# synth_revD.net
KiCad netlist of a schematic drawn in EAGLE
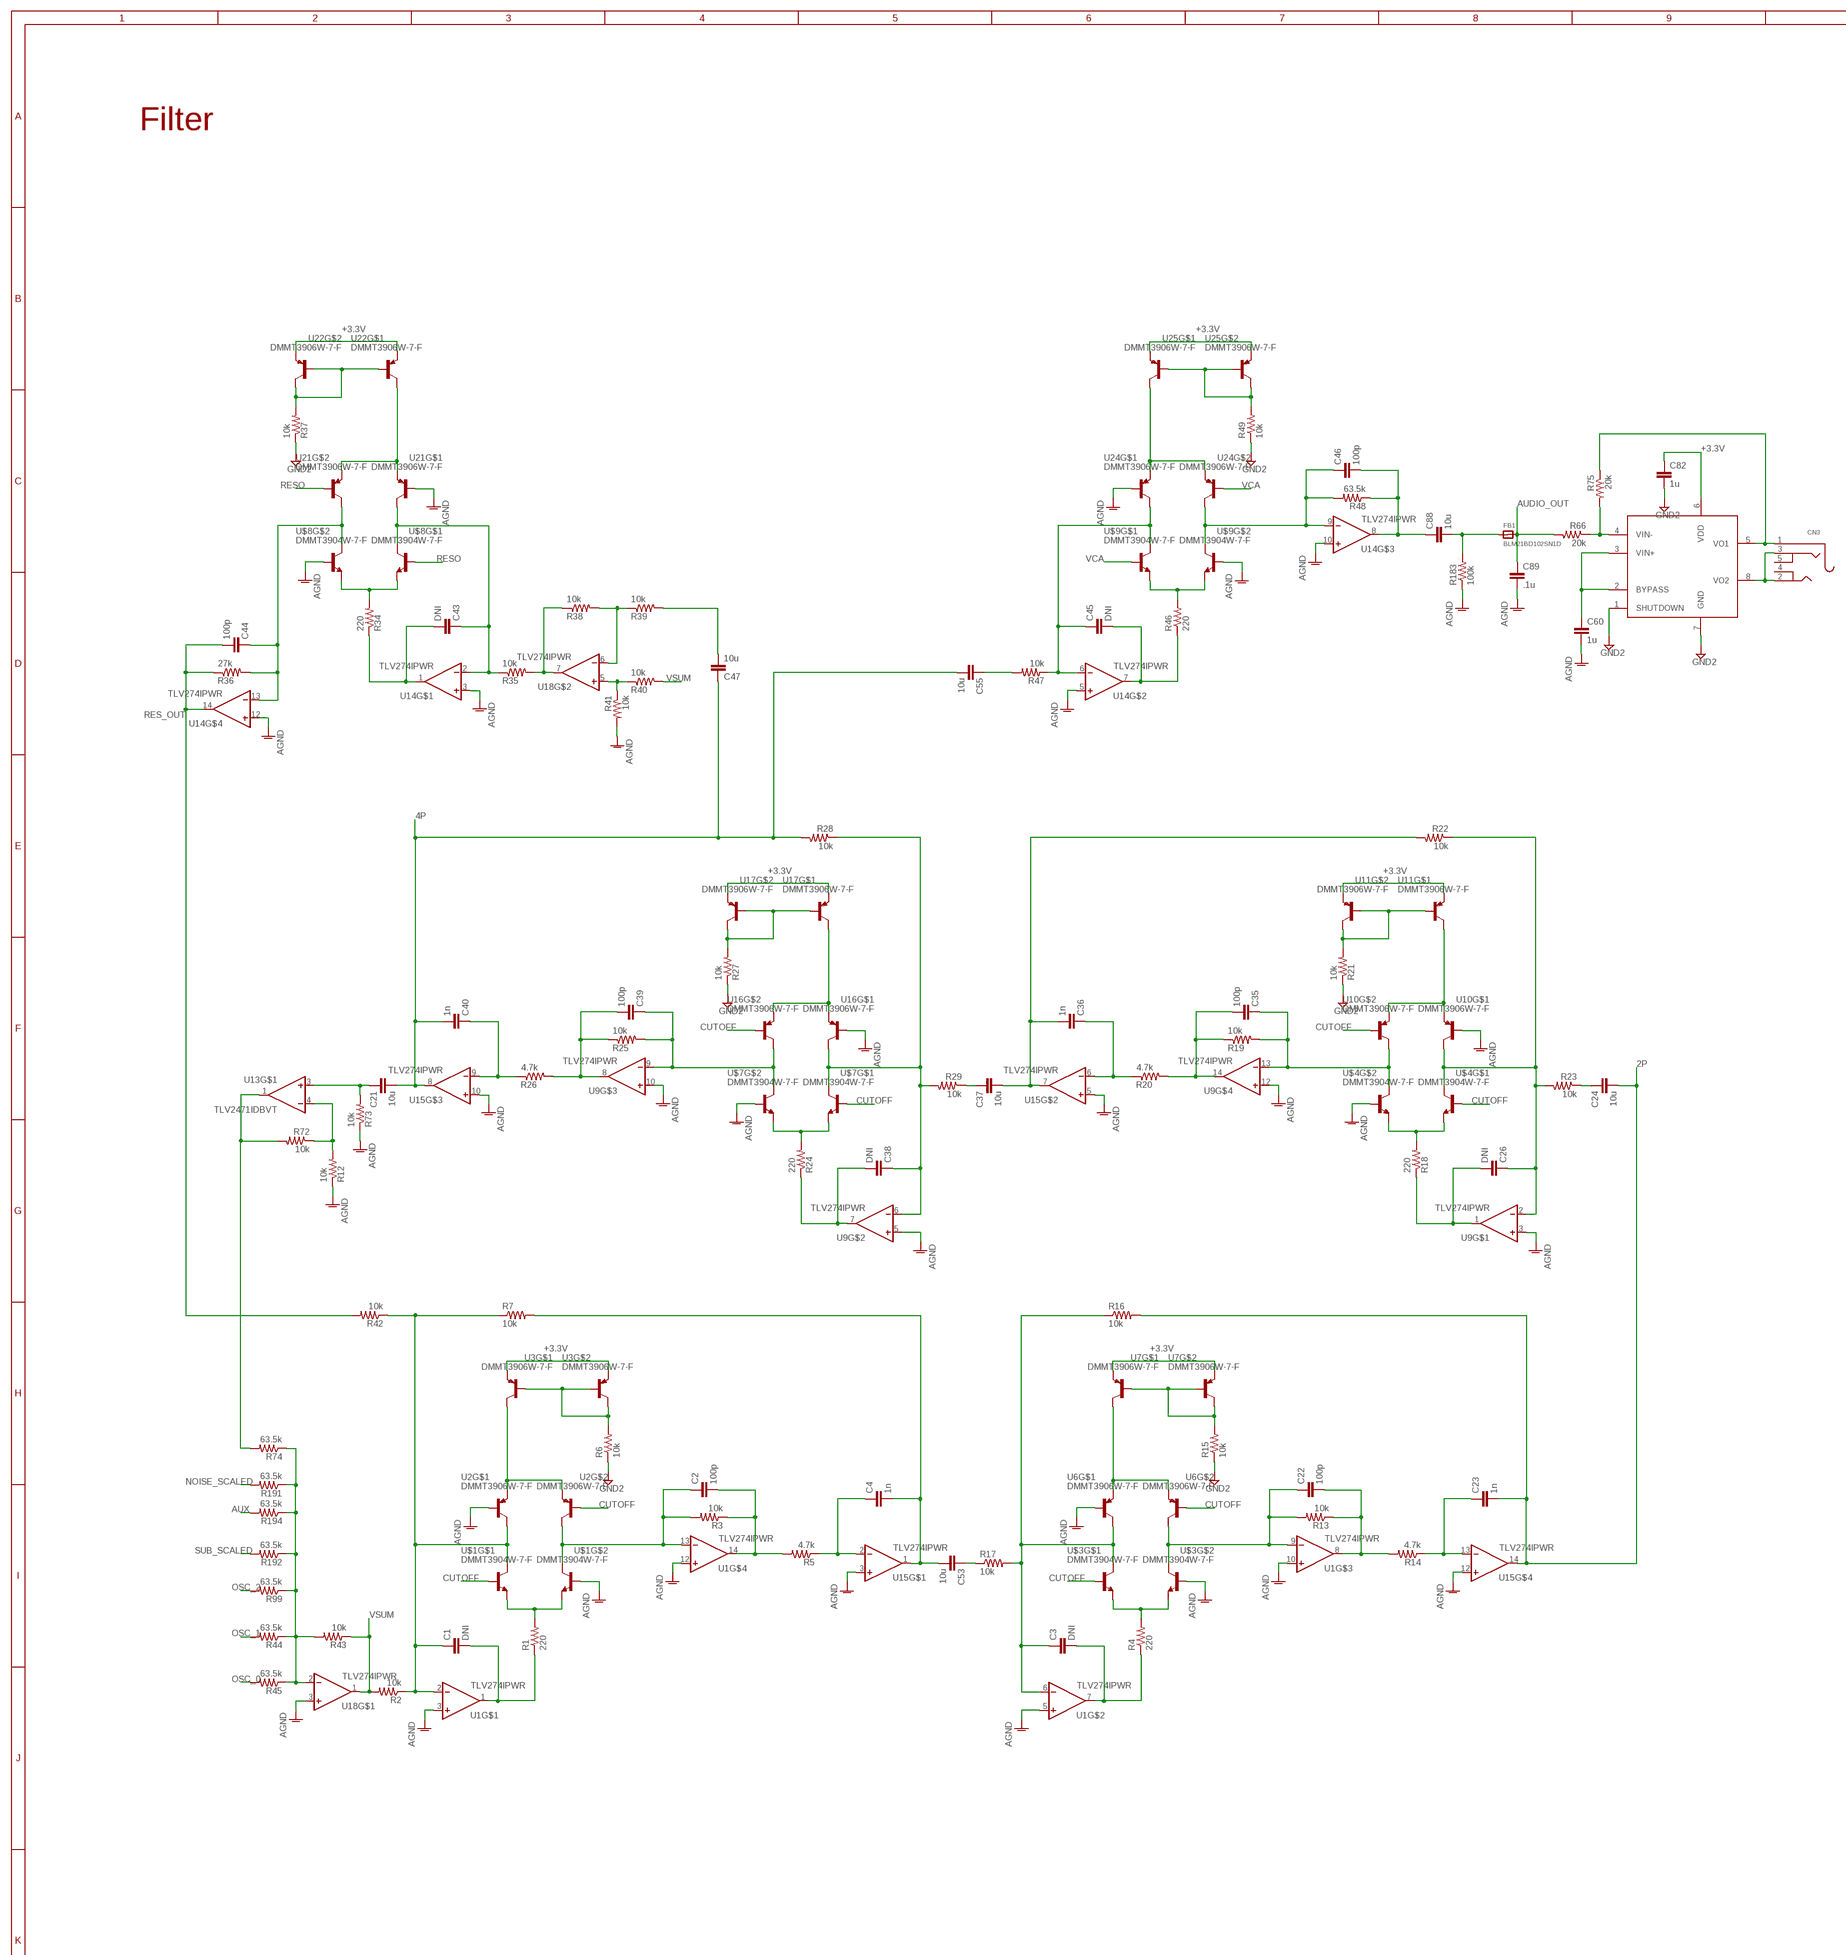
[diagram p0: schematic, sheet 1, part 1 of 3]
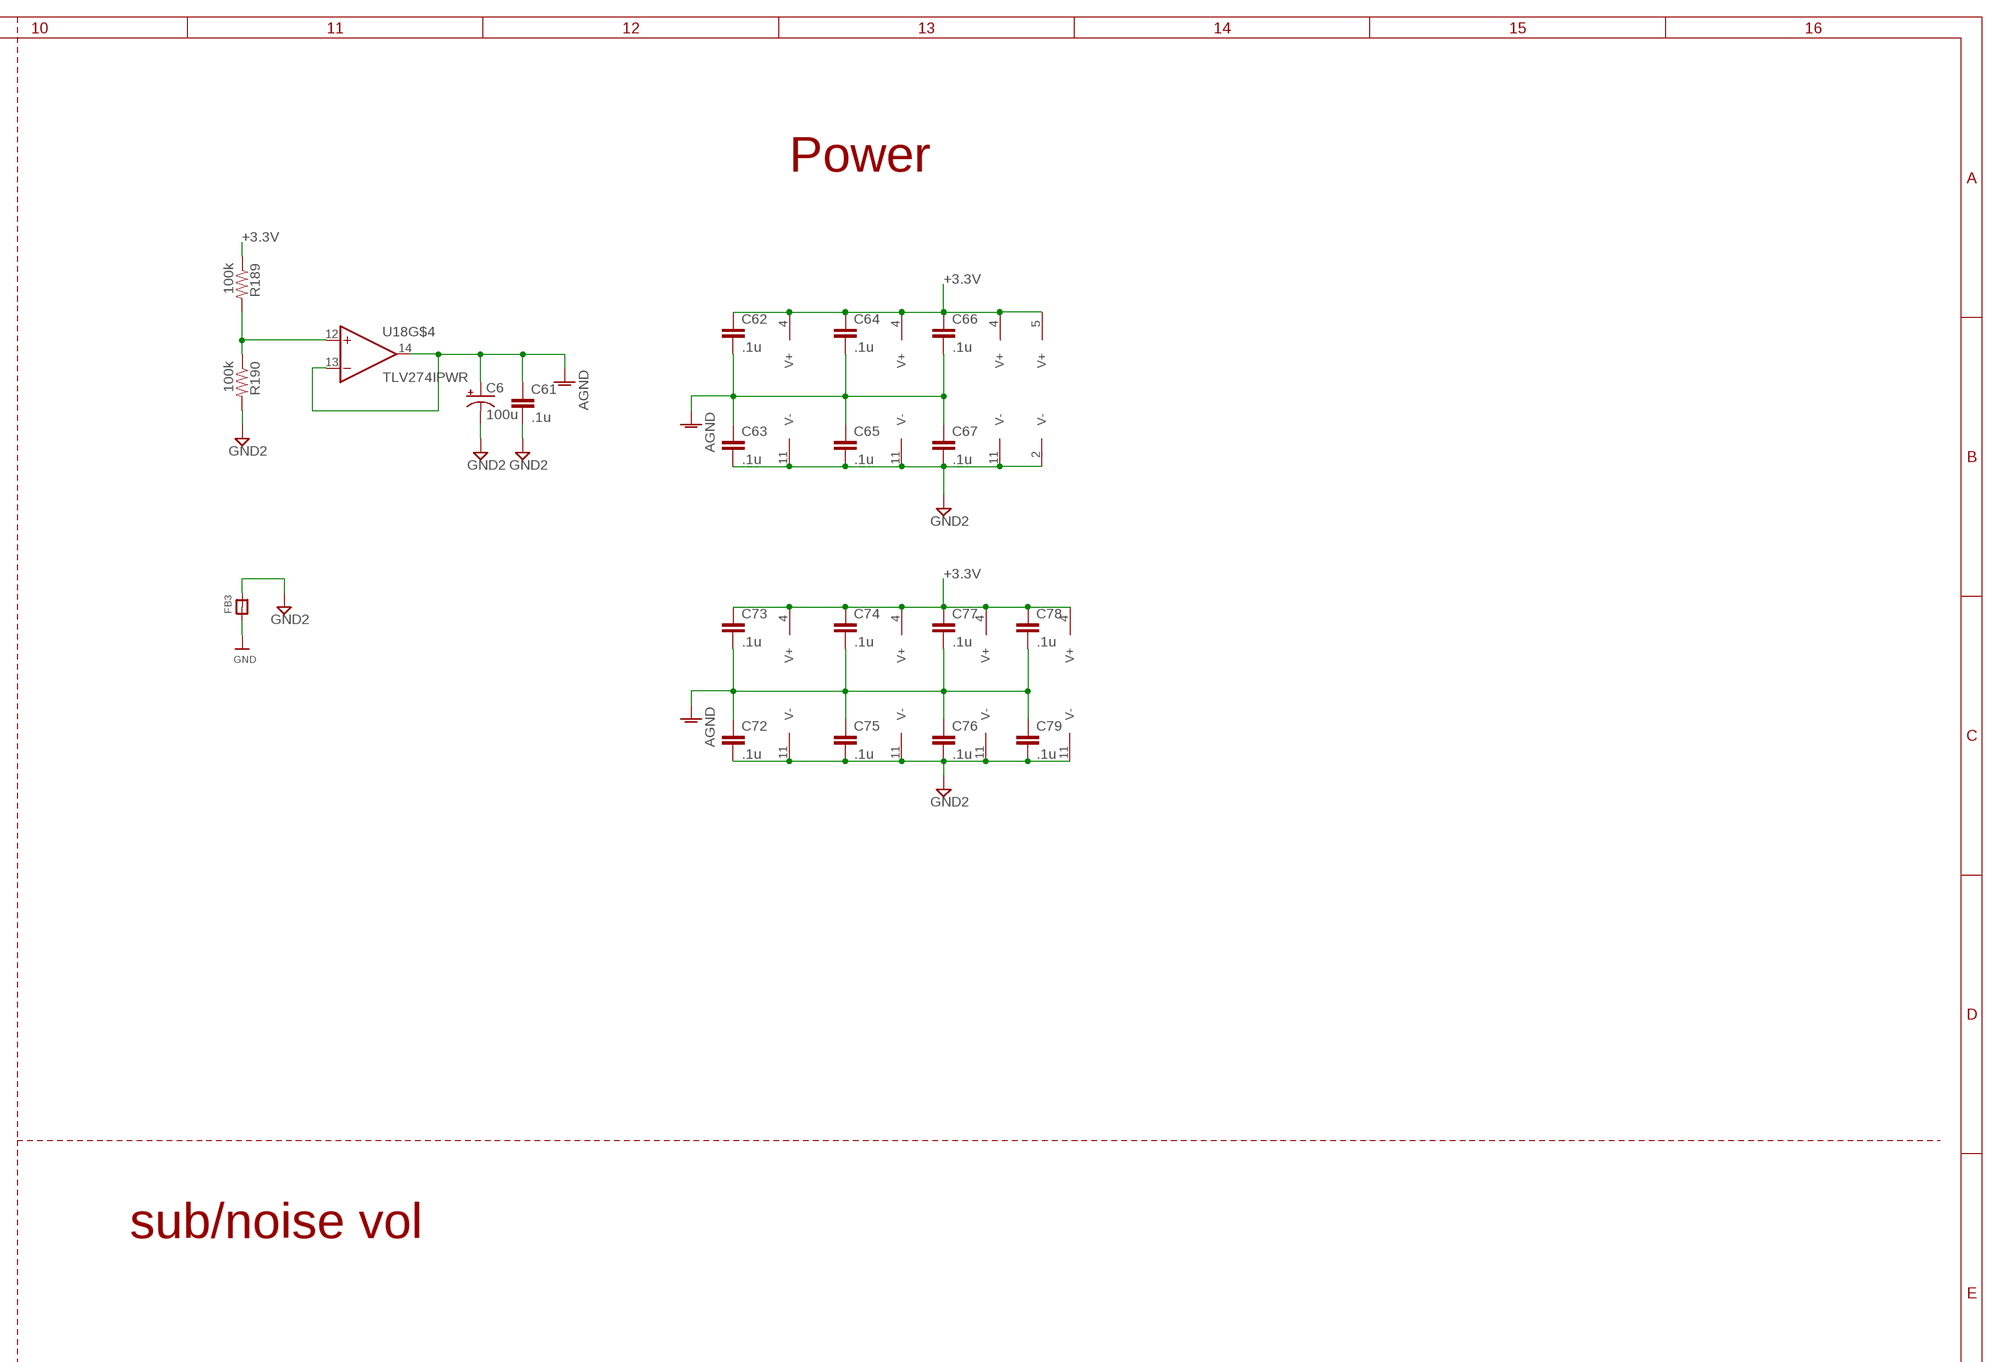
[diagram p1: schematic, sheet 1, part 2 of 3]
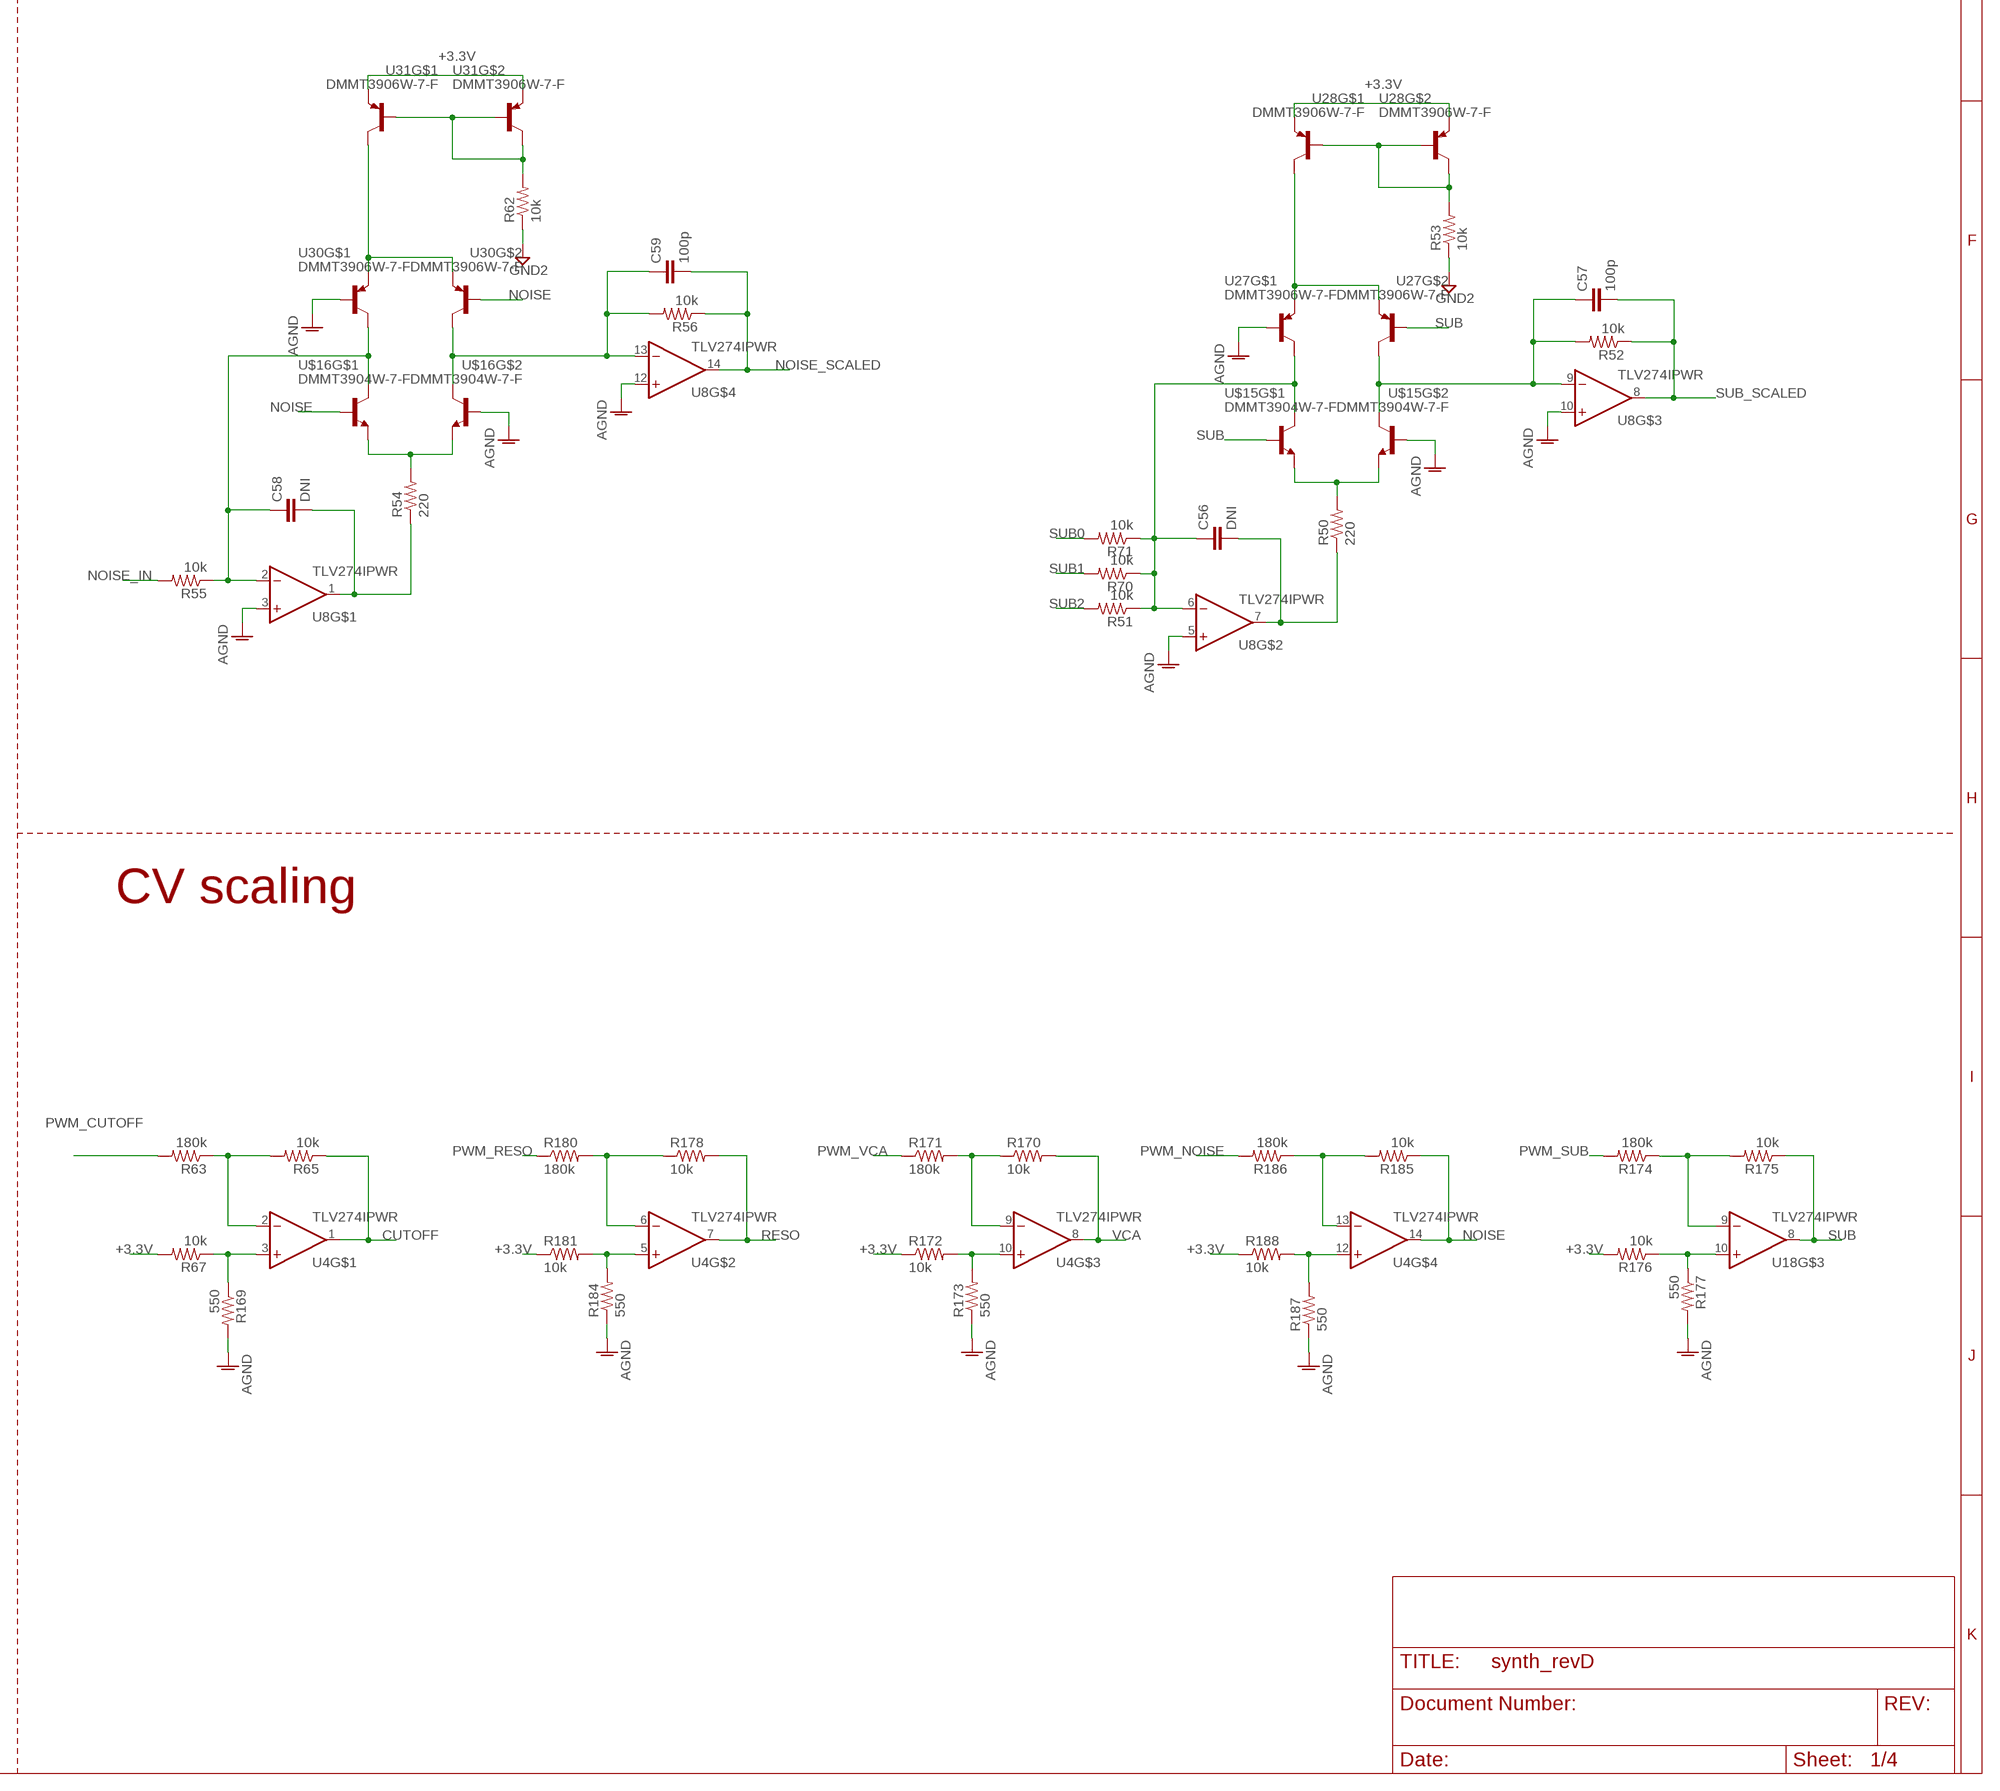
[diagram p2: schematic, sheet 1, part 3 of 3]
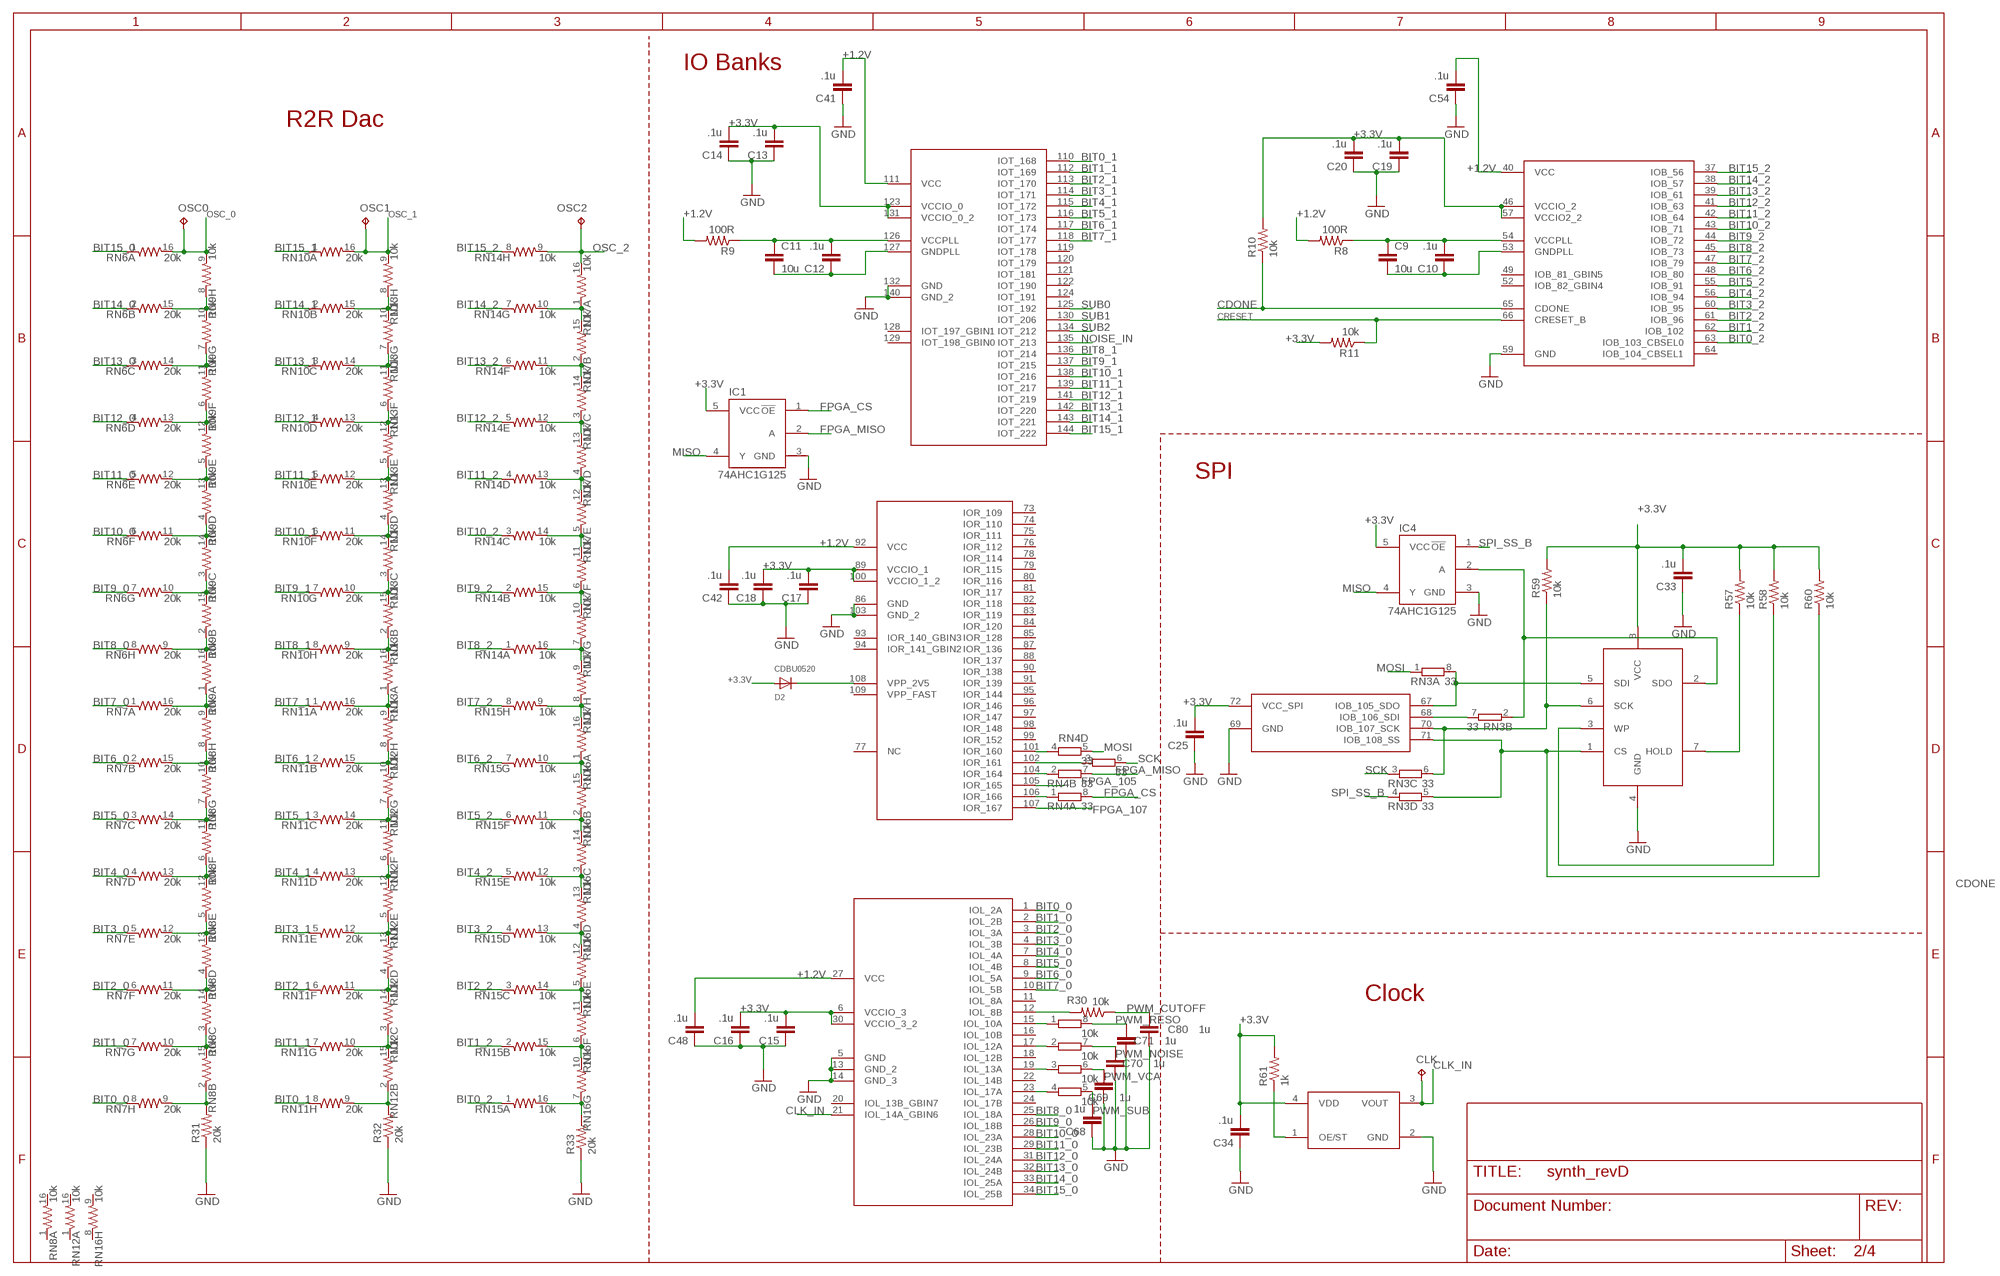
[diagram p3: schematic, sheet 2]
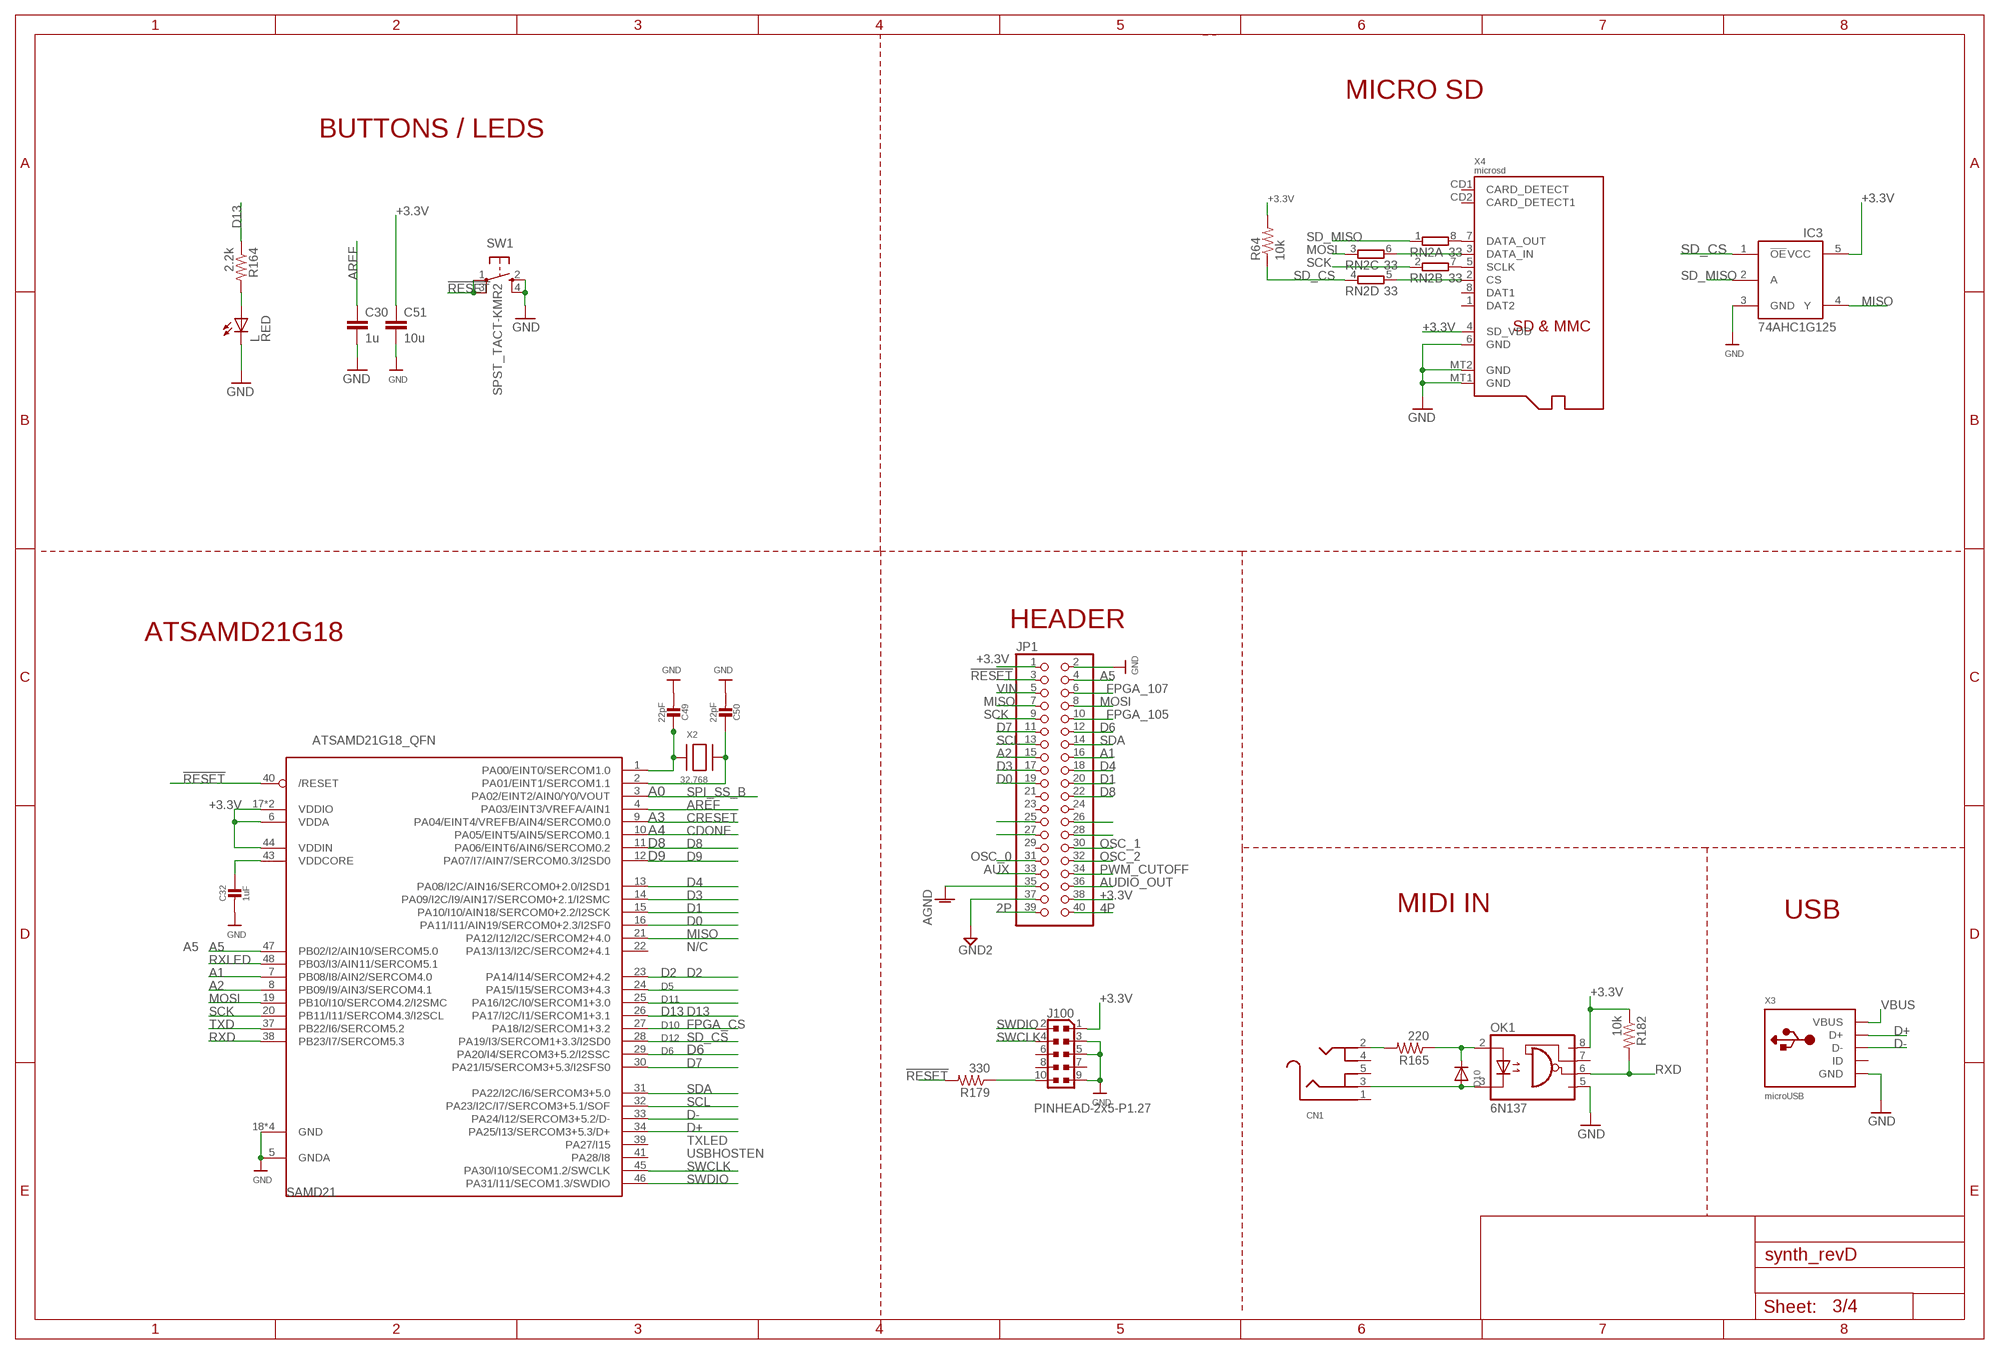
[diagram p4: schematic, sheet 3]
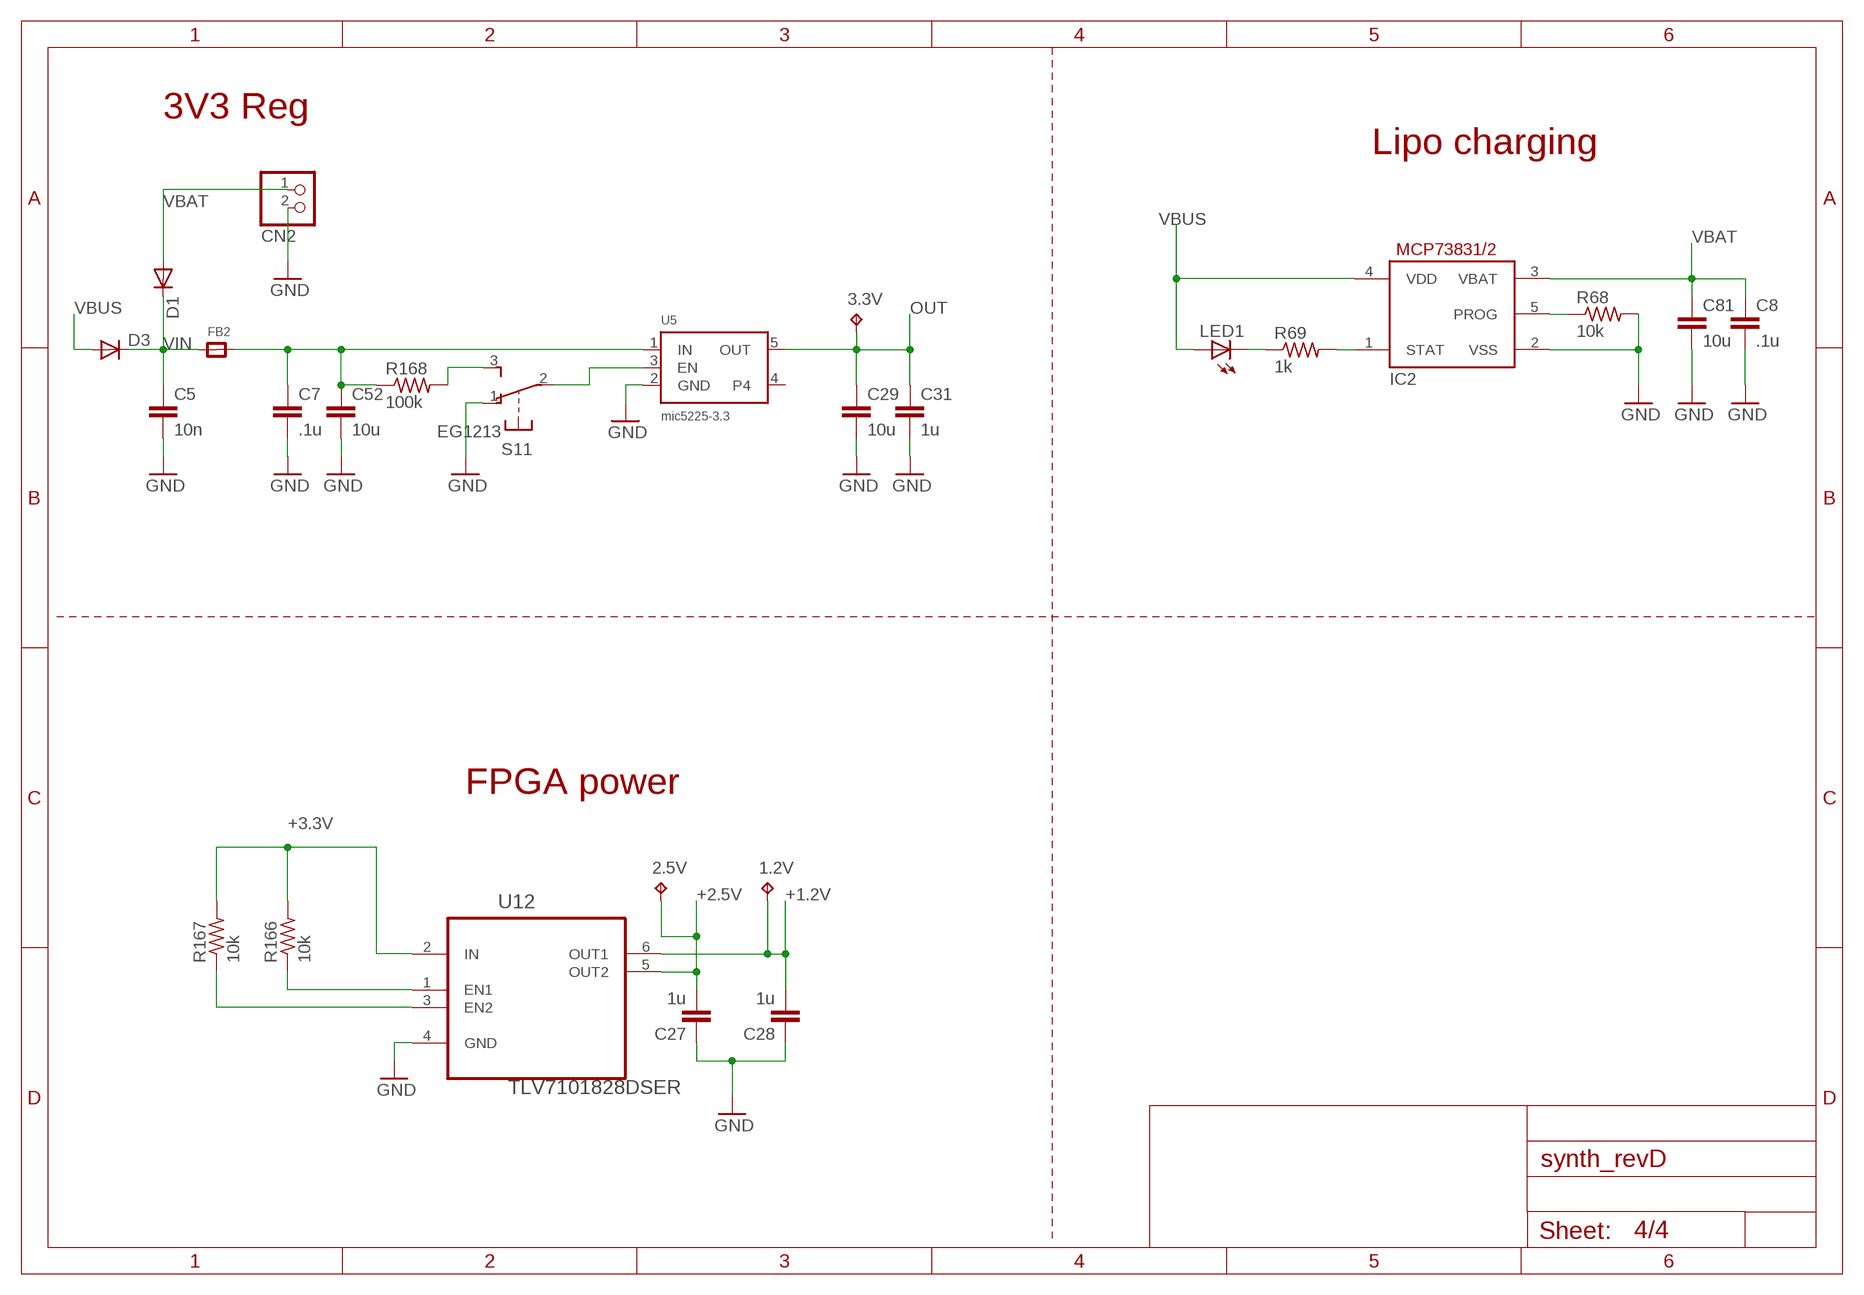
[diagram p5: schematic, sheet 4]

(export (version "E")
  (design (tool "Eeschema 10.0.6"))
  (components
    (comp (ref "C9")
      (value "10u")
      (footprint "eagle-import:C0603")
      (libsource (lib "eagle-import") (part "C-EUC0603"))
    )
    (comp (ref "C10")
      (value ".1u")
      (footprint "eagle-import:C0603")
      (libsource (lib "eagle-import") (part "C-EUC0603"))
    )
    (comp (ref "C11")
      (value "10u")
      (footprint "eagle-import:C0603")
      (libsource (lib "eagle-import") (part "C-EUC0603"))
    )
    (comp (ref "C12")
      (value ".1u")
      (footprint "eagle-import:C0603")
      (libsource (lib "eagle-import") (part "C-EUC0603"))
    )
    (comp (ref "C13")
      (value ".1u")
      (footprint "eagle-import:C0603")
      (libsource (lib "eagle-import") (part "C-EUC0603"))
    )
    (comp (ref "C14")
      (value ".1u")
      (footprint "eagle-import:C0603")
      (libsource (lib "eagle-import") (part "C-EUC0603"))
    )
    (comp (ref "C15")
      (value ".1u")
      (footprint "eagle-import:C0603")
      (libsource (lib "eagle-import") (part "C-EUC0603"))
    )
    (comp (ref "C16")
      (value ".1u")
      (footprint "eagle-import:C0603")
      (libsource (lib "eagle-import") (part "C-EUC0603"))
    )
    (comp (ref "C17")
      (value ".1u")
      (footprint "eagle-import:C0603")
      (libsource (lib "eagle-import") (part "C-EUC0603"))
    )
    (comp (ref "C18")
      (value ".1u")
      (footprint "eagle-import:C0603")
      (libsource (lib "eagle-import") (part "C-EUC0603"))
    )
    (comp (ref "C19")
      (value ".1u")
      (footprint "eagle-import:C0603")
      (libsource (lib "eagle-import") (part "C-EUC0603"))
    )
    (comp (ref "C20")
      (value ".1u")
      (footprint "eagle-import:C0603")
      (libsource (lib "eagle-import") (part "C-EUC0603"))
    )
    (comp (ref "C25")
      (value ".1u")
      (footprint "eagle-import:C0603")
      (libsource (lib "eagle-import") (part "C-EUC0603"))
    )
    (comp (ref "C33")
      (value ".1u")
      (footprint "eagle-import:C0603")
      (libsource (lib "eagle-import") (part "C-EUC0603"))
    )
    (comp (ref "C34")
      (value ".1u")
      (footprint "eagle-import:C0603")
      (libsource (lib "eagle-import") (part "C-EUC0603"))
    )
    (comp (ref "C41")
      (value ".1u")
      (footprint "eagle-import:C0603")
      (libsource (lib "eagle-import") (part "C-EUC0603"))
    )
    (comp (ref "C42")
      (value ".1u")
      (footprint "eagle-import:C0603")
      (libsource (lib "eagle-import") (part "C-EUC0603"))
    )
    (comp (ref "C48")
      (value ".1u")
      (footprint "eagle-import:C0603")
      (libsource (lib "eagle-import") (part "C-EUC0603"))
    )
    (comp (ref "C54")
      (value ".1u")
      (footprint "eagle-import:C0603")
      (libsource (lib "eagle-import") (part "C-EUC0603"))
    )
    (comp (ref "C68")
      (value "1u")
      (footprint "eagle-import:C0603")
      (libsource (lib "eagle-import") (part "C-EUC0603"))
    )
    (comp (ref "C69")
      (value "1u")
      (footprint "eagle-import:C0603")
      (libsource (lib "eagle-import") (part "C-EUC0603"))
    )
    (comp (ref "C70")
      (value "1u")
      (footprint "eagle-import:C0603")
      (libsource (lib "eagle-import") (part "C-EUC0603"))
    )
    (comp (ref "C71")
      (value "1u")
      (footprint "eagle-import:C0603")
      (libsource (lib "eagle-import") (part "C-EUC0603"))
    )
    (comp (ref "C80")
      (value "1u")
      (footprint "eagle-import:C0603")
      (libsource (lib "eagle-import") (part "C-EUC0603"))
    )
    (comp (ref "CLK")
      (value "TPB1,27")
      (footprint "eagle-import:B1,27")
      (libsource (lib "eagle-import") (part "TPB1,27"))
    )
    (comp (ref "D2")
      (value "CDBU0520")
      (footprint "eagle-import:SOD-523")
      (libsource (lib "eagle-import") (part "DIODESOD-523"))
    )
    (comp (ref "IC1")
      (value "74AHC1G125")
      (footprint "eagle-import:SOT23-5L")
      (libsource (lib "eagle-import") (part "74AHC1G125"))
    )
    (comp (ref "IC4")
      (value "74AHC1G125")
      (footprint "eagle-import:SOT23-5L")
      (libsource (lib "eagle-import") (part "74AHC1G125"))
    )
    (comp (ref "OSC0")
      (value "TPB1,27")
      (footprint "eagle-import:B1,27")
      (libsource (lib "eagle-import") (part "TPB1,27"))
    )
    (comp (ref "OSC1")
      (value "TPB1,27")
      (footprint "eagle-import:B1,27")
      (libsource (lib "eagle-import") (part "TPB1,27"))
    )
    (comp (ref "OSC2")
      (value "TPB1,27")
      (footprint "eagle-import:B1,27")
      (libsource (lib "eagle-import") (part "TPB1,27"))
    )
    (comp (ref "R8")
      (value "100R")
      (footprint "eagle-import:R0603")
      (libsource (lib "eagle-import") (part "rcl_R-US_R0603"))
    )
    (comp (ref "R9")
      (value "100R")
      (footprint "eagle-import:R0603")
      (libsource (lib "eagle-import") (part "rcl_R-US_R0603"))
    )
    (comp (ref "R10")
      (value "10k")
      (footprint "eagle-import:R0603")
      (libsource (lib "eagle-import") (part "rcl_R-US_R0603"))
    )
    (comp (ref "R11")
      (value "10k")
      (footprint "eagle-import:R0603")
      (libsource (lib "eagle-import") (part "rcl_R-US_R0603"))
    )
    (comp (ref "R30")
      (value "10k")
      (footprint "eagle-import:R0603")
      (libsource (lib "eagle-import") (part "rcl_R-US_R0603"))
    )
    (comp (ref "R31")
      (value "20k")
      (footprint "eagle-import:R0603")
      (libsource (lib "eagle-import") (part "rcl_R-US_R0603"))
    )
    (comp (ref "R32")
      (value "20k")
      (footprint "eagle-import:R0603")
      (libsource (lib "eagle-import") (part "rcl_R-US_R0603"))
    )
    (comp (ref "R33")
      (value "20k")
      (footprint "eagle-import:R0603")
      (libsource (lib "eagle-import") (part "rcl_R-US_R0603"))
    )
    (comp (ref "R57")
      (value "10k")
      (footprint "eagle-import:R0603")
      (libsource (lib "eagle-import") (part "rcl_R-US_R0603"))
    )
    (comp (ref "R58")
      (value "10k")
      (footprint "eagle-import:R0603")
      (libsource (lib "eagle-import") (part "rcl_R-US_R0603"))
    )
    (comp (ref "R59")
      (value "10k")
      (footprint "eagle-import:R0603")
      (libsource (lib "eagle-import") (part "rcl_R-US_R0603"))
    )
    (comp (ref "R60")
      (value "10k")
      (footprint "eagle-import:R0603")
      (libsource (lib "eagle-import") (part "rcl_R-US_R0603"))
    )
    (comp (ref "R61")
      (value "1k")
      (footprint "eagle-import:R0603")
      (libsource (lib "eagle-import") (part "rcl_R-US_R0603"))
    )
    (comp (ref "RAM1")
      (value "N25Q032A13ESC40FTR")
      (footprint "eagle-import:SO08")
      (libsource (lib "eagle-import") (part "N25Q032A13ESC40FTR"))
    )
    (comp (ref "RN3")
      (value "33")
      (footprint "eagle-import:0603-ARC")
      (libsource (lib "eagle-import") (part "4R-N0603-ARC"))
    )
    (comp (ref "RN4")
      (value "33")
      (footprint "eagle-import:0603-ARC")
      (libsource (lib "eagle-import") (part "4R-N0603-ARC"))
    )
    (comp (ref "RN5")
      (value "10k")
      (footprint "eagle-import:0603-ARC")
      (libsource (lib "eagle-import") (part "4R-N0603-ARC"))
    )
    (comp (ref "RN6")
      (value "20k")
      (footprint "eagle-import:742-16")
      (libsource (lib "eagle-import") (part "742-16_S"))
    )
    (comp (ref "RN7")
      (value "20k")
      (footprint "eagle-import:742-16")
      (libsource (lib "eagle-import") (part "742-16_S"))
    )
    (comp (ref "RN8")
      (value "10k")
      (footprint "eagle-import:742-16")
      (libsource (lib "eagle-import") (part "742-16_S"))
    )
    (comp (ref "RN9")
      (value "10k")
      (footprint "eagle-import:742-16")
      (libsource (lib "eagle-import") (part "742-16_S"))
    )
    (comp (ref "RN10")
      (value "20k")
      (footprint "eagle-import:742-16")
      (libsource (lib "eagle-import") (part "742-16_S"))
    )
    (comp (ref "RN11")
      (value "20k")
      (footprint "eagle-import:742-16")
      (libsource (lib "eagle-import") (part "742-16_S"))
    )
    (comp (ref "RN12")
      (value "10k")
      (footprint "eagle-import:742-16")
      (libsource (lib "eagle-import") (part "742-16_S"))
    )
    (comp (ref "RN13")
      (value "10k")
      (footprint "eagle-import:742-16")
      (libsource (lib "eagle-import") (part "742-16_S"))
    )
    (comp (ref "RN14")
      (value "10k")
      (footprint "eagle-import:742-16")
      (libsource (lib "eagle-import") (part "742-16_S"))
    )
    (comp (ref "RN15")
      (value "10k")
      (footprint "eagle-import:742-16")
      (libsource (lib "eagle-import") (part "742-16_S"))
    )
    (comp (ref "RN16")
      (value "10k")
      (footprint "eagle-import:742-16")
      (libsource (lib "eagle-import") (part "742-16_S"))
    )
    (comp (ref "RN17")
      (value "10k")
      (footprint "eagle-import:742-16")
      (libsource (lib "eagle-import") (part "742-16_S"))
    )
    (comp (ref "U$2")
      (value "ICE40HX4K")
      (footprint "eagle-import:TQ144")
      (libsource (lib "eagle-import") (part "ICE40HX4K"))
    )
    (comp (ref "U$5")
      (value "SIT1602")
      (footprint "eagle-import:SMD-43.2X2.5")
      (libsource (lib "eagle-import") (part "SIT1602"))
    )
    (comp (ref "1.2V")
      (value "TPB1,27")
      (footprint "eagle-import:B1,27")
      (libsource (lib "eagle-import") (part "TPB1,27"))
    )
    (comp (ref "2.5V")
      (value "TPB1,27")
      (footprint "eagle-import:B1,27")
      (libsource (lib "eagle-import") (part "TPB1,27"))
    )
    (comp (ref "3.3V")
      (value "TPB1,27")
      (footprint "eagle-import:B1,27")
      (libsource (lib "eagle-import") (part "TPB1,27"))
    )
    (comp (ref "C5")
      (value "10n")
      (footprint "eagle-import:C0603")
      (libsource (lib "eagle-import") (part "C-EUC0603"))
    )
    (comp (ref "C7")
      (value ".1u")
      (footprint "eagle-import:C0603")
      (libsource (lib "eagle-import") (part "C-EUC0603"))
    )
    (comp (ref "C8")
      (value ".1u")
      (footprint "eagle-import:C0603")
      (libsource (lib "eagle-import") (part "C-EUC0603"))
    )
    (comp (ref "C27")
      (value "1u")
      (footprint "eagle-import:C0603")
      (libsource (lib "eagle-import") (part "C-EUC0603"))
    )
    (comp (ref "C28")
      (value "1u")
      (footprint "eagle-import:C0603")
      (libsource (lib "eagle-import") (part "C-EUC0603"))
    )
    (comp (ref "C29")
      (value "10u")
      (footprint "eagle-import:C0603")
      (libsource (lib "eagle-import") (part "C-EUC0603"))
    )
    (comp (ref "C31")
      (value "1u")
      (footprint "eagle-import:C0603")
      (libsource (lib "eagle-import") (part "C-EUC0603"))
    )
    (comp (ref "C52")
      (value "10u")
      (footprint "eagle-import:C0603")
      (libsource (lib "eagle-import") (part "C-EUC0603"))
    )
    (comp (ref "C81")
      (value "10u")
      (footprint "eagle-import:C0603")
      (libsource (lib "eagle-import") (part "C-EUC0603"))
    )
    (comp (ref "CN2")
      (value "JST_2PIN-SMT-RA")
      (footprint "eagle-import:JST-PH-2-SMT-RA")
      (libsource (lib "eagle-import") (part "JST_2PIN-SMT-RA"))
    )
    (comp (ref "D1")
      (value "DIODE-SOD123")
      (footprint "eagle-import:SOD123")
      (libsource (lib "eagle-import") (part "DIODE-SOD123"))
    )
    (comp (ref "D3")
      (value "DIODE-SOD123")
      (footprint "eagle-import:SOD123")
      (libsource (lib "eagle-import") (part "DIODE-SOD123"))
    )
    (comp (ref "FB2")
      (value "FERRITE")
      (footprint "eagle-import:0603")
      (libsource (lib "eagle-import") (part "FERRITE"))
    )
    (comp (ref "IC2")
      (value "MCP73831/OT")
      (footprint "eagle-import:SOT23-5L")
      (libsource (lib "eagle-import") (part "MCP73831/OT"))
    )
    (comp (ref "LED1")
      (value "LEDCHIP-LED0805")
      (footprint "eagle-import:CHIP-LED0805")
      (libsource (lib "eagle-import") (part "LEDCHIP-LED0805"))
    )
    (comp (ref "R68")
      (value "10k")
      (footprint "eagle-import:R0603")
      (libsource (lib "eagle-import") (part "R-US_R0603"))
    )
    (comp (ref "R69")
      (value "1k")
      (footprint "eagle-import:R0603")
      (libsource (lib "eagle-import") (part "R-US_R0603"))
    )
    (comp (ref "R166")
      (value "10k")
      (footprint "eagle-import:R0603")
      (libsource (lib "eagle-import") (part "R-US_R0603"))
    )
    (comp (ref "R167")
      (value "10k")
      (footprint "eagle-import:R0603")
      (libsource (lib "eagle-import") (part "R-US_R0603"))
    )
    (comp (ref "R168")
      (value "100k")
      (footprint "eagle-import:R0603")
      (libsource (lib "eagle-import") (part "R-US_R0603"))
    )
    (comp (ref "S1")
      (value "EG1213")
      (footprint "eagle-import:EG1213")
      (libsource (lib "eagle-import") (part "EG1213"))
    )
    (comp (ref "U5")
      (value "mic5225-3.3")
      (footprint "eagle-import:SOT23-5")
      (libsource (lib "eagle-import") (part "VREG_SOT23-5"))
    )
    (comp (ref "U12")
      (value "TLV7101828DSER")
      (footprint "eagle-import:SON50P150X150X80-6N")
      (libsource (lib "eagle-import") (part "TLV7101828DSER"))
    )
    (comp (ref "C1")
      (value "DNI")
      (footprint "eagle-import:C0603")
      (libsource (lib "eagle-import") (part "C-EUC0603"))
    )
    (comp (ref "C2")
      (value "100p")
      (footprint "eagle-import:C0603")
      (libsource (lib "eagle-import") (part "C-EUC0603"))
    )
    (comp (ref "C3")
      (value "DNI")
      (footprint "eagle-import:C0603")
      (libsource (lib "eagle-import") (part "C-EUC0603"))
    )
    (comp (ref "C4")
      (value "1n")
      (footprint "eagle-import:C0603")
      (libsource (lib "eagle-import") (part "C-EUC0603"))
    )
    (comp (ref "C6")
      (value "100u")
      (footprint "eagle-import:PANASONIC_C")
      (libsource (lib "eagle-import") (part "CPOL-USC"))
    )
    (comp (ref "C21")
      (value "10u")
      (footprint "eagle-import:C0603")
      (libsource (lib "eagle-import") (part "C-EUC0603"))
    )
    (comp (ref "C22")
      (value "100p")
      (footprint "eagle-import:C0603")
      (libsource (lib "eagle-import") (part "C-EUC0603"))
    )
    (comp (ref "C23")
      (value "1n")
      (footprint "eagle-import:C0603")
      (libsource (lib "eagle-import") (part "C-EUC0603"))
    )
    (comp (ref "C24")
      (value "10u")
      (footprint "eagle-import:C0603")
      (libsource (lib "eagle-import") (part "C-EUC0603"))
    )
    (comp (ref "C26")
      (value "DNI")
      (footprint "eagle-import:C0603")
      (libsource (lib "eagle-import") (part "C-EUC0603"))
    )
    (comp (ref "C35")
      (value "100p")
      (footprint "eagle-import:C0603")
      (libsource (lib "eagle-import") (part "C-EUC0603"))
    )
    (comp (ref "C36")
      (value "1n")
      (footprint "eagle-import:C0603")
      (libsource (lib "eagle-import") (part "C-EUC0603"))
    )
    (comp (ref "C37")
      (value "10u")
      (footprint "eagle-import:C0603")
      (libsource (lib "eagle-import") (part "C-EUC0603"))
    )
    (comp (ref "C38")
      (value "DNI")
      (footprint "eagle-import:C0603")
      (libsource (lib "eagle-import") (part "C-EUC0603"))
    )
    (comp (ref "C39")
      (value "100p")
      (footprint "eagle-import:C0603")
      (libsource (lib "eagle-import") (part "C-EUC0603"))
    )
    (comp (ref "C40")
      (value "1n")
      (footprint "eagle-import:C0603")
      (libsource (lib "eagle-import") (part "C-EUC0603"))
    )
    (comp (ref "C43")
      (value "DNI")
      (footprint "eagle-import:C0603")
      (libsource (lib "eagle-import") (part "C-EUC0603"))
    )
    (comp (ref "C44")
      (value "100p")
      (footprint "eagle-import:C0603")
      (libsource (lib "eagle-import") (part "C-EUC0603"))
    )
    (comp (ref "C45")
      (value "DNI")
      (footprint "eagle-import:C0603")
      (libsource (lib "eagle-import") (part "C-EUC0603"))
    )
    (comp (ref "C46")
      (value "100p")
      (footprint "eagle-import:C0603")
      (libsource (lib "eagle-import") (part "C-EUC0603"))
    )
    (comp (ref "C47")
      (value "10u")
      (footprint "eagle-import:C0603")
      (libsource (lib "eagle-import") (part "C-EUC0603"))
    )
    (comp (ref "C53")
      (value "10u")
      (footprint "eagle-import:C0603")
      (libsource (lib "eagle-import") (part "C-EUC0603"))
    )
    (comp (ref "C55")
      (value "10u")
      (footprint "eagle-import:C0603")
      (libsource (lib "eagle-import") (part "C-EUC0603"))
    )
    (comp (ref "C56")
      (value "DNI")
      (footprint "eagle-import:C0603")
      (libsource (lib "eagle-import") (part "C-EUC0603"))
    )
    (comp (ref "C57")
      (value "100p")
      (footprint "eagle-import:C0603")
      (libsource (lib "eagle-import") (part "C-EUC0603"))
    )
    (comp (ref "C58")
      (value "DNI")
      (footprint "eagle-import:C0603")
      (libsource (lib "eagle-import") (part "C-EUC0603"))
    )
    (comp (ref "C59")
      (value "100p")
      (footprint "eagle-import:C0603")
      (libsource (lib "eagle-import") (part "C-EUC0603"))
    )
    (comp (ref "C60")
      (value "1u")
      (footprint "eagle-import:C0603")
      (libsource (lib "eagle-import") (part "C-EUC0603"))
    )
    (comp (ref "C61")
      (value ".1u")
      (footprint "eagle-import:C0603")
      (libsource (lib "eagle-import") (part "C-EUC0603"))
    )
    (comp (ref "C62")
      (value ".1u")
      (footprint "eagle-import:C0603")
      (libsource (lib "eagle-import") (part "C-EUC0603"))
    )
    (comp (ref "C63")
      (value ".1u")
      (footprint "eagle-import:C0603")
      (libsource (lib "eagle-import") (part "C-EUC0603"))
    )
    (comp (ref "C64")
      (value ".1u")
      (footprint "eagle-import:C0603")
      (libsource (lib "eagle-import") (part "C-EUC0603"))
    )
    (comp (ref "C65")
      (value ".1u")
      (footprint "eagle-import:C0603")
      (libsource (lib "eagle-import") (part "C-EUC0603"))
    )
    (comp (ref "C66")
      (value ".1u")
      (footprint "eagle-import:C0603")
      (libsource (lib "eagle-import") (part "C-EUC0603"))
    )
    (comp (ref "C67")
      (value ".1u")
      (footprint "eagle-import:C0603")
      (libsource (lib "eagle-import") (part "C-EUC0603"))
    )
    (comp (ref "C72")
      (value ".1u")
      (footprint "eagle-import:C0603")
      (libsource (lib "eagle-import") (part "C-EUC0603"))
    )
    (comp (ref "C73")
      (value ".1u")
      (footprint "eagle-import:C0603")
      (libsource (lib "eagle-import") (part "C-EUC0603"))
    )
    (comp (ref "C74")
      (value ".1u")
      (footprint "eagle-import:C0603")
      (libsource (lib "eagle-import") (part "C-EUC0603"))
    )
    (comp (ref "C75")
      (value ".1u")
      (footprint "eagle-import:C0603")
      (libsource (lib "eagle-import") (part "C-EUC0603"))
    )
    (comp (ref "C76")
      (value ".1u")
      (footprint "eagle-import:C0603")
      (libsource (lib "eagle-import") (part "C-EUC0603"))
    )
    (comp (ref "C77")
      (value ".1u")
      (footprint "eagle-import:C0603")
      (libsource (lib "eagle-import") (part "C-EUC0603"))
    )
    (comp (ref "C78")
      (value ".1u")
      (footprint "eagle-import:C0603")
      (libsource (lib "eagle-import") (part "C-EUC0603"))
    )
    (comp (ref "C79")
      (value ".1u")
      (footprint "eagle-import:C0603")
      (libsource (lib "eagle-import") (part "C-EUC0603"))
    )
    (comp (ref "C82")
      (value "1u")
      (footprint "eagle-import:C0603")
      (libsource (lib "eagle-import") (part "C-EUC0603"))
    )
    (comp (ref "C88")
      (value "10u")
      (footprint "eagle-import:C0603")
      (libsource (lib "eagle-import") (part "C-EUC0603"))
    )
    (comp (ref "C89")
      (value ".1u")
      (footprint "eagle-import:C0603")
      (libsource (lib "eagle-import") (part "C-EUC0603"))
    )
    (comp (ref "CN3")
      (value "AUDIO_3.5MMJACK")
      (footprint "eagle-import:4UCONN_19269")
      (libsource (lib "eagle-import") (part "AUDIO_3.5MMJACK"))
    )
    (comp (ref "FB1")
      (value "BLM21BD102SN1D")
      (footprint "eagle-import:0805")
      (libsource (lib "eagle-import") (part "FERRITE0805"))
    )
    (comp (ref "FB3")
      (value "FERRITE0805")
      (footprint "eagle-import:0805")
      (libsource (lib "eagle-import") (part "FERRITE0805"))
    )
    (comp (ref "R1")
      (value "220")
      (footprint "eagle-import:R0603")
      (libsource (lib "eagle-import") (part "rcl_R-US_R0603"))
    )
    (comp (ref "R2")
      (value "10k")
      (footprint "eagle-import:R0603")
      (libsource (lib "eagle-import") (part "rcl_R-US_R0603"))
    )
    (comp (ref "R3")
      (value "10k")
      (footprint "eagle-import:R0603")
      (libsource (lib "eagle-import") (part "rcl_R-US_R0603"))
    )
    (comp (ref "R4")
      (value "220")
      (footprint "eagle-import:R0603")
      (libsource (lib "eagle-import") (part "rcl_R-US_R0603"))
    )
    (comp (ref "R5")
      (value "4.7k")
      (footprint "eagle-import:R0603")
      (libsource (lib "eagle-import") (part "rcl_R-US_R0603"))
    )
    (comp (ref "R6")
      (value "10k")
      (footprint "eagle-import:R0603")
      (libsource (lib "eagle-import") (part "rcl_R-US_R0603"))
    )
    (comp (ref "R7")
      (value "10k")
      (footprint "eagle-import:R0603")
      (libsource (lib "eagle-import") (part "rcl_R-US_R0603"))
    )
    (comp (ref "R12")
      (value "10k")
      (footprint "eagle-import:R0603")
      (libsource (lib "eagle-import") (part "rcl_R-US_R0603"))
    )
    (comp (ref "R13")
      (value "10k")
      (footprint "eagle-import:R0603")
      (libsource (lib "eagle-import") (part "rcl_R-US_R0603"))
    )
    (comp (ref "R14")
      (value "4.7k")
      (footprint "eagle-import:R0603")
      (libsource (lib "eagle-import") (part "rcl_R-US_R0603"))
    )
    (comp (ref "R15")
      (value "10k")
      (footprint "eagle-import:R0603")
      (libsource (lib "eagle-import") (part "rcl_R-US_R0603"))
    )
    (comp (ref "R16")
      (value "10k")
      (footprint "eagle-import:R0603")
      (libsource (lib "eagle-import") (part "rcl_R-US_R0603"))
    )
    (comp (ref "R17")
      (value "10k")
      (footprint "eagle-import:R0603")
      (libsource (lib "eagle-import") (part "rcl_R-US_R0603"))
    )
    (comp (ref "R18")
      (value "220")
      (footprint "eagle-import:R0603")
      (libsource (lib "eagle-import") (part "rcl_R-US_R0603"))
    )
    (comp (ref "R19")
      (value "10k")
      (footprint "eagle-import:R0603")
      (libsource (lib "eagle-import") (part "rcl_R-US_R0603"))
    )
    (comp (ref "R20")
      (value "4.7k")
      (footprint "eagle-import:R0603")
      (libsource (lib "eagle-import") (part "rcl_R-US_R0603"))
    )
    (comp (ref "R21")
      (value "10k")
      (footprint "eagle-import:R0603")
      (libsource (lib "eagle-import") (part "rcl_R-US_R0603"))
    )
    (comp (ref "R22")
      (value "10k")
      (footprint "eagle-import:R0603")
      (libsource (lib "eagle-import") (part "rcl_R-US_R0603"))
    )
    (comp (ref "R23")
      (value "10k")
      (footprint "eagle-import:R0603")
      (libsource (lib "eagle-import") (part "rcl_R-US_R0603"))
    )
    (comp (ref "R24")
      (value "220")
      (footprint "eagle-import:R0603")
      (libsource (lib "eagle-import") (part "rcl_R-US_R0603"))
    )
    (comp (ref "R25")
      (value "10k")
      (footprint "eagle-import:R0603")
      (libsource (lib "eagle-import") (part "rcl_R-US_R0603"))
    )
    (comp (ref "R26")
      (value "4.7k")
      (footprint "eagle-import:R0603")
      (libsource (lib "eagle-import") (part "rcl_R-US_R0603"))
    )
    (comp (ref "R27")
      (value "10k")
      (footprint "eagle-import:R0603")
      (libsource (lib "eagle-import") (part "rcl_R-US_R0603"))
    )
    (comp (ref "R28")
      (value "10k")
      (footprint "eagle-import:R0603")
      (libsource (lib "eagle-import") (part "rcl_R-US_R0603"))
    )
    (comp (ref "R29")
      (value "10k")
      (footprint "eagle-import:R0603")
      (libsource (lib "eagle-import") (part "rcl_R-US_R0603"))
    )
    (comp (ref "R34")
      (value "220")
      (footprint "eagle-import:R0603")
      (libsource (lib "eagle-import") (part "rcl_R-US_R0603"))
    )
    (comp (ref "R35")
      (value "10k")
      (footprint "eagle-import:R0603")
      (libsource (lib "eagle-import") (part "rcl_R-US_R0603"))
    )
    (comp (ref "R36")
      (value "27k")
      (footprint "eagle-import:R0603")
      (libsource (lib "eagle-import") (part "rcl_R-US_R0603"))
    )
    (comp (ref "R37")
      (value "10k")
      (footprint "eagle-import:R0603")
      (libsource (lib "eagle-import") (part "rcl_R-US_R0603"))
    )
    (comp (ref "R38")
      (value "10k")
      (footprint "eagle-import:R0603")
      (libsource (lib "eagle-import") (part "rcl_R-US_R0603"))
    )
    (comp (ref "R39")
      (value "10k")
      (footprint "eagle-import:R0603")
      (libsource (lib "eagle-import") (part "rcl_R-US_R0603"))
    )
    (comp (ref "R40")
      (value "10k")
      (footprint "eagle-import:R0603")
      (libsource (lib "eagle-import") (part "rcl_R-US_R0603"))
    )
    (comp (ref "R41")
      (value "10k")
      (footprint "eagle-import:R0603")
      (libsource (lib "eagle-import") (part "rcl_R-US_R0603"))
    )
    (comp (ref "R42")
      (value "10k")
      (footprint "eagle-import:R0603")
      (libsource (lib "eagle-import") (part "rcl_R-US_R0603"))
    )
    (comp (ref "R43")
      (value "10k")
      (footprint "eagle-import:R0603")
      (libsource (lib "eagle-import") (part "rcl_R-US_R0603"))
    )
    (comp (ref "R44")
      (value "63.5k")
      (footprint "eagle-import:R0603")
      (libsource (lib "eagle-import") (part "rcl_R-US_R0603"))
    )
    (comp (ref "R45")
      (value "63.5k")
      (footprint "eagle-import:R0603")
      (libsource (lib "eagle-import") (part "rcl_R-US_R0603"))
    )
    (comp (ref "R46")
      (value "220")
      (footprint "eagle-import:R0603")
      (libsource (lib "eagle-import") (part "rcl_R-US_R0603"))
    )
    (comp (ref "R47")
      (value "10k")
      (footprint "eagle-import:R0603")
      (libsource (lib "eagle-import") (part "rcl_R-US_R0603"))
    )
    (comp (ref "R48")
      (value "63.5k")
      (footprint "eagle-import:R0603")
      (libsource (lib "eagle-import") (part "rcl_R-US_R0603"))
    )
    (comp (ref "R49")
      (value "10k")
      (footprint "eagle-import:R0603")
      (libsource (lib "eagle-import") (part "rcl_R-US_R0603"))
    )
    (comp (ref "R50")
      (value "220")
      (footprint "eagle-import:R0603")
      (libsource (lib "eagle-import") (part "rcl_R-US_R0603"))
    )
    (comp (ref "R51")
      (value "10k")
      (footprint "eagle-import:R0603")
      (libsource (lib "eagle-import") (part "rcl_R-US_R0603"))
    )
    (comp (ref "R52")
      (value "10k")
      (footprint "eagle-import:R0603")
      (libsource (lib "eagle-import") (part "rcl_R-US_R0603"))
    )
    (comp (ref "R53")
      (value "10k")
      (footprint "eagle-import:R0603")
      (libsource (lib "eagle-import") (part "rcl_R-US_R0603"))
    )
    (comp (ref "R54")
      (value "220")
      (footprint "eagle-import:R0603")
      (libsource (lib "eagle-import") (part "rcl_R-US_R0603"))
    )
    (comp (ref "R55")
      (value "10k")
      (footprint "eagle-import:R0603")
      (libsource (lib "eagle-import") (part "rcl_R-US_R0603"))
    )
    (comp (ref "R56")
      (value "10k")
      (footprint "eagle-import:R0603")
      (libsource (lib "eagle-import") (part "rcl_R-US_R0603"))
    )
    (comp (ref "R62")
      (value "10k")
      (footprint "eagle-import:R0603")
      (libsource (lib "eagle-import") (part "rcl_R-US_R0603"))
    )
    (comp (ref "R63")
      (value "180k")
      (footprint "eagle-import:R0603")
      (libsource (lib "eagle-import") (part "rcl_R-US_R0603"))
    )
    (comp (ref "R65")
      (value "10k")
      (footprint "eagle-import:R0603")
      (libsource (lib "eagle-import") (part "rcl_R-US_R0603"))
    )
    (comp (ref "R66")
      (value "20k")
      (footprint "eagle-import:R0603")
      (libsource (lib "eagle-import") (part "rcl_R-US_R0603"))
    )
    (comp (ref "R67")
      (value "10k")
      (footprint "eagle-import:R0603")
      (libsource (lib "eagle-import") (part "rcl_R-US_R0603"))
    )
    (comp (ref "R70")
      (value "10k")
      (footprint "eagle-import:R0603")
      (libsource (lib "eagle-import") (part "rcl_R-US_R0603"))
    )
    (comp (ref "R71")
      (value "10k")
      (footprint "eagle-import:R0603")
      (libsource (lib "eagle-import") (part "rcl_R-US_R0603"))
    )
    (comp (ref "R72")
      (value "10k")
      (footprint "eagle-import:R0603")
      (libsource (lib "eagle-import") (part "rcl_R-US_R0603"))
    )
    (comp (ref "R73")
      (value "10k")
      (footprint "eagle-import:R0603")
      (libsource (lib "eagle-import") (part "rcl_R-US_R0603"))
    )
    (comp (ref "R74")
      (value "63.5k")
      (footprint "eagle-import:R0603")
      (libsource (lib "eagle-import") (part "rcl_R-US_R0603"))
    )
    (comp (ref "R75")
      (value "20k")
      (footprint "eagle-import:R0603")
      (libsource (lib "eagle-import") (part "rcl_R-US_R0603"))
    )
    (comp (ref "R99")
      (value "63.5k")
      (footprint "eagle-import:R0603")
      (libsource (lib "eagle-import") (part "rcl_R-US_R0603"))
    )
    (comp (ref "R169")
      (value "550")
      (footprint "eagle-import:R0603")
      (libsource (lib "eagle-import") (part "rcl_R-US_R0603"))
    )
    (comp (ref "R170")
      (value "10k")
      (footprint "eagle-import:R0603")
      (libsource (lib "eagle-import") (part "rcl_R-US_R0603"))
    )
    (comp (ref "R171")
      (value "180k")
      (footprint "eagle-import:R0603")
      (libsource (lib "eagle-import") (part "rcl_R-US_R0603"))
    )
    (comp (ref "R172")
      (value "10k")
      (footprint "eagle-import:R0603")
      (libsource (lib "eagle-import") (part "rcl_R-US_R0603"))
    )
    (comp (ref "R173")
      (value "550")
      (footprint "eagle-import:R0603")
      (libsource (lib "eagle-import") (part "rcl_R-US_R0603"))
    )
    (comp (ref "R174")
      (value "180k")
      (footprint "eagle-import:R0603")
      (libsource (lib "eagle-import") (part "rcl_R-US_R0603"))
    )
    (comp (ref "R175")
      (value "10k")
      (footprint "eagle-import:R0603")
      (libsource (lib "eagle-import") (part "rcl_R-US_R0603"))
    )
    (comp (ref "R176")
      (value "10k")
      (footprint "eagle-import:R0603")
      (libsource (lib "eagle-import") (part "rcl_R-US_R0603"))
    )
    (comp (ref "R177")
      (value "550")
      (footprint "eagle-import:R0603")
      (libsource (lib "eagle-import") (part "rcl_R-US_R0603"))
    )
    (comp (ref "R178")
      (value "10k")
      (footprint "eagle-import:R0603")
      (libsource (lib "eagle-import") (part "rcl_R-US_R0603"))
    )
    (comp (ref "R180")
      (value "180k")
      (footprint "eagle-import:R0603")
      (libsource (lib "eagle-import") (part "rcl_R-US_R0603"))
    )
    (comp (ref "R181")
      (value "10k")
      (footprint "eagle-import:R0603")
      (libsource (lib "eagle-import") (part "rcl_R-US_R0603"))
    )
    (comp (ref "R183")
      (value "100k")
      (footprint "eagle-import:R0603")
      (libsource (lib "eagle-import") (part "rcl_R-US_R0603"))
    )
    (comp (ref "R184")
      (value "550")
      (footprint "eagle-import:R0603")
      (libsource (lib "eagle-import") (part "rcl_R-US_R0603"))
    )
    (comp (ref "R185")
      (value "10k")
      (footprint "eagle-import:R0603")
      (libsource (lib "eagle-import") (part "rcl_R-US_R0603"))
    )
    (comp (ref "R186")
      (value "180k")
      (footprint "eagle-import:R0603")
      (libsource (lib "eagle-import") (part "rcl_R-US_R0603"))
    )
    (comp (ref "R187")
      (value "550")
      (footprint "eagle-import:R0603")
      (libsource (lib "eagle-import") (part "rcl_R-US_R0603"))
    )
    (comp (ref "R188")
      (value "10k")
      (footprint "eagle-import:R0603")
      (libsource (lib "eagle-import") (part "rcl_R-US_R0603"))
    )
    (comp (ref "R189")
      (value "100k")
      (footprint "eagle-import:R0603")
      (libsource (lib "eagle-import") (part "rcl_R-US_R0603"))
    )
    (comp (ref "R190")
      (value "100k")
      (footprint "eagle-import:R0603")
      (libsource (lib "eagle-import") (part "rcl_R-US_R0603"))
    )
    (comp (ref "R191")
      (value "63.5k")
      (footprint "eagle-import:R0603")
      (libsource (lib "eagle-import") (part "rcl_R-US_R0603"))
    )
    (comp (ref "R192")
      (value "63.5k")
      (footprint "eagle-import:R0603")
      (libsource (lib "eagle-import") (part "rcl_R-US_R0603"))
    )
    (comp (ref "R194")
      (value "63.5k")
      (footprint "eagle-import:R0603")
      (libsource (lib "eagle-import") (part "rcl_R-US_R0603"))
    )
    (comp (ref "U$1")
      (value "DMMT3904W-7-F")
      (footprint "eagle-import:SOT65P210X100-6N")
      (libsource (lib "eagle-import") (part "DMMT3904W-7-F"))
    )
    (comp (ref "U$3")
      (value "DMMT3904W-7-F")
      (footprint "eagle-import:SOT65P210X100-6N")
      (libsource (lib "eagle-import") (part "DMMT3904W-7-F"))
    )
    (comp (ref "U$4")
      (value "DMMT3904W-7-F")
      (footprint "eagle-import:SOT65P210X100-6N")
      (libsource (lib "eagle-import") (part "DMMT3904W-7-F"))
    )
    (comp (ref "U$7")
      (value "DMMT3904W-7-F")
      (footprint "eagle-import:SOT65P210X100-6N")
      (libsource (lib "eagle-import") (part "DMMT3904W-7-F"))
    )
    (comp (ref "U$8")
      (value "DMMT3904W-7-F")
      (footprint "eagle-import:SOT65P210X100-6N")
      (libsource (lib "eagle-import") (part "DMMT3904W-7-F"))
    )
    (comp (ref "U$9")
      (value "DMMT3904W-7-F")
      (footprint "eagle-import:SOT65P210X100-6N")
      (libsource (lib "eagle-import") (part "DMMT3904W-7-F"))
    )
    (comp (ref "U$15")
      (value "DMMT3904W-7-F")
      (footprint "eagle-import:SOT65P210X100-6N")
      (libsource (lib "eagle-import") (part "DMMT3904W-7-F"))
    )
    (comp (ref "U$16")
      (value "DMMT3904W-7-F")
      (footprint "eagle-import:SOT65P210X100-6N")
      (libsource (lib "eagle-import") (part "DMMT3904W-7-F"))
    )
    (comp (ref "U$19")
      (value "LM4819MMX")
      (footprint "eagle-import:SOP65P490X110-8N")
      (libsource (lib "eagle-import") (part "LM4819MMX"))
    )
    (comp (ref "U1")
      (value "TLV274IPWR")
      (footprint "eagle-import:SOP65P640X120-14N")
      (libsource (lib "eagle-import") (part "TLV274IPWR"))
    )
    (comp (ref "U2")
      (value "DMMT3906W-7-F")
      (footprint "eagle-import:SOT65P210X110-6N")
      (libsource (lib "eagle-import") (part "DMMT3906W-7-F"))
    )
    (comp (ref "U3")
      (value "DMMT3906W-7-F")
      (footprint "eagle-import:SOT65P210X110-6N")
      (libsource (lib "eagle-import") (part "DMMT3906W-7-F"))
    )
    (comp (ref "U4")
      (value "TLV274IPWR")
      (footprint "eagle-import:SOP65P640X120-14N")
      (libsource (lib "eagle-import") (part "TLV274IPWR"))
    )
    (comp (ref "U6")
      (value "DMMT3906W-7-F")
      (footprint "eagle-import:SOT65P210X110-6N")
      (libsource (lib "eagle-import") (part "DMMT3906W-7-F"))
    )
    (comp (ref "U7")
      (value "DMMT3906W-7-F")
      (footprint "eagle-import:SOT65P210X110-6N")
      (libsource (lib "eagle-import") (part "DMMT3906W-7-F"))
    )
    (comp (ref "U8")
      (value "TLV274IPWR")
      (footprint "eagle-import:SOP65P640X120-14N")
      (libsource (lib "eagle-import") (part "TLV274IPWR"))
    )
    (comp (ref "U9")
      (value "TLV274IPWR")
      (footprint "eagle-import:SOP65P640X120-14N")
      (libsource (lib "eagle-import") (part "TLV274IPWR"))
    )
    (comp (ref "U10")
      (value "DMMT3906W-7-F")
      (footprint "eagle-import:SOT65P210X110-6N")
      (libsource (lib "eagle-import") (part "DMMT3906W-7-F"))
    )
    (comp (ref "U11")
      (value "DMMT3906W-7-F")
      (footprint "eagle-import:SOT65P210X110-6N")
      (libsource (lib "eagle-import") (part "DMMT3906W-7-F"))
    )
    (comp (ref "U13")
      (value "TLV2471IDBVT")
      (footprint "eagle-import:SOT95P280X145-5N")
      (libsource (lib "eagle-import") (part "TLV2471IDBVT"))
    )
    (comp (ref "U14")
      (value "TLV274IPWR")
      (footprint "eagle-import:SOP65P640X120-14N")
      (libsource (lib "eagle-import") (part "TLV274IPWR"))
    )
    (comp (ref "U15")
      (value "TLV274IPWR")
      (footprint "eagle-import:SOP65P640X120-14N")
      (libsource (lib "eagle-import") (part "TLV274IPWR"))
    )
    (comp (ref "U16")
      (value "DMMT3906W-7-F")
      (footprint "eagle-import:SOT65P210X110-6N")
      (libsource (lib "eagle-import") (part "DMMT3906W-7-F"))
    )
    (comp (ref "U17")
      (value "DMMT3906W-7-F")
      (footprint "eagle-import:SOT65P210X110-6N")
      (libsource (lib "eagle-import") (part "DMMT3906W-7-F"))
    )
    (comp (ref "U18")
      (value "TLV274IPWR")
      (footprint "eagle-import:SOP65P640X120-14N")
      (libsource (lib "eagle-import") (part "TLV274IPWR"))
    )
    (comp (ref "U21")
      (value "DMMT3906W-7-F")
      (footprint "eagle-import:SOT65P210X110-6N")
      (libsource (lib "eagle-import") (part "DMMT3906W-7-F"))
    )
    (comp (ref "U22")
      (value "DMMT3906W-7-F")
      (footprint "eagle-import:SOT65P210X110-6N")
      (libsource (lib "eagle-import") (part "DMMT3906W-7-F"))
    )
    (comp (ref "U24")
      (value "DMMT3906W-7-F")
      (footprint "eagle-import:SOT65P210X110-6N")
      (libsource (lib "eagle-import") (part "DMMT3906W-7-F"))
    )
    (comp (ref "U25")
      (value "DMMT3906W-7-F")
      (footprint "eagle-import:SOT65P210X110-6N")
      (libsource (lib "eagle-import") (part "DMMT3906W-7-F"))
    )
    (comp (ref "U27")
      (value "DMMT3906W-7-F")
      (footprint "eagle-import:SOT65P210X110-6N")
      (libsource (lib "eagle-import") (part "DMMT3906W-7-F"))
    )
    (comp (ref "U28")
      (value "DMMT3906W-7-F")
      (footprint "eagle-import:SOT65P210X110-6N")
      (libsource (lib "eagle-import") (part "DMMT3906W-7-F"))
    )
    (comp (ref "U30")
      (value "DMMT3906W-7-F")
      (footprint "eagle-import:SOT65P210X110-6N")
      (libsource (lib "eagle-import") (part "DMMT3906W-7-F"))
    )
    (comp (ref "U31")
      (value "DMMT3906W-7-F")
      (footprint "eagle-import:SOT65P210X110-6N")
      (libsource (lib "eagle-import") (part "DMMT3906W-7-F"))
    )
    (comp (ref "C30")
      (value "1u")
      (footprint "eagle-import:C0603")
      (libsource (lib "eagle-import") (part "C-EUC0603"))
    )
    (comp (ref "C32")
      (value "1uF")
      (footprint "eagle-import:0603-NO")
      (libsource (lib "eagle-import") (part "CAP_CERAMIC0603_NO"))
    )
    (comp (ref "C49")
      (value "22pF")
      (footprint "eagle-import:0603-NO")
      (libsource (lib "eagle-import") (part "CAP_CERAMIC0603_NO"))
    )
    (comp (ref "C50")
      (value "22pF")
      (footprint "eagle-import:0603-NO")
      (libsource (lib "eagle-import") (part "CAP_CERAMIC0603_NO"))
    )
    (comp (ref "C51")
      (value "10u")
      (footprint "eagle-import:C0603")
      (libsource (lib "eagle-import") (part "C-EUC0603"))
    )
    (comp (ref "CN1")
      (value "AUDIO_3.5MMJACK")
      (footprint "eagle-import:4UCONN_19269")
      (libsource (lib "eagle-import") (part "AUDIO_3.5MMJACK"))
    )
    (comp (ref "D10")
      (value "DIODESOD-523")
      (footprint "eagle-import:SOD-523")
      (libsource (lib "eagle-import") (part "DIODESOD-523"))
    )
    (comp (ref "IC3")
      (value "74AHC1G125")
      (footprint "eagle-import:SOT23-5L")
      (libsource (lib "eagle-import") (part "74AHC1G125"))
    )
    (comp (ref "J100")
      (value "PINHEAD-2x5-P1.27")
      (footprint "eagle-import:PINHEAD_2X05_127")
      (libsource (lib "eagle-import") (part "0171_PH127-205DF055G00AROUND-PADS"))
    )
    (comp (ref "JP1")
      (value "PINHD-2X20")
      (footprint "eagle-import:2X20")
      (libsource (lib "eagle-import") (part "PINHD-2X20"))
    )
    (comp (ref "L")
      (value "RED")
      (footprint "eagle-import:CHIP-LED0805")
      (libsource (lib "eagle-import") (part "LEDCHIP-LED0805"))
    )
    (comp (ref "OK1")
      (value "6N137")
      (footprint "eagle-import:DIL8-SMD")
      (libsource (lib "eagle-import") (part "6N137"))
    )
    (comp (ref "R64")
      (value "10k")
      (footprint "eagle-import:R0603")
      (libsource (lib "eagle-import") (part "R-US_R0603"))
    )
    (comp (ref "R164")
      (value "2.2k")
      (footprint "eagle-import:R0603")
      (libsource (lib "eagle-import") (part "R-US_R0603"))
    )
    (comp (ref "R165")
      (value "220")
      (footprint "eagle-import:R0603")
      (libsource (lib "eagle-import") (part "R-US_R0603"))
    )
    (comp (ref "R179")
      (value "330")
      (footprint "eagle-import:R0603")
      (libsource (lib "eagle-import") (part "R-US_R0603"))
    )
    (comp (ref "R182")
      (value "10k")
      (footprint "eagle-import:R0603")
      (libsource (lib "eagle-import") (part "R-US_R0603"))
    )
    (comp (ref "RN2")
      (value "33")
      (footprint "eagle-import:0603-ARC")
      (libsource (lib "eagle-import") (part "4R-N0603-ARC"))
    )
    (comp (ref "SAMD21")
      (value "ATSAMD21G18_QFN")
      (footprint "eagle-import:TQFN48_7MM")
      (libsource (lib "eagle-import") (part "ATSAMD21J_QFN"))
    )
    (comp (ref "SW1")
      (value "SPST_TACT-KMR2")
      (footprint "eagle-import:KMR2")
      (libsource (lib "eagle-import") (part "SPST_TACT-KMR2"))
    )
    (comp (ref "X2")
      (value "32.768")
      (footprint "eagle-import:XTAL3215")
      (libsource (lib "eagle-import") (part "XTAL-3.2X1.5"))
    )
    (comp (ref "X3")
      (value "microUSB")
      (footprint "eagle-import:4UCONN_20329_V2")
      (libsource (lib "eagle-import") (part "USB_MICRO_20329_V2"))
    )
    (comp (ref "X4")
      (value "microsd")
      (footprint "eagle-import:MICROSD")
      (libsource (lib "eagle-import") (part "MICROSD"))
    )
  )
  (nets
    (net (code "1") (name "+1.2V") (class "Default")
      (node (ref "1.2V") (pin "TP") (pinfunction "TP_TP") (pintype "input"))
      (node (ref "C28") (pin "2") (pinfunction "2_2") (pintype "passive"))
      (node (ref "C41") (pin "2") (pinfunction "2_2") (pintype "passive"))
      (node (ref "C42") (pin "2") (pinfunction "2_2") (pintype "passive"))
      (node (ref "C48") (pin "2") (pinfunction "2_2") (pintype "passive"))
      (node (ref "C54") (pin "2") (pinfunction "2_2") (pintype "passive"))
      (node (ref "R8") (pin "2") (pinfunction "2_2") (pintype "passive"))
      (node (ref "R9") (pin "2") (pinfunction "2_2") (pintype "passive"))
      (node (ref "U$2") (pin "111") (pinfunction "VCC_111") (pintype "bidirectional"))
      (node (ref "U$2") (pin "27") (pinfunction "VCC_27") (pintype "bidirectional"))
      (node (ref "U$2") (pin "40") (pinfunction "VCC_40") (pintype "bidirectional"))
      (node (ref "U$2") (pin "92") (pinfunction "VCC_92") (pintype "bidirectional"))
      (node (ref "U12") (pin "6") (pinfunction "OUT1_6") (pintype "output"))
    )
    (net (code "2") (name "+2.5V") (class "Default")
      (node (ref "2.5V") (pin "TP") (pinfunction "TP_TP") (pintype "input"))
      (node (ref "C27") (pin "2") (pinfunction "2_2") (pintype "passive"))
      (node (ref "U12") (pin "5") (pinfunction "OUT2_5") (pintype "output"))
    )
    (net (code "3") (name "+3.3V") (class "Default")
      (node (ref "C13") (pin "2") (pinfunction "2_2") (pintype "passive"))
      (node (ref "C14") (pin "2") (pinfunction "2_2") (pintype "passive"))
      (node (ref "C15") (pin "2") (pinfunction "2_2") (pintype "passive"))
      (node (ref "C16") (pin "2") (pinfunction "2_2") (pintype "passive"))
      (node (ref "C17") (pin "2") (pinfunction "2_2") (pintype "passive"))
      (node (ref "C18") (pin "2") (pinfunction "2_2") (pintype "passive"))
      (node (ref "C19") (pin "2") (pinfunction "2_2") (pintype "passive"))
      (node (ref "C20") (pin "2") (pinfunction "2_2") (pintype "passive"))
      (node (ref "C25") (pin "2") (pinfunction "2_2") (pintype "passive"))
      (node (ref "C33") (pin "2") (pinfunction "2_2") (pintype "passive"))
      (node (ref "C34") (pin "2") (pinfunction "2_2") (pintype "passive"))
      (node (ref "C51") (pin "1") (pinfunction "1_1") (pintype "passive"))
      (node (ref "C62") (pin "1") (pinfunction "1_1") (pintype "passive"))
      (node (ref "C64") (pin "1") (pinfunction "1_1") (pintype "passive"))
      (node (ref "C66") (pin "1") (pinfunction "1_1") (pintype "passive"))
      (node (ref "C73") (pin "1") (pinfunction "1_1") (pintype "passive"))
      (node (ref "C74") (pin "1") (pinfunction "1_1") (pintype "passive"))
      (node (ref "C77") (pin "1") (pinfunction "1_1") (pintype "passive"))
      (node (ref "C78") (pin "1") (pinfunction "1_1") (pintype "passive"))
      (node (ref "C82") (pin "1") (pinfunction "1_1") (pintype "passive"))
      (node (ref "D2") (pin "A") (pinfunction "A_A") (pintype "passive"))
      (node (ref "IC1") (pin "5") (pinfunction "VCC_5") (pintype "power_in"))
      (node (ref "IC3") (pin "5") (pinfunction "VCC_5") (pintype "power_in"))
      (node (ref "IC4") (pin "5") (pinfunction "VCC_5") (pintype "power_in"))
      (node (ref "J100") (pin "1") (pinfunction "1_1") (pintype "passive"))
      (node (ref "JP1") (pin "1") (pinfunction "1_1") (pintype "passive"))
      (node (ref "JP1") (pin "38") (pinfunction "38_38") (pintype "passive"))
      (node (ref "OK1") (pin "8") (pinfunction "VCC_8") (pintype "passive"))
      (node (ref "R10") (pin "2") (pinfunction "2_2") (pintype "passive"))
      (node (ref "R11") (pin "2") (pinfunction "2_2") (pintype "passive"))
      (node (ref "R166") (pin "2") (pinfunction "2_2") (pintype "passive"))
      (node (ref "R167") (pin "2") (pinfunction "2_2") (pintype "passive"))
      (node (ref "R172") (pin "1") (pinfunction "1_1") (pintype "passive"))
      (node (ref "R176") (pin "2") (pinfunction "2_2") (pintype "passive"))
      (node (ref "R181") (pin "1") (pinfunction "1_1") (pintype "passive"))
      (node (ref "R182") (pin "1") (pinfunction "1_1") (pintype "passive"))
      (node (ref "R188") (pin "1") (pinfunction "1_1") (pintype "passive"))
      (node (ref "R189") (pin "1") (pinfunction "1_1") (pintype "passive"))
      (node (ref "R57") (pin "2") (pinfunction "2_2") (pintype "passive"))
      (node (ref "R58") (pin "2") (pinfunction "2_2") (pintype "passive"))
      (node (ref "R59") (pin "2") (pinfunction "2_2") (pintype "passive"))
      (node (ref "R60") (pin "2") (pinfunction "2_2") (pintype "passive"))
      (node (ref "R61") (pin "2") (pinfunction "2_2") (pintype "passive"))
      (node (ref "R64") (pin "2") (pinfunction "2_2") (pintype "passive"))
      (node (ref "R67") (pin "2") (pinfunction "2_2") (pintype "passive"))
      (node (ref "RAM1") (pin "8") (pinfunction "VCC_8") (pintype "bidirectional"))
      (node (ref "SAMD21") (pin "17") (pinfunction "VDDIO_17") (pintype "power_in"))
      (node (ref "SAMD21") (pin "36") (pinfunction "VDDIO_36") (pintype "power_in"))
      (node (ref "SAMD21") (pin "44") (pinfunction "VDDIN_44") (pintype "power_in"))
      (node (ref "SAMD21") (pin "6") (pinfunction "VDDA_6") (pintype "power_in"))
      (node (ref "U$19") (pin "6") (pinfunction "VDD_6") (pintype "bidirectional"))
      (node (ref "U$2") (pin "100") (pinfunction "VCCIO_1_2_100") (pintype "bidirectional"))
      (node (ref "U$2") (pin "123") (pinfunction "VCCIO_0_123") (pintype "bidirectional"))
      (node (ref "U$2") (pin "131") (pinfunction "VCCIO_0_2_131") (pintype "bidirectional"))
      (node (ref "U$2") (pin "30") (pinfunction "VCCIO_3_2_30") (pintype "bidirectional"))
      (node (ref "U$2") (pin "46") (pinfunction "VCCIO_2_46") (pintype "bidirectional"))
      (node (ref "U$2") (pin "57") (pinfunction "VCCIO2_2_57") (pintype "bidirectional"))
      (node (ref "U$2") (pin "6") (pinfunction "VCCIO_3_6") (pintype "bidirectional"))
      (node (ref "U$2") (pin "72") (pinfunction "VCC_SPI_72") (pintype "bidirectional"))
      (node (ref "U$2") (pin "89") (pinfunction "VCCIO_1_89") (pintype "bidirectional"))
      (node (ref "U$5") (pin "4") (pinfunction "VDD_4") (pintype "bidirectional"))
      (node (ref "U1") (pin "4") (pinfunction "V+_4") (pintype "bidirectional"))
      (node (ref "U11") (pin "4") (pinfunction "E_4") (pintype "passive"))
      (node (ref "U11") (pin "5") (pinfunction "E_5") (pintype "passive"))
      (node (ref "U12") (pin "2") (pinfunction "IN_2") (pintype "power_in"))
      (node (ref "U13") (pin "5") (pinfunction "V+_5") (pintype "bidirectional"))
      (node (ref "U14") (pin "4") (pinfunction "V+_4") (pintype "bidirectional"))
      (node (ref "U15") (pin "4") (pinfunction "V+_4") (pintype "bidirectional"))
      (node (ref "U17") (pin "4") (pinfunction "E_4") (pintype "passive"))
      (node (ref "U17") (pin "5") (pinfunction "E_5") (pintype "passive"))
      (node (ref "U18") (pin "4") (pinfunction "V+_4") (pintype "bidirectional"))
      (node (ref "U22") (pin "4") (pinfunction "E_4") (pintype "passive"))
      (node (ref "U22") (pin "5") (pinfunction "E_5") (pintype "passive"))
      (node (ref "U25") (pin "4") (pinfunction "E_4") (pintype "passive"))
      (node (ref "U25") (pin "5") (pinfunction "E_5") (pintype "passive"))
      (node (ref "U28") (pin "4") (pinfunction "E_4") (pintype "passive"))
      (node (ref "U28") (pin "5") (pinfunction "E_5") (pintype "passive"))
      (node (ref "U3") (pin "4") (pinfunction "E_4") (pintype "passive"))
      (node (ref "U3") (pin "5") (pinfunction "E_5") (pintype "passive"))
      (node (ref "U31") (pin "4") (pinfunction "E_4") (pintype "passive"))
      (node (ref "U31") (pin "5") (pinfunction "E_5") (pintype "passive"))
      (node (ref "U4") (pin "4") (pinfunction "V+_4") (pintype "bidirectional"))
      (node (ref "U7") (pin "4") (pinfunction "E_4") (pintype "passive"))
      (node (ref "U7") (pin "5") (pinfunction "E_5") (pintype "passive"))
      (node (ref "U8") (pin "4") (pinfunction "V+_4") (pintype "bidirectional"))
      (node (ref "U9") (pin "4") (pinfunction "V+_4") (pintype "bidirectional"))
      (node (ref "X4") (pin "4") (pinfunction "SD_VDD_4") (pintype "power_in"))
    )
    (net (code "4") (name "2P") (class "Default")
      (node (ref "C23") (pin "2") (pinfunction "2_2") (pintype "passive"))
      (node (ref "C24") (pin "2") (pinfunction "2_2") (pintype "passive"))
      (node (ref "JP1") (pin "39") (pinfunction "39_39") (pintype "passive"))
      (node (ref "R16") (pin "2") (pinfunction "2_2") (pintype "passive"))
      (node (ref "U15") (pin "14") (pinfunction "OUT_14") (pintype "output"))
    )
    (net (code "5") (name "4P") (class "Default")
      (node (ref "C21") (pin "2") (pinfunction "2_2") (pintype "passive"))
      (node (ref "C40") (pin "2") (pinfunction "2_2") (pintype "passive"))
      (node (ref "C47") (pin "1") (pinfunction "1_1") (pintype "passive"))
      (node (ref "C55") (pin "2") (pinfunction "2_2") (pintype "passive"))
      (node (ref "JP1") (pin "40") (pinfunction "40_40") (pintype "passive"))
      (node (ref "R28") (pin "2") (pinfunction "2_2") (pintype "passive"))
      (node (ref "U15") (pin "8") (pinfunction "OUT_8") (pintype "output"))
    )
    (net (code "6") (name "A1") (class "Default")
      (node (ref "JP1") (pin "16") (pinfunction "16_16") (pintype "passive"))
      (node (ref "SAMD21") (pin "7") (pinfunction "PB08/I8/AIN2/SERCOM4.0_7") (pintype "bidirectional"))
    )
    (net (code "7") (name "A2") (class "Default")
      (node (ref "JP1") (pin "15") (pinfunction "15_15") (pintype "passive"))
      (node (ref "SAMD21") (pin "8") (pinfunction "PB09/I9/AIN3/SERCOM4.1_8") (pintype "bidirectional"))
    )
    (net (code "8") (name "A5") (class "Default")
      (node (ref "JP1") (pin "4") (pinfunction "4_4") (pintype "passive"))
      (node (ref "SAMD21") (pin "47") (pinfunction "PB02/I2/AIN10/SERCOM5.0_47") (pintype "bidirectional"))
    )
    (net (code "9") (name "AGND") (class "Default")
      (node (ref "C6") (pin "+") (pinfunction "+_+") (pintype "passive"))
      (node (ref "C60") (pin "2") (pinfunction "2_2") (pintype "passive"))
      (node (ref "C61") (pin "1") (pinfunction "1_1") (pintype "passive"))
      (node (ref "C62") (pin "2") (pinfunction "2_2") (pintype "passive"))
      (node (ref "C63") (pin "1") (pinfunction "1_1") (pintype "passive"))
      (node (ref "C64") (pin "2") (pinfunction "2_2") (pintype "passive"))
      (node (ref "C65") (pin "1") (pinfunction "1_1") (pintype "passive"))
      (node (ref "C66") (pin "2") (pinfunction "2_2") (pintype "passive"))
      (node (ref "C67") (pin "1") (pinfunction "1_1") (pintype "passive"))
      (node (ref "C72") (pin "1") (pinfunction "1_1") (pintype "passive"))
      (node (ref "C73") (pin "2") (pinfunction "2_2") (pintype "passive"))
      (node (ref "C74") (pin "2") (pinfunction "2_2") (pintype "passive"))
      (node (ref "C75") (pin "1") (pinfunction "1_1") (pintype "passive"))
      (node (ref "C76") (pin "1") (pinfunction "1_1") (pintype "passive"))
      (node (ref "C77") (pin "2") (pinfunction "2_2") (pintype "passive"))
      (node (ref "C78") (pin "2") (pinfunction "2_2") (pintype "passive"))
      (node (ref "C79") (pin "1") (pinfunction "1_1") (pintype "passive"))
      (node (ref "C89") (pin "2") (pinfunction "2_2") (pintype "passive"))
      (node (ref "JP1") (pin "35") (pinfunction "35_35") (pintype "passive"))
      (node (ref "R12") (pin "1") (pinfunction "1_1") (pintype "passive"))
      (node (ref "R169") (pin "2") (pinfunction "2_2") (pintype "passive"))
      (node (ref "R173") (pin "1") (pinfunction "1_1") (pintype "passive"))
      (node (ref "R177") (pin "2") (pinfunction "2_2") (pintype "passive"))
      (node (ref "R183") (pin "1") (pinfunction "1_1") (pintype "passive"))
      (node (ref "R184") (pin "1") (pinfunction "1_1") (pintype "passive"))
      (node (ref "R187") (pin "1") (pinfunction "1_1") (pintype "passive"))
      (node (ref "R41") (pin "2") (pinfunction "2_2") (pintype "passive"))
      (node (ref "R73") (pin "1") (pinfunction "1_1") (pintype "passive"))
      (node (ref "U$1") (pin "1") (pinfunction "B_1") (pintype "passive"))
      (node (ref "U$15") (pin "1") (pinfunction "B_1") (pintype "passive"))
      (node (ref "U$16") (pin "1") (pinfunction "B_1") (pintype "passive"))
      (node (ref "U$3") (pin "1") (pinfunction "B_1") (pintype "passive"))
      (node (ref "U$4") (pin "1") (pinfunction "B_1") (pintype "passive"))
      (node (ref "U$7") (pin "1") (pinfunction "B_1") (pintype "passive"))
      (node (ref "U$8") (pin "1") (pinfunction "B_1") (pintype "passive"))
      (node (ref "U$9") (pin "1") (pinfunction "B_1") (pintype "passive"))
      (node (ref "U1") (pin "10") (pinfunction "+IN_10") (pintype "input"))
      (node (ref "U1") (pin "12") (pinfunction "+IN_12") (pintype "input"))
      (node (ref "U1") (pin "3") (pinfunction "+IN_3") (pintype "input"))
      (node (ref "U1") (pin "5") (pinfunction "+IN_5") (pintype "input"))
      (node (ref "U10") (pin "2") (pinfunction "B_2") (pintype "passive"))
      (node (ref "U14") (pin "10") (pinfunction "+IN_10") (pintype "input"))
      (node (ref "U14") (pin "12") (pinfunction "+IN_12") (pintype "input"))
      (node (ref "U14") (pin "3") (pinfunction "+IN_3") (pintype "input"))
      (node (ref "U14") (pin "5") (pinfunction "+IN_5") (pintype "input"))
      (node (ref "U15") (pin "10") (pinfunction "+IN_10") (pintype "input"))
      (node (ref "U15") (pin "12") (pinfunction "+IN_12") (pintype "input"))
      (node (ref "U15") (pin "3") (pinfunction "+IN_3") (pintype "input"))
      (node (ref "U15") (pin "5") (pinfunction "+IN_5") (pintype "input"))
      (node (ref "U16") (pin "2") (pinfunction "B_2") (pintype "passive"))
      (node (ref "U18") (pin "13") (pinfunction "-IN_13") (pintype "input"))
      (node (ref "U18") (pin "14") (pinfunction "OUT_14") (pintype "output"))
      (node (ref "U18") (pin "3") (pinfunction "+IN_3") (pintype "input"))
      (node (ref "U2") (pin "2") (pinfunction "B_2") (pintype "passive"))
      (node (ref "U21") (pin "2") (pinfunction "B_2") (pintype "passive"))
      (node (ref "U24") (pin "2") (pinfunction "B_2") (pintype "passive"))
      (node (ref "U27") (pin "2") (pinfunction "B_2") (pintype "passive"))
      (node (ref "U30") (pin "2") (pinfunction "B_2") (pintype "passive"))
      (node (ref "U6") (pin "2") (pinfunction "B_2") (pintype "passive"))
      (node (ref "U8") (pin "10") (pinfunction "+IN_10") (pintype "input"))
      (node (ref "U8") (pin "12") (pinfunction "+IN_12") (pintype "input"))
      (node (ref "U8") (pin "3") (pinfunction "+IN_3") (pintype "input"))
      (node (ref "U8") (pin "5") (pinfunction "+IN_5") (pintype "input"))
      (node (ref "U9") (pin "10") (pinfunction "+IN_10") (pintype "input"))
      (node (ref "U9") (pin "12") (pinfunction "+IN_12") (pintype "input"))
      (node (ref "U9") (pin "3") (pinfunction "+IN_3") (pintype "input"))
      (node (ref "U9") (pin "5") (pinfunction "+IN_5") (pintype "input"))
    )
    (net (code "10") (name "AREF") (class "Default")
      (node (ref "C30") (pin "1") (pinfunction "1_1") (pintype "passive"))
      (node (ref "SAMD21") (pin "4") (pinfunction "PA03/EINT3/VREFA/AIN1_4") (pintype "bidirectional"))
    )
    (net (code "11") (name "AUDIO_OUT") (class "Default")
      (node (ref "C89") (pin "1") (pinfunction "1_1") (pintype "passive"))
      (node (ref "FB1") (pin "2") (pinfunction "P$2_2") (pintype "passive"))
      (node (ref "JP1") (pin "36") (pinfunction "36_36") (pintype "passive"))
      (node (ref "R66") (pin "2") (pinfunction "2_2") (pintype "passive"))
    )
    (net (code "12") (name "AUX") (class "Default")
      (node (ref "JP1") (pin "33") (pinfunction "33_33") (pintype "passive"))
      (node (ref "R194") (pin "2") (pinfunction "2_2") (pintype "passive"))
    )
    (net (code "13") (name "BIT0_0") (class "Default")
      (node (ref "RN7") (pin "8") (pinfunction "1_8") (pintype "passive"))
      (node (ref "U$2") (pin "1") (pinfunction "IOL_2A_1") (pintype "bidirectional"))
    )
    (net (code "14") (name "BIT0_1") (class "Default")
      (node (ref "RN11") (pin "8") (pinfunction "1_8") (pintype "passive"))
      (node (ref "U$2") (pin "110") (pinfunction "IOT_168_110") (pintype "bidirectional"))
    )
    (net (code "15") (name "BIT0_2") (class "Default")
      (node (ref "RN15") (pin "1") (pinfunction "1_1") (pintype "passive"))
      (node (ref "U$2") (pin "63") (pinfunction "IOB_103_CBSEL0_63") (pintype "bidirectional"))
    )
    (net (code "16") (name "BIT1_0") (class "Default")
      (node (ref "RN7") (pin "7") (pinfunction "1_7") (pintype "passive"))
      (node (ref "U$2") (pin "2") (pinfunction "IOL_2B_2") (pintype "bidirectional"))
    )
    (net (code "17") (name "BIT1_1") (class "Default")
      (node (ref "RN11") (pin "7") (pinfunction "1_7") (pintype "passive"))
      (node (ref "U$2") (pin "112") (pinfunction "IOT_169_112") (pintype "bidirectional"))
    )
    (net (code "18") (name "BIT1_2") (class "Default")
      (node (ref "RN15") (pin "2") (pinfunction "1_2") (pintype "passive"))
      (node (ref "U$2") (pin "62") (pinfunction "IOB_102_62") (pintype "bidirectional"))
    )
    (net (code "19") (name "BIT2_0") (class "Default")
      (node (ref "RN7") (pin "6") (pinfunction "1_6") (pintype "passive"))
      (node (ref "U$2") (pin "3") (pinfunction "IOL_3A_3") (pintype "bidirectional"))
    )
    (net (code "20") (name "BIT2_1") (class "Default")
      (node (ref "RN11") (pin "6") (pinfunction "1_6") (pintype "passive"))
      (node (ref "U$2") (pin "113") (pinfunction "IOT_170_113") (pintype "bidirectional"))
    )
    (net (code "21") (name "BIT2_2") (class "Default")
      (node (ref "RN15") (pin "3") (pinfunction "1_3") (pintype "passive"))
      (node (ref "U$2") (pin "61") (pinfunction "IOB_96_61") (pintype "bidirectional"))
    )
    (net (code "22") (name "BIT3_0") (class "Default")
      (node (ref "RN7") (pin "5") (pinfunction "1_5") (pintype "passive"))
      (node (ref "U$2") (pin "4") (pinfunction "IOL_3B_4") (pintype "bidirectional"))
    )
    (net (code "23") (name "BIT3_1") (class "Default")
      (node (ref "RN11") (pin "5") (pinfunction "1_5") (pintype "passive"))
      (node (ref "U$2") (pin "114") (pinfunction "IOT_171_114") (pintype "bidirectional"))
    )
    (net (code "24") (name "BIT3_2") (class "Default")
      (node (ref "RN15") (pin "4") (pinfunction "1_4") (pintype "passive"))
      (node (ref "U$2") (pin "60") (pinfunction "IOB_95_60") (pintype "bidirectional"))
    )
    (net (code "25") (name "BIT4_0") (class "Default")
      (node (ref "RN7") (pin "4") (pinfunction "1_4") (pintype "passive"))
      (node (ref "U$2") (pin "7") (pinfunction "IOL_4A_7") (pintype "bidirectional"))
    )
    (net (code "26") (name "BIT4_1") (class "Default")
      (node (ref "RN11") (pin "4") (pinfunction "1_4") (pintype "passive"))
      (node (ref "U$2") (pin "115") (pinfunction "IOT_172_115") (pintype "bidirectional"))
    )
    (net (code "27") (name "BIT4_2") (class "Default")
      (node (ref "RN15") (pin "5") (pinfunction "1_5") (pintype "passive"))
      (node (ref "U$2") (pin "56") (pinfunction "IOB_94_56") (pintype "bidirectional"))
    )
    (net (code "28") (name "BIT5_0") (class "Default")
      (node (ref "RN7") (pin "3") (pinfunction "1_3") (pintype "passive"))
      (node (ref "U$2") (pin "8") (pinfunction "IOL_4B_8") (pintype "bidirectional"))
    )
    (net (code "29") (name "BIT5_1") (class "Default")
      (node (ref "RN11") (pin "3") (pinfunction "1_3") (pintype "passive"))
      (node (ref "U$2") (pin "116") (pinfunction "IOT_173_116") (pintype "bidirectional"))
    )
    (net (code "30") (name "BIT5_2") (class "Default")
      (node (ref "RN15") (pin "6") (pinfunction "1_6") (pintype "passive"))
      (node (ref "U$2") (pin "55") (pinfunction "IOB_91_55") (pintype "bidirectional"))
    )
    (net (code "31") (name "BIT6_0") (class "Default")
      (node (ref "RN7") (pin "2") (pinfunction "1_2") (pintype "passive"))
      (node (ref "U$2") (pin "9") (pinfunction "IOL_5A_9") (pintype "bidirectional"))
    )
    (net (code "32") (name "BIT6_1") (class "Default")
      (node (ref "RN11") (pin "2") (pinfunction "1_2") (pintype "passive"))
      (node (ref "U$2") (pin "117") (pinfunction "IOT_174_117") (pintype "bidirectional"))
    )
    (net (code "33") (name "BIT6_2") (class "Default")
      (node (ref "RN15") (pin "7") (pinfunction "1_7") (pintype "passive"))
      (node (ref "U$2") (pin "48") (pinfunction "IOB_80_48") (pintype "bidirectional"))
    )
    (net (code "34") (name "BIT7_0") (class "Default")
      (node (ref "RN7") (pin "1") (pinfunction "1_1") (pintype "passive"))
      (node (ref "U$2") (pin "10") (pinfunction "IOL_5B_10") (pintype "bidirectional"))
    )
    (net (code "35") (name "BIT7_1") (class "Default")
      (node (ref "RN11") (pin "1") (pinfunction "1_1") (pintype "passive"))
      (node (ref "U$2") (pin "118") (pinfunction "IOT_177_118") (pintype "bidirectional"))
    )
    (net (code "36") (name "BIT7_2") (class "Default")
      (node (ref "RN15") (pin "8") (pinfunction "1_8") (pintype "passive"))
      (node (ref "U$2") (pin "47") (pinfunction "IOB_79_47") (pintype "bidirectional"))
    )
    (net (code "37") (name "BIT8_0") (class "Default")
      (node (ref "RN6") (pin "8") (pinfunction "1_8") (pintype "passive"))
      (node (ref "U$2") (pin "25") (pinfunction "IOL_18A_25") (pintype "bidirectional"))
    )
    (net (code "38") (name "BIT8_1") (class "Default")
      (node (ref "RN10") (pin "8") (pinfunction "1_8") (pintype "passive"))
      (node (ref "U$2") (pin "136") (pinfunction "IOT_214_136") (pintype "bidirectional"))
    )
    (net (code "39") (name "BIT8_2") (class "Default")
      (node (ref "RN14") (pin "1") (pinfunction "1_1") (pintype "passive"))
      (node (ref "U$2") (pin "45") (pinfunction "IOB_73_45") (pintype "bidirectional"))
    )
    (net (code "40") (name "BIT9_0") (class "Default")
      (node (ref "RN6") (pin "7") (pinfunction "1_7") (pintype "passive"))
      (node (ref "U$2") (pin "26") (pinfunction "IOL_18B_26") (pintype "bidirectional"))
    )
    (net (code "41") (name "BIT9_1") (class "Default")
      (node (ref "RN10") (pin "7") (pinfunction "1_7") (pintype "passive"))
      (node (ref "U$2") (pin "137") (pinfunction "IOT_215_137") (pintype "bidirectional"))
    )
    (net (code "42") (name "BIT9_2") (class "Default")
      (node (ref "RN14") (pin "2") (pinfunction "1_2") (pintype "passive"))
      (node (ref "U$2") (pin "44") (pinfunction "IOB_72_44") (pintype "bidirectional"))
    )
    (net (code "43") (name "BIT10_0") (class "Default")
      (node (ref "RN6") (pin "6") (pinfunction "1_6") (pintype "passive"))
      (node (ref "U$2") (pin "28") (pinfunction "IOL_23A_28") (pintype "bidirectional"))
    )
    (net (code "44") (name "BIT10_1") (class "Default")
      (node (ref "RN10") (pin "6") (pinfunction "1_6") (pintype "passive"))
      (node (ref "U$2") (pin "138") (pinfunction "IOT_216_138") (pintype "bidirectional"))
    )
    (net (code "45") (name "BIT10_2") (class "Default")
      (node (ref "RN14") (pin "3") (pinfunction "1_3") (pintype "passive"))
      (node (ref "U$2") (pin "43") (pinfunction "IOB_71_43") (pintype "bidirectional"))
    )
    (net (code "46") (name "BIT11_0") (class "Default")
      (node (ref "RN6") (pin "5") (pinfunction "1_5") (pintype "passive"))
      (node (ref "U$2") (pin "29") (pinfunction "IOL_23B_29") (pintype "bidirectional"))
    )
    (net (code "47") (name "BIT11_1") (class "Default")
      (node (ref "RN10") (pin "5") (pinfunction "1_5") (pintype "passive"))
      (node (ref "U$2") (pin "139") (pinfunction "IOT_217_139") (pintype "bidirectional"))
    )
    (net (code "48") (name "BIT11_2") (class "Default")
      (node (ref "RN14") (pin "4") (pinfunction "1_4") (pintype "passive"))
      (node (ref "U$2") (pin "42") (pinfunction "IOB_64_42") (pintype "bidirectional"))
    )
    (net (code "49") (name "BIT12_0") (class "Default")
      (node (ref "RN6") (pin "4") (pinfunction "1_4") (pintype "passive"))
      (node (ref "U$2") (pin "31") (pinfunction "IOL_24A_31") (pintype "bidirectional"))
    )
    (net (code "50") (name "BIT12_1") (class "Default")
      (node (ref "RN10") (pin "4") (pinfunction "1_4") (pintype "passive"))
      (node (ref "U$2") (pin "141") (pinfunction "IOT_219_141") (pintype "bidirectional"))
    )
    (net (code "51") (name "BIT12_2") (class "Default")
      (node (ref "RN14") (pin "5") (pinfunction "1_5") (pintype "passive"))
      (node (ref "U$2") (pin "41") (pinfunction "IOB_63_41") (pintype "bidirectional"))
    )
    (net (code "52") (name "BIT13_0") (class "Default")
      (node (ref "RN6") (pin "3") (pinfunction "1_3") (pintype "passive"))
      (node (ref "U$2") (pin "32") (pinfunction "IOL_24B_32") (pintype "bidirectional"))
    )
    (net (code "53") (name "BIT13_1") (class "Default")
      (node (ref "RN10") (pin "3") (pinfunction "1_3") (pintype "passive"))
      (node (ref "U$2") (pin "142") (pinfunction "IOT_220_142") (pintype "bidirectional"))
    )
    (net (code "54") (name "BIT13_2") (class "Default")
      (node (ref "RN14") (pin "6") (pinfunction "1_6") (pintype "passive"))
      (node (ref "U$2") (pin "39") (pinfunction "IOB_61_39") (pintype "bidirectional"))
    )
    (net (code "55") (name "BIT14_0") (class "Default")
      (node (ref "RN6") (pin "2") (pinfunction "1_2") (pintype "passive"))
      (node (ref "U$2") (pin "33") (pinfunction "IOL_25A_33") (pintype "bidirectional"))
    )
    (net (code "56") (name "BIT14_1") (class "Default")
      (node (ref "RN10") (pin "2") (pinfunction "1_2") (pintype "passive"))
      (node (ref "U$2") (pin "143") (pinfunction "IOT_221_143") (pintype "bidirectional"))
    )
    (net (code "57") (name "BIT14_2") (class "Default")
      (node (ref "RN14") (pin "7") (pinfunction "1_7") (pintype "passive"))
      (node (ref "U$2") (pin "38") (pinfunction "IOB_57_38") (pintype "bidirectional"))
    )
    (net (code "58") (name "BIT15_0") (class "Default")
      (node (ref "RN6") (pin "1") (pinfunction "1_1") (pintype "passive"))
      (node (ref "U$2") (pin "34") (pinfunction "IOL_25B_34") (pintype "bidirectional"))
    )
    (net (code "59") (name "BIT15_1") (class "Default")
      (node (ref "RN10") (pin "1") (pinfunction "1_1") (pintype "passive"))
      (node (ref "U$2") (pin "144") (pinfunction "IOT_222_144") (pintype "bidirectional"))
    )
    (net (code "60") (name "BIT15_2") (class "Default")
      (node (ref "RN14") (pin "8") (pinfunction "1_8") (pintype "passive"))
      (node (ref "U$2") (pin "37") (pinfunction "IOB_56_37") (pintype "bidirectional"))
    )
    (net (code "61") (name "CDONE") (class "Default")
      (node (ref "R10") (pin "1") (pinfunction "1_1") (pintype "passive"))
      (node (ref "SAMD21") (pin "10") (pinfunction "PA05/EINT5/AIN5/SERCOM0.1_10") (pintype "bidirectional"))
      (node (ref "U$2") (pin "65") (pinfunction "CDONE_65") (pintype "bidirectional"))
    )
    (net (code "62") (name "CLK_IN") (class "Default")
      (node (ref "CLK") (pin "TP") (pinfunction "TP_TP") (pintype "input"))
      (node (ref "U$2") (pin "21") (pinfunction "IOL_14A_GBIN6_21") (pintype "bidirectional"))
      (node (ref "U$5") (pin "3") (pinfunction "VOUT_3") (pintype "bidirectional"))
    )
    (net (code "63") (name "CRESET") (class "Default")
      (node (ref "R11") (pin "1") (pinfunction "1_1") (pintype "passive"))
      (node (ref "SAMD21") (pin "9") (pinfunction "PA04/EINT4/VREFB/AIN4/SERCOM0.0_9") (pintype "bidirectional"))
      (node (ref "U$2") (pin "66") (pinfunction "CRESET_B_66") (pintype "bidirectional"))
    )
    (net (code "64") (name "CUTOFF") (class "Default")
      (node (ref "R65") (pin "1") (pinfunction "1_1") (pintype "passive"))
      (node (ref "U$1") (pin "2") (pinfunction "B_2") (pintype "passive"))
      (node (ref "U$3") (pin "2") (pinfunction "B_2") (pintype "passive"))
      (node (ref "U$4") (pin "2") (pinfunction "B_2") (pintype "passive"))
      (node (ref "U$7") (pin "2") (pinfunction "B_2") (pintype "passive"))
      (node (ref "U10") (pin "1") (pinfunction "B_1") (pintype "passive"))
      (node (ref "U16") (pin "1") (pinfunction "B_1") (pintype "passive"))
      (node (ref "U2") (pin "1") (pinfunction "B_1") (pintype "passive"))
      (node (ref "U4") (pin "1") (pinfunction "OUT_1") (pintype "output"))
      (node (ref "U6") (pin "1") (pinfunction "B_1") (pintype "passive"))
    )
    (net (code "65") (name "D+") (class "Default")
      (node (ref "SAMD21") (pin "34") (pinfunction "PA25/I13/SERCOM3+5.3/D+_34") (pintype "bidirectional"))
      (node (ref "X3") (pin "D+") (pinfunction "D+_D+") (pintype "bidirectional"))
    )
    (net (code "66") (name "D-") (class "Default")
      (node (ref "SAMD21") (pin "33") (pinfunction "PA24/I12/SERCOM3+5.2/D-_33") (pintype "bidirectional"))
      (node (ref "X3") (pin "D-") (pinfunction "D-_D-") (pintype "bidirectional"))
    )
    (net (code "67") (name "D0") (class "Default")
      (node (ref "JP1") (pin "19") (pinfunction "19_19") (pintype "passive"))
      (node (ref "SAMD21") (pin "16") (pinfunction "PA11/I11/AIN19/SERCOM0+2.3/I2SF0_16") (pintype "bidirectional"))
    )
    (net (code "68") (name "D1") (class "Default")
      (node (ref "JP1") (pin "20") (pinfunction "20_20") (pintype "passive"))
      (node (ref "SAMD21") (pin "15") (pinfunction "PA10/I10/AIN18/SERCOM0+2.2/I2SCK_15") (pintype "bidirectional"))
    )
    (net (code "69") (name "D2") (class "Default")
      (node (ref "SAMD21") (pin "23") (pinfunction "PA14/I14/SERCOM2+4.2_23") (pintype "bidirectional"))
    )
    (net (code "70") (name "D3") (class "Default")
      (node (ref "JP1") (pin "17") (pinfunction "17_17") (pintype "passive"))
      (node (ref "SAMD21") (pin "14") (pinfunction "PA09/I2C/I9/AIN17/SERCOM0+2.1/I2SMC_14") (pintype "bidirectional"))
    )
    (net (code "71") (name "D4") (class "Default")
      (node (ref "JP1") (pin "18") (pinfunction "18_18") (pintype "passive"))
      (node (ref "SAMD21") (pin "13") (pinfunction "PA08/I2C/AIN16/SERCOM0+2.0/I2SD1_13") (pintype "bidirectional"))
    )
    (net (code "72") (name "D6") (class "Default")
      (node (ref "JP1") (pin "12") (pinfunction "12_12") (pintype "passive"))
      (node (ref "SAMD21") (pin "29") (pinfunction "PA20/I4/SERCOM3+5.2/I2SSC_29") (pintype "bidirectional"))
    )
    (net (code "73") (name "D7") (class "Default")
      (node (ref "JP1") (pin "11") (pinfunction "11_11") (pintype "passive"))
      (node (ref "SAMD21") (pin "30") (pinfunction "PA21/I5/SERCOM3+5.3/I2SFS0_30") (pintype "bidirectional"))
    )
    (net (code "74") (name "D8") (class "Default")
      (node (ref "JP1") (pin "22") (pinfunction "22_22") (pintype "passive"))
      (node (ref "SAMD21") (pin "11") (pinfunction "PA06/EINT6/AIN6/SERCOM0.2_11") (pintype "bidirectional"))
    )
    (net (code "75") (name "D9") (class "Default")
      (node (ref "SAMD21") (pin "12") (pinfunction "PA07/I7/AIN7/SERCOM0.3/I2SD0_12") (pintype "bidirectional"))
    )
    (net (code "76") (name "D13") (class "Default")
      (node (ref "R164") (pin "1") (pinfunction "1_1") (pintype "passive"))
      (node (ref "SAMD21") (pin "26") (pinfunction "PA17/I2C/I1/SERCOM1+3.1_26") (pintype "bidirectional"))
    )
    (net (code "77") (name "FPGA_105") (class "Default")
      (node (ref "JP1") (pin "10") (pinfunction "10_10") (pintype "passive"))
      (node (ref "U$2") (pin "105") (pinfunction "IOR_165_105") (pintype "bidirectional"))
    )
    (net (code "78") (name "FPGA_107") (class "Default")
      (node (ref "JP1") (pin "6") (pinfunction "6_6") (pintype "passive"))
      (node (ref "U$2") (pin "107") (pinfunction "IOR_167_107") (pintype "bidirectional"))
    )
    (net (code "79") (name "FPGA_CS") (class "Default")
      (node (ref "IC1") (pin "1") (pinfunction "~{OE}_1") (pintype "input"))
      (node (ref "RN4") (pin "8") (pinfunction "2_8") (pintype "passive"))
      (node (ref "SAMD21") (pin "27") (pinfunction "PA18/I2/SERCOM1+3.2_27") (pintype "bidirectional"))
    )
    (net (code "80") (name "FPGA_MISO") (class "Default")
      (node (ref "IC1") (pin "2") (pinfunction "A_2") (pintype "input"))
      (node (ref "RN4") (pin "7") (pinfunction "2_7") (pintype "passive"))
    )
    (net (code "81") (name "GND") (class "Default")
      (node (ref "C13") (pin "1") (pinfunction "1_1") (pintype "passive"))
      (node (ref "C14") (pin "1") (pinfunction "1_1") (pintype "passive"))
      (node (ref "C15") (pin "1") (pinfunction "1_1") (pintype "passive"))
      (node (ref "C16") (pin "1") (pinfunction "1_1") (pintype "passive"))
      (node (ref "C17") (pin "1") (pinfunction "1_1") (pintype "passive"))
      (node (ref "C18") (pin "1") (pinfunction "1_1") (pintype "passive"))
      (node (ref "C19") (pin "1") (pinfunction "1_1") (pintype "passive"))
      (node (ref "C20") (pin "1") (pinfunction "1_1") (pintype "passive"))
      (node (ref "C25") (pin "1") (pinfunction "1_1") (pintype "passive"))
      (node (ref "C27") (pin "1") (pinfunction "1_1") (pintype "passive"))
      (node (ref "C28") (pin "1") (pinfunction "1_1") (pintype "passive"))
      (node (ref "C29") (pin "2") (pinfunction "2_2") (pintype "passive"))
      (node (ref "C30") (pin "2") (pinfunction "2_2") (pintype "passive"))
      (node (ref "C31") (pin "2") (pinfunction "2_2") (pintype "passive"))
      (node (ref "C32") (pin "2") (pinfunction "2_2") (pintype "passive"))
      (node (ref "C33") (pin "1") (pinfunction "1_1") (pintype "passive"))
      (node (ref "C34") (pin "1") (pinfunction "1_1") (pintype "passive"))
      (node (ref "C41") (pin "1") (pinfunction "1_1") (pintype "passive"))
      (node (ref "C42") (pin "1") (pinfunction "1_1") (pintype "passive"))
      (node (ref "C48") (pin "1") (pinfunction "1_1") (pintype "passive"))
      (node (ref "C49") (pin "2") (pinfunction "2_2") (pintype "passive"))
      (node (ref "C5") (pin "2") (pinfunction "2_2") (pintype "passive"))
      (node (ref "C50") (pin "2") (pinfunction "2_2") (pintype "passive"))
      (node (ref "C51") (pin "2") (pinfunction "2_2") (pintype "passive"))
      (node (ref "C52") (pin "2") (pinfunction "2_2") (pintype "passive"))
      (node (ref "C54") (pin "1") (pinfunction "1_1") (pintype "passive"))
      (node (ref "C68") (pin "1") (pinfunction "1_1") (pintype "passive"))
      (node (ref "C69") (pin "1") (pinfunction "1_1") (pintype "passive"))
      (node (ref "C7") (pin "2") (pinfunction "2_2") (pintype "passive"))
      (node (ref "C70") (pin "1") (pinfunction "1_1") (pintype "passive"))
      (node (ref "C71") (pin "1") (pinfunction "1_1") (pintype "passive"))
      (node (ref "C8") (pin "2") (pinfunction "2_2") (pintype "passive"))
      (node (ref "C80") (pin "1") (pinfunction "1_1") (pintype "passive"))
      (node (ref "C81") (pin "2") (pinfunction "2_2") (pintype "passive"))
      (node (ref "CN2") (pin "2") (pinfunction "1_2") (pintype "passive"))
      (node (ref "FB3") (pin "1") (pinfunction "P$1_1") (pintype "passive"))
      (node (ref "IC1") (pin "3") (pinfunction "GND_3") (pintype "power_in"))
      (node (ref "IC2") (pin "2") (pinfunction "VSS_2") (pintype "power_in"))
      (node (ref "IC3") (pin "3") (pinfunction "GND_3") (pintype "power_in"))
      (node (ref "IC4") (pin "3") (pinfunction "GND_3") (pintype "power_in"))
      (node (ref "J100") (pin "3") (pinfunction "3_3") (pintype "passive"))
      (node (ref "J100") (pin "5") (pinfunction "5_5") (pintype "passive"))
      (node (ref "J100") (pin "9") (pinfunction "9_9") (pintype "passive"))
      (node (ref "JP1") (pin "2") (pinfunction "2_2") (pintype "passive"))
      (node (ref "L") (pin "C") (pinfunction "C_C") (pintype "passive"))
      (node (ref "OK1") (pin "5") (pinfunction "GND_5") (pintype "passive"))
      (node (ref "R31") (pin "1") (pinfunction "1_1") (pintype "passive"))
      (node (ref "R32") (pin "1") (pinfunction "1_1") (pintype "passive"))
      (node (ref "R33") (pin "1") (pinfunction "1_1") (pintype "passive"))
      (node (ref "R68") (pin "2") (pinfunction "2_2") (pintype "passive"))
      (node (ref "RAM1") (pin "4") (pinfunction "GND_4") (pintype "bidirectional"))
      (node (ref "S1") (pin "1") (pinfunction "O_1") (pintype "passive"))
      (node (ref "SAMD21") (pin "18") (pinfunction "GND_18") (pintype "power_in"))
      (node (ref "SAMD21") (pin "35") (pinfunction "GND_35") (pintype "power_in"))
      (node (ref "SAMD21") (pin "42") (pinfunction "GND_42") (pintype "power_in"))
      (node (ref "SAMD21") (pin "5") (pinfunction "GNDA_5") (pintype "power_in"))
      (node (ref "SAMD21") (pin "THERMAL") (pinfunction "GND_THERMAL") (pintype "power_in"))
      (node (ref "SW1") (pin "2") (pinfunction "S_2") (pintype "passive"))
      (node (ref "SW1") (pin "4") (pinfunction "S1_4") (pintype "passive"))
      (node (ref "U$2") (pin "103") (pinfunction "GND_2_103") (pintype "bidirectional"))
      (node (ref "U$2") (pin "13") (pinfunction "GND_2_13") (pintype "bidirectional"))
      (node (ref "U$2") (pin "132") (pinfunction "GND_132") (pintype "bidirectional"))
      (node (ref "U$2") (pin "14") (pinfunction "GND_3_14") (pintype "bidirectional"))
      (node (ref "U$2") (pin "140") (pinfunction "GND_2_140") (pintype "bidirectional"))
      (node (ref "U$2") (pin "5") (pinfunction "GND_5") (pintype "bidirectional"))
      (node (ref "U$2") (pin "59") (pinfunction "GND_59") (pintype "bidirectional"))
      (node (ref "U$2") (pin "69") (pinfunction "GND_69") (pintype "bidirectional"))
      (node (ref "U$2") (pin "86") (pinfunction "GND_86") (pintype "bidirectional"))
      (node (ref "U$5") (pin "2") (pinfunction "GND_2") (pintype "bidirectional"))
      (node (ref "U12") (pin "4") (pinfunction "GND_4") (pintype "passive"))
      (node (ref "U5") (pin "2") (pinfunction "GND_2") (pintype "power_in"))
      (node (ref "X3") (pin "BASE@1") (pinfunction "GND_BASE@1") (pintype "power_in"))
      (node (ref "X3") (pin "BASE@2") (pinfunction "GND_BASE@2") (pintype "power_in"))
      (node (ref "X3") (pin "GND") (pinfunction "GND_GND") (pintype "power_in"))
      (node (ref "X3") (pin "SPRT@1") (pinfunction "GND_SPRT@1") (pintype "power_in"))
      (node (ref "X3") (pin "SPRT@2") (pinfunction "GND_SPRT@2") (pintype "power_in"))
      (node (ref "X3") (pin "SPRT@3") (pinfunction "GND_SPRT@3") (pintype "power_in"))
      (node (ref "X3") (pin "SPRT@4") (pinfunction "GND_SPRT@4") (pintype "power_in"))
      (node (ref "X4") (pin "6") (pinfunction "GND_6") (pintype "power_in"))
      (node (ref "X4") (pin "MT1") (pinfunction "GND_MT1") (pintype "power_in"))
      (node (ref "X4") (pin "MT2") (pinfunction "GND_MT2") (pintype "power_in"))
    )
    (net (code "82") (name "GND2") (class "Default")
      (node (ref "C6") (pin "-") (pinfunction "-_-") (pintype "passive"))
      (node (ref "C61") (pin "2") (pinfunction "2_2") (pintype "passive"))
      (node (ref "C63") (pin "2") (pinfunction "2_2") (pintype "passive"))
      (node (ref "C65") (pin "2") (pinfunction "2_2") (pintype "passive"))
      (node (ref "C67") (pin "2") (pinfunction "2_2") (pintype "passive"))
      (node (ref "C72") (pin "2") (pinfunction "2_2") (pintype "passive"))
      (node (ref "C75") (pin "2") (pinfunction "2_2") (pintype "passive"))
      (node (ref "C76") (pin "2") (pinfunction "2_2") (pintype "passive"))
      (node (ref "C79") (pin "2") (pinfunction "2_2") (pintype "passive"))
      (node (ref "C82") (pin "2") (pinfunction "2_2") (pintype "passive"))
      (node (ref "FB3") (pin "2") (pinfunction "P$2_2") (pintype "passive"))
      (node (ref "JP1") (pin "37") (pinfunction "37_37") (pintype "passive"))
      (node (ref "R15") (pin "1") (pinfunction "1_1") (pintype "passive"))
      (node (ref "R190") (pin "2") (pinfunction "2_2") (pintype "passive"))
      (node (ref "R21") (pin "1") (pinfunction "1_1") (pintype "passive"))
      (node (ref "R27") (pin "1") (pinfunction "1_1") (pintype "passive"))
      (node (ref "R37") (pin "1") (pinfunction "1_1") (pintype "passive"))
      (node (ref "R49") (pin "1") (pinfunction "1_1") (pintype "passive"))
      (node (ref "R53") (pin "1") (pinfunction "1_1") (pintype "passive"))
      (node (ref "R6") (pin "1") (pinfunction "1_1") (pintype "passive"))
      (node (ref "R62") (pin "1") (pinfunction "1_1") (pintype "passive"))
      (node (ref "U$19") (pin "1") (pinfunction "SHUTDOWN_1") (pintype "bidirectional"))
      (node (ref "U$19") (pin "7") (pinfunction "GND_7") (pintype "bidirectional"))
      (node (ref "U1") (pin "11") (pinfunction "V-_11") (pintype "bidirectional"))
      (node (ref "U13") (pin "2") (pinfunction "V-_2") (pintype "bidirectional"))
      (node (ref "U14") (pin "11") (pinfunction "V-_11") (pintype "bidirectional"))
      (node (ref "U15") (pin "11") (pinfunction "V-_11") (pintype "bidirectional"))
      (node (ref "U18") (pin "11") (pinfunction "V-_11") (pintype "bidirectional"))
      (node (ref "U4") (pin "11") (pinfunction "V-_11") (pintype "bidirectional"))
      (node (ref "U8") (pin "11") (pinfunction "V-_11") (pintype "bidirectional"))
      (node (ref "U9") (pin "11") (pinfunction "V-_11") (pintype "bidirectional"))
    )
    (net (code "83") (name "MISO") (class "Default")
      (node (ref "IC1") (pin "4") (pinfunction "Y_4") (pintype "output"))
      (node (ref "IC3") (pin "4") (pinfunction "Y_4") (pintype "output"))
      (node (ref "IC4") (pin "4") (pinfunction "Y_4") (pintype "output"))
      (node (ref "JP1") (pin "7") (pinfunction "7_7") (pintype "passive"))
      (node (ref "SAMD21") (pin "21") (pinfunction "PA12/I12/I2C/SERCOM2+4.0_21") (pintype "bidirectional"))
    )
    (net (code "84") (name "MOSI") (class "Default")
      (node (ref "JP1") (pin "8") (pinfunction "8_8") (pintype "passive"))
      (node (ref "RN2") (pin "3") (pinfunction "1_3") (pintype "passive"))
      (node (ref "RN3") (pin "1") (pinfunction "1_1") (pintype "passive"))
      (node (ref "RN4") (pin "5") (pinfunction "2_5") (pintype "passive"))
      (node (ref "SAMD21") (pin "19") (pinfunction "PB10/I10/SERCOM4.2/I2SMC_19") (pintype "bidirectional"))
    )
    (net (code "85") (name "NOISE") (class "Default")
      (node (ref "R185") (pin "1") (pinfunction "1_1") (pintype "passive"))
      (node (ref "U$16") (pin "2") (pinfunction "B_2") (pintype "passive"))
      (node (ref "U30") (pin "1") (pinfunction "B_1") (pintype "passive"))
      (node (ref "U4") (pin "14") (pinfunction "OUT_14") (pintype "output"))
    )
    (net (code "86") (name "NOISE_IN") (class "Default")
      (node (ref "R55") (pin "2") (pinfunction "2_2") (pintype "passive"))
      (node (ref "U$2") (pin "135") (pinfunction "IOT_213_135") (pintype "bidirectional"))
    )
    (net (code "87") (name "NOISE_SCALED") (class "Default")
      (node (ref "C59") (pin "2") (pinfunction "2_2") (pintype "passive"))
      (node (ref "R191") (pin "2") (pinfunction "2_2") (pintype "passive"))
      (node (ref "R56") (pin "1") (pinfunction "1_1") (pintype "passive"))
      (node (ref "U8") (pin "14") (pinfunction "OUT_14") (pintype "output"))
    )
    (net (code "88") (name "Net-(C24-Pad1)") (class "Default")
      (node (ref "C24") (pin "1") (pinfunction "1_1") (pintype "passive"))
      (node (ref "R23") (pin "1") (pinfunction "1_1") (pintype "passive"))
    )
    (net (code "89") (name "Net-(C37-Pad1)") (class "Default")
      (node (ref "C37") (pin "1") (pinfunction "1_1") (pintype "passive"))
      (node (ref "R29") (pin "1") (pinfunction "1_1") (pintype "passive"))
    )
    (net (code "90") (name "Net-(C47-Pad2)") (class "Default")
      (node (ref "C47") (pin "2") (pinfunction "2_2") (pintype "passive"))
      (node (ref "R39") (pin "2") (pinfunction "2_2") (pintype "passive"))
    )
    (net (code "91") (name "Net-(C53-Pad1)") (class "Default")
      (node (ref "C53") (pin "1") (pinfunction "1_1") (pintype "passive"))
      (node (ref "R17") (pin "1") (pinfunction "1_1") (pintype "passive"))
    )
    (net (code "92") (name "Net-(C55-Pad1)") (class "Default")
      (node (ref "C55") (pin "1") (pinfunction "1_1") (pintype "passive"))
      (node (ref "R47") (pin "2") (pinfunction "2_2") (pintype "passive"))
    )
    (net (code "93") (name "Net-(CN1-P$2)") (class "Default")
      (node (ref "CN1") (pin "3") (pinfunction "P$2_3") (pintype "bidirectional"))
      (node (ref "D10") (pin "A") (pinfunction "A_A") (pintype "passive"))
      (node (ref "OK1") (pin "3") (pinfunction "C_3") (pintype "passive"))
    )
    (net (code "94") (name "Net-(CN1-P$5)") (class "Default")
      (node (ref "CN1") (pin "2") (pinfunction "P$5_2") (pintype "bidirectional"))
      (node (ref "R165") (pin "2") (pinfunction "2_2") (pintype "passive"))
    )
    (net (code "95") (name "Net-(CN3-P$1)") (class "Default")
      (node (ref "CN3") (pin "1") (pinfunction "P$1_1") (pintype "bidirectional"))
      (node (ref "R75") (pin "1") (pinfunction "1_1") (pintype "passive"))
      (node (ref "U$19") (pin "5") (pinfunction "VO1_5") (pintype "bidirectional"))
    )
    (net (code "96") (name "Net-(CN3-P$2)") (class "Default")
      (node (ref "CN3") (pin "2") (pinfunction "P$5_2") (pintype "bidirectional"))
      (node (ref "CN3") (pin "3") (pinfunction "P$2_3") (pintype "bidirectional"))
      (node (ref "U$19") (pin "8") (pinfunction "VO2_8") (pintype "bidirectional"))
    )
    (net (code "97") (name "Net-(D2-C)") (class "Default")
      (node (ref "D2") (pin "K") (pinfunction "C_K") (pintype "passive"))
      (node (ref "U$2") (pin "108") (pinfunction "VPP_2V5_108") (pintype "bidirectional"))
    )
    (net (code "98") (name "Net-(D10-C)") (class "Default")
      (node (ref "D10") (pin "K") (pinfunction "C_K") (pintype "passive"))
      (node (ref "OK1") (pin "2") (pinfunction "A_2") (pintype "passive"))
      (node (ref "R165") (pin "1") (pinfunction "1_1") (pintype "passive"))
    )
    (net (code "99") (name "Net-(FB1-P$1)") (class "Default")
      (node (ref "C88") (pin "2") (pinfunction "2_2") (pintype "passive"))
      (node (ref "FB1") (pin "1") (pinfunction "P$1_1") (pintype "passive"))
      (node (ref "R183") (pin "2") (pinfunction "2_2") (pintype "passive"))
    )
    (net (code "100") (name "Net-(FB2-P$2)") (class "Default")
      (node (ref "C52") (pin "1") (pinfunction "1_1") (pintype "passive"))
      (node (ref "C7") (pin "1") (pinfunction "1_1") (pintype "passive"))
      (node (ref "FB2") (pin "2") (pinfunction "P$2_2") (pintype "passive"))
      (node (ref "R168") (pin "1") (pinfunction "1_1") (pintype "passive"))
      (node (ref "U5") (pin "1") (pinfunction "IN_1") (pintype "power_in"))
    )
    (net (code "101") (name "Net-(IC2-PROG)") (class "Default")
      (node (ref "IC2") (pin "5") (pinfunction "PROG_5") (pintype "input"))
      (node (ref "R68") (pin "1") (pinfunction "1_1") (pintype "passive"))
    )
    (net (code "102") (name "Net-(IC2-STAT)") (class "Default")
      (node (ref "IC2") (pin "1") (pinfunction "STAT_1") (pintype "output"))
      (node (ref "R69") (pin "2") (pinfunction "2_2") (pintype "passive"))
    )
    (net (code "103") (name "Net-(IC4-A)") (class "Default")
      (node (ref "IC4") (pin "2") (pinfunction "A_2") (pintype "input"))
      (node (ref "RAM1") (pin "2") (pinfunction "SDO_2") (pintype "bidirectional"))
      (node (ref "RN3") (pin "2") (pinfunction "1_2") (pintype "passive"))
    )
    (net (code "104") (name "Net-(J100-Pad10)") (class "Default")
      (node (ref "J100") (pin "10") (pinfunction "10_10") (pintype "passive"))
      (node (ref "R179") (pin "1") (pinfunction "1_1") (pintype "passive"))
    )
    (net (code "105") (name "Net-(L-PadA)") (class "Default")
      (node (ref "L") (pin "A") (pinfunction "A_A") (pintype "passive"))
      (node (ref "R164") (pin "2") (pinfunction "2_2") (pintype "passive"))
    )
    (net (code "106") (name "Net-(LED1-PadC)") (class "Default")
      (node (ref "LED1") (pin "C") (pinfunction "C_C") (pintype "passive"))
      (node (ref "R69") (pin "1") (pinfunction "1_1") (pintype "passive"))
    )
    (net (code "107") (name "Net-(RAM1-CS)") (class "Default")
      (node (ref "R60") (pin "1") (pinfunction "1_1") (pintype "passive"))
      (node (ref "RAM1") (pin "1") (pinfunction "CS_1") (pintype "bidirectional"))
      (node (ref "RN3") (pin "5") (pinfunction "2_5") (pintype "passive"))
      (node (ref "U$2") (pin "71") (pinfunction "IOB_108_SS_71") (pintype "bidirectional"))
    )
    (net (code "108") (name "Net-(RAM1-HOLD)") (class "Default")
      (node (ref "R57") (pin "1") (pinfunction "1_1") (pintype "passive"))
      (node (ref "RAM1") (pin "7") (pinfunction "HOLD_7") (pintype "bidirectional"))
    )
    (net (code "109") (name "Net-(RAM1-SCK)") (class "Default")
      (node (ref "R59") (pin "1") (pinfunction "1_1") (pintype "passive"))
      (node (ref "RAM1") (pin "6") (pinfunction "SCK_6") (pintype "bidirectional"))
      (node (ref "RN3") (pin "6") (pinfunction "2_6") (pintype "passive"))
      (node (ref "U$2") (pin "70") (pinfunction "IOB_107_SCK_70") (pintype "bidirectional"))
    )
    (net (code "110") (name "Net-(RAM1-SDI)") (class "Default")
      (node (ref "RAM1") (pin "5") (pinfunction "SDI_5") (pintype "bidirectional"))
      (node (ref "RN3") (pin "8") (pinfunction "2_8") (pintype "passive"))
      (node (ref "U$2") (pin "67") (pinfunction "IOB_105_SDO_67") (pintype "bidirectional"))
    )
    (net (code "111") (name "Net-(RAM1-WP)") (class "Default")
      (node (ref "R58") (pin "1") (pinfunction "1_1") (pintype "passive"))
      (node (ref "RAM1") (pin "3") (pinfunction "WP_3") (pintype "bidirectional"))
    )
    (net (code "112") (name "Net-(RN2A-2)") (class "Default")
      (node (ref "RN2") (pin "8") (pinfunction "2_8") (pintype "passive"))
      (node (ref "X4") (pin "7") (pinfunction "DATA_OUT_7") (pintype "output"))
    )
    (net (code "113") (name "Net-(RN2B-2)") (class "Default")
      (node (ref "RN2") (pin "7") (pinfunction "2_7") (pintype "passive"))
      (node (ref "X4") (pin "5") (pinfunction "SCLK_5") (pintype "input"))
    )
    (net (code "114") (name "Net-(RN2C-2)") (class "Default")
      (node (ref "RN2") (pin "6") (pinfunction "2_6") (pintype "passive"))
      (node (ref "X4") (pin "3") (pinfunction "DATA_IN_3") (pintype "input"))
    )
    (net (code "115") (name "Net-(RN2D-2)") (class "Default")
      (node (ref "RN2") (pin "5") (pinfunction "2_5") (pintype "passive"))
      (node (ref "X4") (pin "2") (pinfunction "CS_2") (pintype "input"))
    )
    (net (code "116") (name "Net-(RN3B-2)") (class "Default")
      (node (ref "RN3") (pin "7") (pinfunction "2_7") (pintype "passive"))
      (node (ref "U$2") (pin "68") (pinfunction "IOB_106_SDI_68") (pintype "bidirectional"))
    )
    (net (code "117") (name "Net-(RN4B-1)") (class "Default")
      (node (ref "RN4") (pin "2") (pinfunction "1_2") (pintype "passive"))
      (node (ref "U$2") (pin "104") (pinfunction "IOR_164_104") (pintype "bidirectional"))
    )
    (net (code "118") (name "Net-(RN4C-1)") (class "Default")
      (node (ref "RN4") (pin "3") (pinfunction "1_3") (pintype "passive"))
      (node (ref "U$2") (pin "102") (pinfunction "IOR_161_102") (pintype "bidirectional"))
    )
    (net (code "119") (name "Net-(RN4D-1)") (class "Default")
      (node (ref "RN4") (pin "4") (pinfunction "1_4") (pintype "passive"))
      (node (ref "U$2") (pin "101") (pinfunction "IOR_160_101") (pintype "bidirectional"))
    )
    (net (code "120") (name "Net-(RN5B-1)") (class "Default")
      (node (ref "RN5") (pin "2") (pinfunction "1_2") (pintype "passive"))
      (node (ref "U$2") (pin "17") (pinfunction "IOL_12A_17") (pintype "bidirectional"))
    )
    (net (code "121") (name "Net-(RN5C-1)") (class "Default")
      (node (ref "RN5") (pin "3") (pinfunction "1_3") (pintype "passive"))
      (node (ref "U$2") (pin "19") (pinfunction "IOL_13A_19") (pintype "bidirectional"))
    )
    (net (code "122") (name "Net-(RN5D-1)") (class "Default")
      (node (ref "RN5") (pin "4") (pinfunction "1_4") (pintype "passive"))
      (node (ref "U$2") (pin "23") (pinfunction "IOL_17A_23") (pintype "bidirectional"))
    )
    (net (code "123") (name "Net-(RN6B-2)") (class "Default")
      (node (ref "RN6") (pin "15") (pinfunction "2_15") (pintype "passive"))
      (node (ref "RN9") (pin "10") (pinfunction "2_10") (pintype "passive"))
      (node (ref "RN9") (pin "8") (pinfunction "1_8") (pintype "passive"))
    )
    (net (code "124") (name "Net-(RN6C-2)") (class "Default")
      (node (ref "RN6") (pin "14") (pinfunction "2_14") (pintype "passive"))
      (node (ref "RN9") (pin "11") (pinfunction "2_11") (pintype "passive"))
      (node (ref "RN9") (pin "7") (pinfunction "1_7") (pintype "passive"))
    )
    (net (code "125") (name "Net-(RN6D-2)") (class "Default")
      (node (ref "RN6") (pin "13") (pinfunction "2_13") (pintype "passive"))
      (node (ref "RN9") (pin "12") (pinfunction "2_12") (pintype "passive"))
      (node (ref "RN9") (pin "6") (pinfunction "1_6") (pintype "passive"))
    )
    (net (code "126") (name "Net-(RN6E-2)") (class "Default")
      (node (ref "RN6") (pin "12") (pinfunction "2_12") (pintype "passive"))
      (node (ref "RN9") (pin "13") (pinfunction "2_13") (pintype "passive"))
      (node (ref "RN9") (pin "5") (pinfunction "1_5") (pintype "passive"))
    )
    (net (code "127") (name "Net-(RN6F-2)") (class "Default")
      (node (ref "RN6") (pin "11") (pinfunction "2_11") (pintype "passive"))
      (node (ref "RN9") (pin "14") (pinfunction "2_14") (pintype "passive"))
      (node (ref "RN9") (pin "4") (pinfunction "1_4") (pintype "passive"))
    )
    (net (code "128") (name "Net-(RN6G-2)") (class "Default")
      (node (ref "RN6") (pin "10") (pinfunction "2_10") (pintype "passive"))
      (node (ref "RN9") (pin "15") (pinfunction "2_15") (pintype "passive"))
      (node (ref "RN9") (pin "3") (pinfunction "1_3") (pintype "passive"))
    )
    (net (code "129") (name "Net-(RN6H-2)") (class "Default")
      (node (ref "RN6") (pin "9") (pinfunction "2_9") (pintype "passive"))
      (node (ref "RN9") (pin "16") (pinfunction "2_16") (pintype "passive"))
      (node (ref "RN9") (pin "2") (pinfunction "1_2") (pintype "passive"))
    )
    (net (code "130") (name "Net-(RN7A-2)") (class "Default")
      (node (ref "RN7") (pin "16") (pinfunction "2_16") (pintype "passive"))
      (node (ref "RN8") (pin "9") (pinfunction "2_9") (pintype "passive"))
      (node (ref "RN9") (pin "1") (pinfunction "1_1") (pintype "passive"))
    )
    (net (code "131") (name "Net-(RN7B-2)") (class "Default")
      (node (ref "RN7") (pin "15") (pinfunction "2_15") (pintype "passive"))
      (node (ref "RN8") (pin "10") (pinfunction "2_10") (pintype "passive"))
      (node (ref "RN8") (pin "8") (pinfunction "1_8") (pintype "passive"))
    )
    (net (code "132") (name "Net-(RN7C-2)") (class "Default")
      (node (ref "RN7") (pin "14") (pinfunction "2_14") (pintype "passive"))
      (node (ref "RN8") (pin "11") (pinfunction "2_11") (pintype "passive"))
      (node (ref "RN8") (pin "7") (pinfunction "1_7") (pintype "passive"))
    )
    (net (code "133") (name "Net-(RN7D-2)") (class "Default")
      (node (ref "RN7") (pin "13") (pinfunction "2_13") (pintype "passive"))
      (node (ref "RN8") (pin "12") (pinfunction "2_12") (pintype "passive"))
      (node (ref "RN8") (pin "6") (pinfunction "1_6") (pintype "passive"))
    )
    (net (code "134") (name "Net-(RN7E-2)") (class "Default")
      (node (ref "RN7") (pin "12") (pinfunction "2_12") (pintype "passive"))
      (node (ref "RN8") (pin "13") (pinfunction "2_13") (pintype "passive"))
      (node (ref "RN8") (pin "5") (pinfunction "1_5") (pintype "passive"))
    )
    (net (code "135") (name "Net-(RN7F-2)") (class "Default")
      (node (ref "RN7") (pin "11") (pinfunction "2_11") (pintype "passive"))
      (node (ref "RN8") (pin "14") (pinfunction "2_14") (pintype "passive"))
      (node (ref "RN8") (pin "4") (pinfunction "1_4") (pintype "passive"))
    )
    (net (code "136") (name "Net-(RN7G-2)") (class "Default")
      (node (ref "RN7") (pin "10") (pinfunction "2_10") (pintype "passive"))
      (node (ref "RN8") (pin "15") (pinfunction "2_15") (pintype "passive"))
      (node (ref "RN8") (pin "3") (pinfunction "1_3") (pintype "passive"))
    )
    (net (code "137") (name "Net-(RN7H-2)") (class "Default")
      (node (ref "R31") (pin "2") (pinfunction "2_2") (pintype "passive"))
      (node (ref "RN7") (pin "9") (pinfunction "2_9") (pintype "passive"))
      (node (ref "RN8") (pin "2") (pinfunction "1_2") (pintype "passive"))
    )
    (net (code "138") (name "Net-(RN10B-2)") (class "Default")
      (node (ref "RN10") (pin "15") (pinfunction "2_15") (pintype "passive"))
      (node (ref "RN13") (pin "10") (pinfunction "2_10") (pintype "passive"))
      (node (ref "RN13") (pin "8") (pinfunction "1_8") (pintype "passive"))
    )
    (net (code "139") (name "Net-(RN10C-2)") (class "Default")
      (node (ref "RN10") (pin "14") (pinfunction "2_14") (pintype "passive"))
      (node (ref "RN13") (pin "11") (pinfunction "2_11") (pintype "passive"))
      (node (ref "RN13") (pin "7") (pinfunction "1_7") (pintype "passive"))
    )
    (net (code "140") (name "Net-(RN10D-2)") (class "Default")
      (node (ref "RN10") (pin "13") (pinfunction "2_13") (pintype "passive"))
      (node (ref "RN13") (pin "12") (pinfunction "2_12") (pintype "passive"))
      (node (ref "RN13") (pin "6") (pinfunction "1_6") (pintype "passive"))
    )
    (net (code "141") (name "Net-(RN10E-2)") (class "Default")
      (node (ref "RN10") (pin "12") (pinfunction "2_12") (pintype "passive"))
      (node (ref "RN13") (pin "13") (pinfunction "2_13") (pintype "passive"))
      (node (ref "RN13") (pin "5") (pinfunction "1_5") (pintype "passive"))
    )
    (net (code "142") (name "Net-(RN10F-2)") (class "Default")
      (node (ref "RN10") (pin "11") (pinfunction "2_11") (pintype "passive"))
      (node (ref "RN13") (pin "14") (pinfunction "2_14") (pintype "passive"))
      (node (ref "RN13") (pin "4") (pinfunction "1_4") (pintype "passive"))
    )
    (net (code "143") (name "Net-(RN10G-2)") (class "Default")
      (node (ref "RN10") (pin "10") (pinfunction "2_10") (pintype "passive"))
      (node (ref "RN13") (pin "15") (pinfunction "2_15") (pintype "passive"))
      (node (ref "RN13") (pin "3") (pinfunction "1_3") (pintype "passive"))
    )
    (net (code "144") (name "Net-(RN10H-2)") (class "Default")
      (node (ref "RN10") (pin "9") (pinfunction "2_9") (pintype "passive"))
      (node (ref "RN13") (pin "16") (pinfunction "2_16") (pintype "passive"))
      (node (ref "RN13") (pin "2") (pinfunction "1_2") (pintype "passive"))
    )
    (net (code "145") (name "Net-(RN11A-2)") (class "Default")
      (node (ref "RN11") (pin "16") (pinfunction "2_16") (pintype "passive"))
      (node (ref "RN12") (pin "9") (pinfunction "2_9") (pintype "passive"))
      (node (ref "RN13") (pin "1") (pinfunction "1_1") (pintype "passive"))
    )
    (net (code "146") (name "Net-(RN11B-2)") (class "Default")
      (node (ref "RN11") (pin "15") (pinfunction "2_15") (pintype "passive"))
      (node (ref "RN12") (pin "10") (pinfunction "2_10") (pintype "passive"))
      (node (ref "RN12") (pin "8") (pinfunction "1_8") (pintype "passive"))
    )
    (net (code "147") (name "Net-(RN11C-2)") (class "Default")
      (node (ref "RN11") (pin "14") (pinfunction "2_14") (pintype "passive"))
      (node (ref "RN12") (pin "11") (pinfunction "2_11") (pintype "passive"))
      (node (ref "RN12") (pin "7") (pinfunction "1_7") (pintype "passive"))
    )
    (net (code "148") (name "Net-(RN11D-2)") (class "Default")
      (node (ref "RN11") (pin "13") (pinfunction "2_13") (pintype "passive"))
      (node (ref "RN12") (pin "12") (pinfunction "2_12") (pintype "passive"))
      (node (ref "RN12") (pin "6") (pinfunction "1_6") (pintype "passive"))
    )
    (net (code "149") (name "Net-(RN11E-2)") (class "Default")
      (node (ref "RN11") (pin "12") (pinfunction "2_12") (pintype "passive"))
      (node (ref "RN12") (pin "13") (pinfunction "2_13") (pintype "passive"))
      (node (ref "RN12") (pin "5") (pinfunction "1_5") (pintype "passive"))
    )
    (net (code "150") (name "Net-(RN11F-2)") (class "Default")
      (node (ref "RN11") (pin "11") (pinfunction "2_11") (pintype "passive"))
      (node (ref "RN12") (pin "14") (pinfunction "2_14") (pintype "passive"))
      (node (ref "RN12") (pin "4") (pinfunction "1_4") (pintype "passive"))
    )
    (net (code "151") (name "Net-(RN11G-2)") (class "Default")
      (node (ref "RN11") (pin "10") (pinfunction "2_10") (pintype "passive"))
      (node (ref "RN12") (pin "15") (pinfunction "2_15") (pintype "passive"))
      (node (ref "RN12") (pin "3") (pinfunction "1_3") (pintype "passive"))
    )
    (net (code "152") (name "Net-(RN11H-2)") (class "Default")
      (node (ref "R32") (pin "2") (pinfunction "2_2") (pintype "passive"))
      (node (ref "RN11") (pin "9") (pinfunction "2_9") (pintype "passive"))
      (node (ref "RN12") (pin "2") (pinfunction "1_2") (pintype "passive"))
    )
    (net (code "153") (name "Net-(RN14A-2)") (class "Default")
      (node (ref "RN14") (pin "16") (pinfunction "2_16") (pintype "passive"))
      (node (ref "RN17") (pin "7") (pinfunction "1_7") (pintype "passive"))
      (node (ref "RN17") (pin "9") (pinfunction "2_9") (pintype "passive"))
    )
    (net (code "154") (name "Net-(RN14B-2)") (class "Default")
      (node (ref "RN14") (pin "15") (pinfunction "2_15") (pintype "passive"))
      (node (ref "RN17") (pin "10") (pinfunction "2_10") (pintype "passive"))
      (node (ref "RN17") (pin "6") (pinfunction "1_6") (pintype "passive"))
    )
    (net (code "155") (name "Net-(RN14C-2)") (class "Default")
      (node (ref "RN14") (pin "14") (pinfunction "2_14") (pintype "passive"))
      (node (ref "RN17") (pin "11") (pinfunction "2_11") (pintype "passive"))
      (node (ref "RN17") (pin "5") (pinfunction "1_5") (pintype "passive"))
    )
    (net (code "156") (name "Net-(RN14D-2)") (class "Default")
      (node (ref "RN14") (pin "13") (pinfunction "2_13") (pintype "passive"))
      (node (ref "RN17") (pin "12") (pinfunction "2_12") (pintype "passive"))
      (node (ref "RN17") (pin "4") (pinfunction "1_4") (pintype "passive"))
    )
    (net (code "157") (name "Net-(RN14E-2)") (class "Default")
      (node (ref "RN14") (pin "12") (pinfunction "2_12") (pintype "passive"))
      (node (ref "RN17") (pin "13") (pinfunction "2_13") (pintype "passive"))
      (node (ref "RN17") (pin "3") (pinfunction "1_3") (pintype "passive"))
    )
    (net (code "158") (name "Net-(RN14F-2)") (class "Default")
      (node (ref "RN14") (pin "11") (pinfunction "2_11") (pintype "passive"))
      (node (ref "RN17") (pin "14") (pinfunction "2_14") (pintype "passive"))
      (node (ref "RN17") (pin "2") (pinfunction "1_2") (pintype "passive"))
    )
    (net (code "159") (name "Net-(RN14G-2)") (class "Default")
      (node (ref "RN14") (pin "10") (pinfunction "2_10") (pintype "passive"))
      (node (ref "RN17") (pin "1") (pinfunction "1_1") (pintype "passive"))
      (node (ref "RN17") (pin "15") (pinfunction "2_15") (pintype "passive"))
    )
    (net (code "160") (name "Net-(RN15A-2)") (class "Default")
      (node (ref "R33") (pin "2") (pinfunction "2_2") (pintype "passive"))
      (node (ref "RN15") (pin "16") (pinfunction "2_16") (pintype "passive"))
      (node (ref "RN16") (pin "7") (pinfunction "1_7") (pintype "passive"))
    )
    (net (code "161") (name "Net-(RN15B-2)") (class "Default")
      (node (ref "RN15") (pin "15") (pinfunction "2_15") (pintype "passive"))
      (node (ref "RN16") (pin "10") (pinfunction "2_10") (pintype "passive"))
      (node (ref "RN16") (pin "6") (pinfunction "1_6") (pintype "passive"))
    )
    (net (code "162") (name "Net-(RN15C-2)") (class "Default")
      (node (ref "RN15") (pin "14") (pinfunction "2_14") (pintype "passive"))
      (node (ref "RN16") (pin "11") (pinfunction "2_11") (pintype "passive"))
      (node (ref "RN16") (pin "5") (pinfunction "1_5") (pintype "passive"))
    )
    (net (code "163") (name "Net-(RN15D-2)") (class "Default")
      (node (ref "RN15") (pin "13") (pinfunction "2_13") (pintype "passive"))
      (node (ref "RN16") (pin "12") (pinfunction "2_12") (pintype "passive"))
      (node (ref "RN16") (pin "4") (pinfunction "1_4") (pintype "passive"))
    )
    (net (code "164") (name "Net-(RN15E-2)") (class "Default")
      (node (ref "RN15") (pin "12") (pinfunction "2_12") (pintype "passive"))
      (node (ref "RN16") (pin "13") (pinfunction "2_13") (pintype "passive"))
      (node (ref "RN16") (pin "3") (pinfunction "1_3") (pintype "passive"))
    )
    (net (code "165") (name "Net-(RN15F-2)") (class "Default")
      (node (ref "RN15") (pin "11") (pinfunction "2_11") (pintype "passive"))
      (node (ref "RN16") (pin "14") (pinfunction "2_14") (pintype "passive"))
      (node (ref "RN16") (pin "2") (pinfunction "1_2") (pintype "passive"))
    )
    (net (code "166") (name "Net-(RN15G-2)") (class "Default")
      (node (ref "RN15") (pin "10") (pinfunction "2_10") (pintype "passive"))
      (node (ref "RN16") (pin "1") (pinfunction "1_1") (pintype "passive"))
      (node (ref "RN16") (pin "15") (pinfunction "2_15") (pintype "passive"))
    )
    (net (code "167") (name "Net-(RN15H-2)") (class "Default")
      (node (ref "RN15") (pin "9") (pinfunction "2_9") (pintype "passive"))
      (node (ref "RN16") (pin "16") (pinfunction "2_16") (pintype "passive"))
      (node (ref "RN17") (pin "8") (pinfunction "1_8") (pintype "passive"))
    )
    (net (code "168") (name "Net-(S1A-P)") (class "Default")
      (node (ref "S1") (pin "2") (pinfunction "P_2") (pintype "passive"))
      (node (ref "U5") (pin "3") (pinfunction "EN_3") (pintype "input"))
    )
    (net (code "169") (name "Net-(S1A-S)") (class "Default")
      (node (ref "R168") (pin "2") (pinfunction "2_2") (pintype "passive"))
      (node (ref "S1") (pin "3") (pinfunction "S_3") (pintype "passive"))
    )
    (net (code "170") (name "Net-(SAMD21-PA00{slash}EINT0{slash}SERCOM1.0)") (class "Default")
      (node (ref "C49") (pin "1") (pinfunction "1_1") (pintype "passive"))
      (node (ref "SAMD21") (pin "1") (pinfunction "PA00/EINT0/SERCOM1.0_1") (pintype "bidirectional"))
      (node (ref "X2") (pin "P$1") (pinfunction "P$1_P$1") (pintype "bidirectional"))
    )
    (net (code "171") (name "Net-(SAMD21-PA01{slash}EINT1{slash}SERCOM1.1)") (class "Default")
      (node (ref "C50") (pin "1") (pinfunction "1_1") (pintype "passive"))
      (node (ref "SAMD21") (pin "2") (pinfunction "PA01/EINT1/SERCOM1.1_2") (pintype "bidirectional"))
      (node (ref "X2") (pin "P$2") (pinfunction "P$2_P$2") (pintype "bidirectional"))
    )
    (net (code "172") (name "Net-(SAMD21-VDDCORE)") (class "Default")
      (node (ref "C32") (pin "1") (pinfunction "1_1") (pintype "passive"))
      (node (ref "SAMD21") (pin "43") (pinfunction "VDDCORE_43") (pintype "power_in"))
    )
    (net (code "173") (name "Net-(U$1A-C)") (class "Default")
      (node (ref "C1") (pin "1") (pinfunction "1_1") (pintype "passive"))
      (node (ref "R2") (pin "1") (pinfunction "1_1") (pintype "passive"))
      (node (ref "R42") (pin "1") (pinfunction "1_1") (pintype "passive"))
      (node (ref "R7") (pin "1") (pinfunction "1_1") (pintype "passive"))
      (node (ref "U$1") (pin "3") (pinfunction "C_3") (pintype "passive"))
      (node (ref "U1") (pin "2") (pinfunction "-IN_2") (pintype "input"))
      (node (ref "U2") (pin "3") (pinfunction "C_3") (pintype "passive"))
    )
    (net (code "174") (name "Net-(U$1A-E)") (class "Default")
      (node (ref "R1") (pin "2") (pinfunction "2_2") (pintype "passive"))
      (node (ref "U$1") (pin "4") (pinfunction "E_4") (pintype "passive"))
      (node (ref "U$1") (pin "5") (pinfunction "E_5") (pintype "passive"))
    )
    (net (code "175") (name "Net-(U$1B-C)") (class "Default")
      (node (ref "C2") (pin "1") (pinfunction "1_1") (pintype "passive"))
      (node (ref "R3") (pin "2") (pinfunction "2_2") (pintype "passive"))
      (node (ref "U$1") (pin "6") (pinfunction "C_6") (pintype "passive"))
      (node (ref "U1") (pin "13") (pinfunction "-IN_13") (pintype "input"))
      (node (ref "U2") (pin "6") (pinfunction "C_6") (pintype "passive"))
    )
    (net (code "176") (name "Net-(U$2A-GNDPLL)") (class "Default")
      (node (ref "C11") (pin "2") (pinfunction "2_2") (pintype "passive"))
      (node (ref "C12") (pin "1") (pinfunction "1_1") (pintype "passive"))
      (node (ref "U$2") (pin "127") (pinfunction "GNDPLL_127") (pintype "bidirectional"))
    )
    (net (code "177") (name "Net-(U$2A-VCCPLL)") (class "Default")
      (node (ref "C11") (pin "1") (pinfunction "1_1") (pintype "passive"))
      (node (ref "C12") (pin "2") (pinfunction "2_2") (pintype "passive"))
      (node (ref "R9") (pin "1") (pinfunction "1_1") (pintype "passive"))
      (node (ref "U$2") (pin "126") (pinfunction "VCCPLL_126") (pintype "bidirectional"))
    )
    (net (code "178") (name "Net-(U$2B-IOR_166)") (class "Default")
      (node (ref "RN4") (pin "1") (pinfunction "1_1") (pintype "passive"))
      (node (ref "U$2") (pin "106") (pinfunction "IOR_166_106") (pintype "bidirectional"))
    )
    (net (code "179") (name "Net-(U$2C-GNDPLL)") (class "Default")
      (node (ref "C10") (pin "1") (pinfunction "1_1") (pintype "passive"))
      (node (ref "C9") (pin "2") (pinfunction "2_2") (pintype "passive"))
      (node (ref "U$2") (pin "53") (pinfunction "GNDPLL_53") (pintype "bidirectional"))
    )
    (net (code "180") (name "Net-(U$2C-VCCPLL)") (class "Default")
      (node (ref "C10") (pin "2") (pinfunction "2_2") (pintype "passive"))
      (node (ref "C9") (pin "1") (pinfunction "1_1") (pintype "passive"))
      (node (ref "R8") (pin "1") (pinfunction "1_1") (pintype "passive"))
      (node (ref "U$2") (pin "54") (pinfunction "VCCPLL_54") (pintype "bidirectional"))
    )
    (net (code "181") (name "Net-(U$2D-IOL_8B)") (class "Default")
      (node (ref "R30") (pin "2") (pinfunction "2_2") (pintype "passive"))
      (node (ref "U$2") (pin "12") (pinfunction "IOL_8B_12") (pintype "bidirectional"))
    )
    (net (code "182") (name "Net-(U$2D-IOL_10A)") (class "Default")
      (node (ref "RN5") (pin "1") (pinfunction "1_1") (pintype "passive"))
      (node (ref "U$2") (pin "15") (pinfunction "IOL_10A_15") (pintype "bidirectional"))
    )
    (net (code "183") (name "Net-(U$3A-C)") (class "Default")
      (node (ref "C3") (pin "1") (pinfunction "1_1") (pintype "passive"))
      (node (ref "R16") (pin "1") (pinfunction "1_1") (pintype "passive"))
      (node (ref "R17") (pin "2") (pinfunction "2_2") (pintype "passive"))
      (node (ref "U$3") (pin "3") (pinfunction "C_3") (pintype "passive"))
      (node (ref "U1") (pin "6") (pinfunction "-IN_6") (pintype "input"))
      (node (ref "U6") (pin "3") (pinfunction "C_3") (pintype "passive"))
    )
    (net (code "184") (name "Net-(U$3A-E)") (class "Default")
      (node (ref "R4") (pin "2") (pinfunction "2_2") (pintype "passive"))
      (node (ref "U$3") (pin "4") (pinfunction "E_4") (pintype "passive"))
      (node (ref "U$3") (pin "5") (pinfunction "E_5") (pintype "passive"))
    )
    (net (code "185") (name "Net-(U$3B-C)") (class "Default")
      (node (ref "C22") (pin "1") (pinfunction "1_1") (pintype "passive"))
      (node (ref "R13") (pin "2") (pinfunction "2_2") (pintype "passive"))
      (node (ref "U$3") (pin "6") (pinfunction "C_6") (pintype "passive"))
      (node (ref "U1") (pin "9") (pinfunction "-IN_9") (pintype "input"))
      (node (ref "U6") (pin "6") (pinfunction "C_6") (pintype "passive"))
    )
    (net (code "186") (name "Net-(U$4A-C)") (class "Default")
      (node (ref "C26") (pin "1") (pinfunction "1_1") (pintype "passive"))
      (node (ref "R22") (pin "1") (pinfunction "1_1") (pintype "passive"))
      (node (ref "R23") (pin "2") (pinfunction "2_2") (pintype "passive"))
      (node (ref "U$4") (pin "3") (pinfunction "C_3") (pintype "passive"))
      (node (ref "U10") (pin "3") (pinfunction "C_3") (pintype "passive"))
      (node (ref "U9") (pin "2") (pinfunction "-IN_2") (pintype "input"))
    )
    (net (code "187") (name "Net-(U$4A-E)") (class "Default")
      (node (ref "R18") (pin "2") (pinfunction "2_2") (pintype "passive"))
      (node (ref "U$4") (pin "4") (pinfunction "E_4") (pintype "passive"))
      (node (ref "U$4") (pin "5") (pinfunction "E_5") (pintype "passive"))
    )
    (net (code "188") (name "Net-(U$4B-C)") (class "Default")
      (node (ref "C35") (pin "1") (pinfunction "1_1") (pintype "passive"))
      (node (ref "R19") (pin "2") (pinfunction "2_2") (pintype "passive"))
      (node (ref "U$4") (pin "6") (pinfunction "C_6") (pintype "passive"))
      (node (ref "U10") (pin "6") (pinfunction "C_6") (pintype "passive"))
      (node (ref "U9") (pin "13") (pinfunction "-IN_13") (pintype "input"))
    )
    (net (code "189") (name "Net-(U$5-OE{slash}ST)") (class "Default")
      (node (ref "R61") (pin "1") (pinfunction "1_1") (pintype "passive"))
      (node (ref "U$5") (pin "1") (pinfunction "OE/ST_1") (pintype "bidirectional"))
    )
    (net (code "190") (name "Net-(U$7A-C)") (class "Default")
      (node (ref "C38") (pin "1") (pinfunction "1_1") (pintype "passive"))
      (node (ref "R28") (pin "1") (pinfunction "1_1") (pintype "passive"))
      (node (ref "R29") (pin "2") (pinfunction "2_2") (pintype "passive"))
      (node (ref "U$7") (pin "3") (pinfunction "C_3") (pintype "passive"))
      (node (ref "U16") (pin "3") (pinfunction "C_3") (pintype "passive"))
      (node (ref "U9") (pin "6") (pinfunction "-IN_6") (pintype "input"))
    )
    (net (code "191") (name "Net-(U$7A-E)") (class "Default")
      (node (ref "R24") (pin "2") (pinfunction "2_2") (pintype "passive"))
      (node (ref "U$7") (pin "4") (pinfunction "E_4") (pintype "passive"))
      (node (ref "U$7") (pin "5") (pinfunction "E_5") (pintype "passive"))
    )
    (net (code "192") (name "Net-(U$7B-C)") (class "Default")
      (node (ref "C39") (pin "1") (pinfunction "1_1") (pintype "passive"))
      (node (ref "R25") (pin "2") (pinfunction "2_2") (pintype "passive"))
      (node (ref "U$7") (pin "6") (pinfunction "C_6") (pintype "passive"))
      (node (ref "U16") (pin "6") (pinfunction "C_6") (pintype "passive"))
      (node (ref "U9") (pin "9") (pinfunction "-IN_9") (pintype "input"))
    )
    (net (code "193") (name "Net-(U$8A-C)") (class "Default")
      (node (ref "C43") (pin "1") (pinfunction "1_1") (pintype "passive"))
      (node (ref "R35") (pin "1") (pinfunction "1_1") (pintype "passive"))
      (node (ref "U$8") (pin "3") (pinfunction "C_3") (pintype "passive"))
      (node (ref "U14") (pin "2") (pinfunction "-IN_2") (pintype "input"))
      (node (ref "U21") (pin "3") (pinfunction "C_3") (pintype "passive"))
    )
    (net (code "194") (name "Net-(U$8A-E)") (class "Default")
      (node (ref "R34") (pin "2") (pinfunction "2_2") (pintype "passive"))
      (node (ref "U$8") (pin "4") (pinfunction "E_4") (pintype "passive"))
      (node (ref "U$8") (pin "5") (pinfunction "E_5") (pintype "passive"))
    )
    (net (code "195") (name "Net-(U$8B-C)") (class "Default")
      (node (ref "C44") (pin "1") (pinfunction "1_1") (pintype "passive"))
      (node (ref "R36") (pin "2") (pinfunction "2_2") (pintype "passive"))
      (node (ref "U$8") (pin "6") (pinfunction "C_6") (pintype "passive"))
      (node (ref "U14") (pin "13") (pinfunction "-IN_13") (pintype "input"))
      (node (ref "U21") (pin "6") (pinfunction "C_6") (pintype "passive"))
    )
    (net (code "196") (name "Net-(U$9A-C)") (class "Default")
      (node (ref "C45") (pin "1") (pinfunction "1_1") (pintype "passive"))
      (node (ref "R47") (pin "1") (pinfunction "1_1") (pintype "passive"))
      (node (ref "U$9") (pin "3") (pinfunction "C_3") (pintype "passive"))
      (node (ref "U14") (pin "6") (pinfunction "-IN_6") (pintype "input"))
      (node (ref "U24") (pin "3") (pinfunction "C_3") (pintype "passive"))
    )
    (net (code "197") (name "Net-(U$9A-E)") (class "Default")
      (node (ref "R46") (pin "2") (pinfunction "2_2") (pintype "passive"))
      (node (ref "U$9") (pin "4") (pinfunction "E_4") (pintype "passive"))
      (node (ref "U$9") (pin "5") (pinfunction "E_5") (pintype "passive"))
    )
    (net (code "198") (name "Net-(U$9B-C)") (class "Default")
      (node (ref "C46") (pin "1") (pinfunction "1_1") (pintype "passive"))
      (node (ref "R48") (pin "2") (pinfunction "2_2") (pintype "passive"))
      (node (ref "U$9") (pin "6") (pinfunction "C_6") (pintype "passive"))
      (node (ref "U14") (pin "9") (pinfunction "-IN_9") (pintype "input"))
      (node (ref "U24") (pin "6") (pinfunction "C_6") (pintype "passive"))
    )
    (net (code "199") (name "Net-(U$15A-C)") (class "Default")
      (node (ref "C56") (pin "1") (pinfunction "1_1") (pintype "passive"))
      (node (ref "R51") (pin "1") (pinfunction "1_1") (pintype "passive"))
      (node (ref "R70") (pin "1") (pinfunction "1_1") (pintype "passive"))
      (node (ref "R71") (pin "1") (pinfunction "1_1") (pintype "passive"))
      (node (ref "U$15") (pin "3") (pinfunction "C_3") (pintype "passive"))
      (node (ref "U27") (pin "3") (pinfunction "C_3") (pintype "passive"))
      (node (ref "U8") (pin "6") (pinfunction "-IN_6") (pintype "input"))
    )
    (net (code "200") (name "Net-(U$15A-E)") (class "Default")
      (node (ref "R50") (pin "2") (pinfunction "2_2") (pintype "passive"))
      (node (ref "U$15") (pin "4") (pinfunction "E_4") (pintype "passive"))
      (node (ref "U$15") (pin "5") (pinfunction "E_5") (pintype "passive"))
    )
    (net (code "201") (name "Net-(U$15B-C)") (class "Default")
      (node (ref "C57") (pin "1") (pinfunction "1_1") (pintype "passive"))
      (node (ref "R52") (pin "2") (pinfunction "2_2") (pintype "passive"))
      (node (ref "U$15") (pin "6") (pinfunction "C_6") (pintype "passive"))
      (node (ref "U27") (pin "6") (pinfunction "C_6") (pintype "passive"))
      (node (ref "U8") (pin "9") (pinfunction "-IN_9") (pintype "input"))
    )
    (net (code "202") (name "Net-(U$16A-C)") (class "Default")
      (node (ref "C58") (pin "1") (pinfunction "1_1") (pintype "passive"))
      (node (ref "R55") (pin "1") (pinfunction "1_1") (pintype "passive"))
      (node (ref "U$16") (pin "3") (pinfunction "C_3") (pintype "passive"))
      (node (ref "U30") (pin "3") (pinfunction "C_3") (pintype "passive"))
      (node (ref "U8") (pin "2") (pinfunction "-IN_2") (pintype "input"))
    )
    (net (code "203") (name "Net-(U$16A-E)") (class "Default")
      (node (ref "R54") (pin "2") (pinfunction "2_2") (pintype "passive"))
      (node (ref "U$16") (pin "4") (pinfunction "E_4") (pintype "passive"))
      (node (ref "U$16") (pin "5") (pinfunction "E_5") (pintype "passive"))
    )
    (net (code "204") (name "Net-(U$16B-C)") (class "Default")
      (node (ref "C59") (pin "1") (pinfunction "1_1") (pintype "passive"))
      (node (ref "R56") (pin "2") (pinfunction "2_2") (pintype "passive"))
      (node (ref "U$16") (pin "6") (pinfunction "C_6") (pintype "passive"))
      (node (ref "U30") (pin "6") (pinfunction "C_6") (pintype "passive"))
      (node (ref "U8") (pin "13") (pinfunction "-IN_13") (pintype "input"))
    )
    (net (code "205") (name "Net-(U$19-BYPASS)") (class "Default")
      (node (ref "C60") (pin "1") (pinfunction "1_1") (pintype "passive"))
      (node (ref "U$19") (pin "2") (pinfunction "BYPASS_2") (pintype "bidirectional"))
      (node (ref "U$19") (pin "3") (pinfunction "VIN+_3") (pintype "bidirectional"))
    )
    (net (code "206") (name "Net-(U$19-VIN-)") (class "Default")
      (node (ref "R66") (pin "1") (pinfunction "1_1") (pintype "passive"))
      (node (ref "R75") (pin "2") (pinfunction "2_2") (pintype "passive"))
      (node (ref "U$19") (pin "4") (pinfunction "VIN-_4") (pintype "bidirectional"))
    )
    (net (code "207") (name "Net-(U1A-OUT)") (class "Default")
      (node (ref "C1") (pin "2") (pinfunction "2_2") (pintype "passive"))
      (node (ref "R1") (pin "1") (pinfunction "1_1") (pintype "passive"))
      (node (ref "U1") (pin "1") (pinfunction "OUT_1") (pintype "output"))
    )
    (net (code "208") (name "Net-(U1B-OUT)") (class "Default")
      (node (ref "C3") (pin "2") (pinfunction "2_2") (pintype "passive"))
      (node (ref "R4") (pin "1") (pinfunction "1_1") (pintype "passive"))
      (node (ref "U1") (pin "7") (pinfunction "OUT_7") (pintype "output"))
    )
    (net (code "209") (name "Net-(U1C-OUT)") (class "Default")
      (node (ref "C22") (pin "2") (pinfunction "2_2") (pintype "passive"))
      (node (ref "R13") (pin "1") (pinfunction "1_1") (pintype "passive"))
      (node (ref "R14") (pin "2") (pinfunction "2_2") (pintype "passive"))
      (node (ref "U1") (pin "8") (pinfunction "OUT_8") (pintype "output"))
    )
    (net (code "210") (name "Net-(U1D-OUT)") (class "Default")
      (node (ref "C2") (pin "2") (pinfunction "2_2") (pintype "passive"))
      (node (ref "R3") (pin "1") (pinfunction "1_1") (pintype "passive"))
      (node (ref "R5") (pin "2") (pinfunction "2_2") (pintype "passive"))
      (node (ref "U1") (pin "14") (pinfunction "OUT_14") (pintype "output"))
    )
    (net (code "211") (name "Net-(U2A-E)") (class "Default")
      (node (ref "U2") (pin "4") (pinfunction "E_4") (pintype "passive"))
      (node (ref "U2") (pin "5") (pinfunction "E_5") (pintype "passive"))
      (node (ref "U3") (pin "3") (pinfunction "C_3") (pintype "passive"))
    )
    (net (code "212") (name "Net-(U3A-B)") (class "Default")
      (node (ref "R6") (pin "2") (pinfunction "2_2") (pintype "passive"))
      (node (ref "U3") (pin "1") (pinfunction "B_1") (pintype "passive"))
      (node (ref "U3") (pin "2") (pinfunction "B_2") (pintype "passive"))
      (node (ref "U3") (pin "6") (pinfunction "C_6") (pintype "passive"))
    )
    (net (code "213") (name "Net-(U4A-+IN)") (class "Default")
      (node (ref "R169") (pin "1") (pinfunction "1_1") (pintype "passive"))
      (node (ref "R67") (pin "1") (pinfunction "1_1") (pintype "passive"))
      (node (ref "U4") (pin "3") (pinfunction "+IN_3") (pintype "input"))
    )
    (net (code "214") (name "Net-(U4A--IN)") (class "Default")
      (node (ref "R63") (pin "1") (pinfunction "1_1") (pintype "passive"))
      (node (ref "R65") (pin "2") (pinfunction "2_2") (pintype "passive"))
      (node (ref "U4") (pin "2") (pinfunction "-IN_2") (pintype "input"))
    )
    (net (code "215") (name "Net-(U4B-+IN)") (class "Default")
      (node (ref "R181") (pin "2") (pinfunction "2_2") (pintype "passive"))
      (node (ref "R184") (pin "2") (pinfunction "2_2") (pintype "passive"))
      (node (ref "U4") (pin "5") (pinfunction "+IN_5") (pintype "input"))
    )
    (net (code "216") (name "Net-(U4B--IN)") (class "Default")
      (node (ref "R178") (pin "1") (pinfunction "1_1") (pintype "passive"))
      (node (ref "R180") (pin "2") (pinfunction "2_2") (pintype "passive"))
      (node (ref "U4") (pin "6") (pinfunction "-IN_6") (pintype "input"))
    )
    (net (code "217") (name "Net-(U4C-+IN)") (class "Default")
      (node (ref "R172") (pin "2") (pinfunction "2_2") (pintype "passive"))
      (node (ref "R173") (pin "2") (pinfunction "2_2") (pintype "passive"))
      (node (ref "U4") (pin "10") (pinfunction "+IN_10") (pintype "input"))
    )
    (net (code "218") (name "Net-(U4C--IN)") (class "Default")
      (node (ref "R170") (pin "1") (pinfunction "1_1") (pintype "passive"))
      (node (ref "R171") (pin "2") (pinfunction "2_2") (pintype "passive"))
      (node (ref "U4") (pin "9") (pinfunction "-IN_9") (pintype "input"))
    )
    (net (code "219") (name "Net-(U4D-+IN)") (class "Default")
      (node (ref "R187") (pin "2") (pinfunction "2_2") (pintype "passive"))
      (node (ref "R188") (pin "2") (pinfunction "2_2") (pintype "passive"))
      (node (ref "U4") (pin "12") (pinfunction "+IN_12") (pintype "input"))
    )
    (net (code "220") (name "Net-(U4D--IN)") (class "Default")
      (node (ref "R185") (pin "2") (pinfunction "2_2") (pintype "passive"))
      (node (ref "R186") (pin "1") (pinfunction "1_1") (pintype "passive"))
      (node (ref "U4") (pin "13") (pinfunction "-IN_13") (pintype "input"))
    )
    (net (code "221") (name "Net-(U6A-E)") (class "Default")
      (node (ref "U6") (pin "4") (pinfunction "E_4") (pintype "passive"))
      (node (ref "U6") (pin "5") (pinfunction "E_5") (pintype "passive"))
      (node (ref "U7") (pin "3") (pinfunction "C_3") (pintype "passive"))
    )
    (net (code "222") (name "Net-(U7A-B)") (class "Default")
      (node (ref "R15") (pin "2") (pinfunction "2_2") (pintype "passive"))
      (node (ref "U7") (pin "1") (pinfunction "B_1") (pintype "passive"))
      (node (ref "U7") (pin "2") (pinfunction "B_2") (pintype "passive"))
      (node (ref "U7") (pin "6") (pinfunction "C_6") (pintype "passive"))
    )
    (net (code "223") (name "Net-(U8A-OUT)") (class "Default")
      (node (ref "C58") (pin "2") (pinfunction "2_2") (pintype "passive"))
      (node (ref "R54") (pin "1") (pinfunction "1_1") (pintype "passive"))
      (node (ref "U8") (pin "1") (pinfunction "OUT_1") (pintype "output"))
    )
    (net (code "224") (name "Net-(U8B-OUT)") (class "Default")
      (node (ref "C56") (pin "2") (pinfunction "2_2") (pintype "passive"))
      (node (ref "R50") (pin "1") (pinfunction "1_1") (pintype "passive"))
      (node (ref "U8") (pin "7") (pinfunction "OUT_7") (pintype "output"))
    )
    (net (code "225") (name "Net-(U9A-OUT)") (class "Default")
      (node (ref "C26") (pin "2") (pinfunction "2_2") (pintype "passive"))
      (node (ref "R18") (pin "1") (pinfunction "1_1") (pintype "passive"))
      (node (ref "U9") (pin "1") (pinfunction "OUT_1") (pintype "output"))
    )
    (net (code "226") (name "Net-(U9B-OUT)") (class "Default")
      (node (ref "C38") (pin "2") (pinfunction "2_2") (pintype "passive"))
      (node (ref "R24") (pin "1") (pinfunction "1_1") (pintype "passive"))
      (node (ref "U9") (pin "7") (pinfunction "OUT_7") (pintype "output"))
    )
    (net (code "227") (name "Net-(U9C-OUT)") (class "Default")
      (node (ref "C39") (pin "2") (pinfunction "2_2") (pintype "passive"))
      (node (ref "R25") (pin "1") (pinfunction "1_1") (pintype "passive"))
      (node (ref "R26") (pin "2") (pinfunction "2_2") (pintype "passive"))
      (node (ref "U9") (pin "8") (pinfunction "OUT_8") (pintype "output"))
    )
    (net (code "228") (name "Net-(U9D-OUT)") (class "Default")
      (node (ref "C35") (pin "2") (pinfunction "2_2") (pintype "passive"))
      (node (ref "R19") (pin "1") (pinfunction "1_1") (pintype "passive"))
      (node (ref "R20") (pin "2") (pinfunction "2_2") (pintype "passive"))
      (node (ref "U9") (pin "14") (pinfunction "OUT_14") (pintype "output"))
    )
    (net (code "229") (name "Net-(U10A-E)") (class "Default")
      (node (ref "U10") (pin "4") (pinfunction "E_4") (pintype "passive"))
      (node (ref "U10") (pin "5") (pinfunction "E_5") (pintype "passive"))
      (node (ref "U11") (pin "3") (pinfunction "C_3") (pintype "passive"))
    )
    (net (code "230") (name "Net-(U11A-B)") (class "Default")
      (node (ref "R21") (pin "2") (pinfunction "2_2") (pintype "passive"))
      (node (ref "U11") (pin "1") (pinfunction "B_1") (pintype "passive"))
      (node (ref "U11") (pin "2") (pinfunction "B_2") (pintype "passive"))
      (node (ref "U11") (pin "6") (pinfunction "C_6") (pintype "passive"))
    )
    (net (code "231") (name "Net-(U12-EN1)") (class "Default")
      (node (ref "R166") (pin "1") (pinfunction "1_1") (pintype "passive"))
      (node (ref "U12") (pin "1") (pinfunction "EN1_1") (pintype "input"))
    )
    (net (code "232") (name "Net-(U12-EN2)") (class "Default")
      (node (ref "R167") (pin "1") (pinfunction "1_1") (pintype "passive"))
      (node (ref "U12") (pin "3") (pinfunction "EN2_3") (pintype "input"))
    )
    (net (code "233") (name "Net-(U13A-+IN)") (class "Default")
      (node (ref "C21") (pin "1") (pinfunction "1_1") (pintype "passive"))
      (node (ref "R73") (pin "2") (pinfunction "2_2") (pintype "passive"))
      (node (ref "U13") (pin "3") (pinfunction "+IN_3") (pintype "input"))
    )
    (net (code "234") (name "Net-(U13A--IN)") (class "Default")
      (node (ref "R12") (pin "2") (pinfunction "2_2") (pintype "passive"))
      (node (ref "R72") (pin "1") (pinfunction "1_1") (pintype "passive"))
      (node (ref "U13") (pin "4") (pinfunction "-IN_4") (pintype "input"))
    )
    (net (code "235") (name "Net-(U13A-OUT)") (class "Default")
      (node (ref "R72") (pin "2") (pinfunction "2_2") (pintype "passive"))
      (node (ref "R74") (pin "2") (pinfunction "2_2") (pintype "passive"))
      (node (ref "U13") (pin "1") (pinfunction "OUT_1") (pintype "output"))
    )
    (net (code "236") (name "Net-(U14A-OUT)") (class "Default")
      (node (ref "C43") (pin "2") (pinfunction "2_2") (pintype "passive"))
      (node (ref "R34") (pin "1") (pinfunction "1_1") (pintype "passive"))
      (node (ref "U14") (pin "1") (pinfunction "OUT_1") (pintype "output"))
    )
    (net (code "237") (name "Net-(U14B-OUT)") (class "Default")
      (node (ref "C45") (pin "2") (pinfunction "2_2") (pintype "passive"))
      (node (ref "R46") (pin "1") (pinfunction "1_1") (pintype "passive"))
      (node (ref "U14") (pin "7") (pinfunction "OUT_7") (pintype "output"))
    )
    (net (code "238") (name "Net-(U14C-OUT)") (class "Default")
      (node (ref "C46") (pin "2") (pinfunction "2_2") (pintype "passive"))
      (node (ref "C88") (pin "1") (pinfunction "1_1") (pintype "passive"))
      (node (ref "R48") (pin "1") (pinfunction "1_1") (pintype "passive"))
      (node (ref "U14") (pin "8") (pinfunction "OUT_8") (pintype "output"))
    )
    (net (code "239") (name "Net-(U15A--IN)") (class "Default")
      (node (ref "C4") (pin "1") (pinfunction "1_1") (pintype "passive"))
      (node (ref "R5") (pin "1") (pinfunction "1_1") (pintype "passive"))
      (node (ref "U15") (pin "2") (pinfunction "-IN_2") (pintype "input"))
    )
    (net (code "240") (name "Net-(U15A-OUT)") (class "Default")
      (node (ref "C4") (pin "2") (pinfunction "2_2") (pintype "passive"))
      (node (ref "C53") (pin "2") (pinfunction "2_2") (pintype "passive"))
      (node (ref "R7") (pin "2") (pinfunction "2_2") (pintype "passive"))
      (node (ref "U15") (pin "1") (pinfunction "OUT_1") (pintype "output"))
    )
    (net (code "241") (name "Net-(U15B--IN)") (class "Default")
      (node (ref "C36") (pin "1") (pinfunction "1_1") (pintype "passive"))
      (node (ref "R20") (pin "1") (pinfunction "1_1") (pintype "passive"))
      (node (ref "U15") (pin "6") (pinfunction "-IN_6") (pintype "input"))
    )
    (net (code "242") (name "Net-(U15B-OUT)") (class "Default")
      (node (ref "C36") (pin "2") (pinfunction "2_2") (pintype "passive"))
      (node (ref "C37") (pin "2") (pinfunction "2_2") (pintype "passive"))
      (node (ref "R22") (pin "2") (pinfunction "2_2") (pintype "passive"))
      (node (ref "U15") (pin "7") (pinfunction "OUT_7") (pintype "output"))
    )
    (net (code "243") (name "Net-(U15C--IN)") (class "Default")
      (node (ref "C40") (pin "1") (pinfunction "1_1") (pintype "passive"))
      (node (ref "R26") (pin "1") (pinfunction "1_1") (pintype "passive"))
      (node (ref "U15") (pin "9") (pinfunction "-IN_9") (pintype "input"))
    )
    (net (code "244") (name "Net-(U15D--IN)") (class "Default")
      (node (ref "C23") (pin "1") (pinfunction "1_1") (pintype "passive"))
      (node (ref "R14") (pin "1") (pinfunction "1_1") (pintype "passive"))
      (node (ref "U15") (pin "13") (pinfunction "-IN_13") (pintype "input"))
    )
    (net (code "245") (name "Net-(U16A-E)") (class "Default")
      (node (ref "U16") (pin "4") (pinfunction "E_4") (pintype "passive"))
      (node (ref "U16") (pin "5") (pinfunction "E_5") (pintype "passive"))
      (node (ref "U17") (pin "3") (pinfunction "C_3") (pintype "passive"))
    )
    (net (code "246") (name "Net-(U17A-B)") (class "Default")
      (node (ref "R27") (pin "2") (pinfunction "2_2") (pintype "passive"))
      (node (ref "U17") (pin "1") (pinfunction "B_1") (pintype "passive"))
      (node (ref "U17") (pin "2") (pinfunction "B_2") (pintype "passive"))
      (node (ref "U17") (pin "6") (pinfunction "C_6") (pintype "passive"))
    )
    (net (code "247") (name "Net-(U18A--IN)") (class "Default")
      (node (ref "R191") (pin "1") (pinfunction "1_1") (pintype "passive"))
      (node (ref "R192") (pin "1") (pinfunction "1_1") (pintype "passive"))
      (node (ref "R194") (pin "1") (pinfunction "1_1") (pintype "passive"))
      (node (ref "R43") (pin "2") (pinfunction "2_2") (pintype "passive"))
      (node (ref "R44") (pin "1") (pinfunction "1_1") (pintype "passive"))
      (node (ref "R45") (pin "1") (pinfunction "1_1") (pintype "passive"))
      (node (ref "R74") (pin "1") (pinfunction "1_1") (pintype "passive"))
      (node (ref "R99") (pin "1") (pinfunction "1_1") (pintype "passive"))
      (node (ref "U18") (pin "2") (pinfunction "-IN_2") (pintype "input"))
    )
    (net (code "248") (name "Net-(U18B-+IN)") (class "Default")
      (node (ref "R40") (pin "1") (pinfunction "1_1") (pintype "passive"))
      (node (ref "R41") (pin "1") (pinfunction "1_1") (pintype "passive"))
      (node (ref "U18") (pin "5") (pinfunction "+IN_5") (pintype "input"))
    )
    (net (code "249") (name "Net-(U18B--IN)") (class "Default")
      (node (ref "R38") (pin "2") (pinfunction "2_2") (pintype "passive"))
      (node (ref "R39") (pin "1") (pinfunction "1_1") (pintype "passive"))
      (node (ref "U18") (pin "6") (pinfunction "-IN_6") (pintype "input"))
    )
    (net (code "250") (name "Net-(U18B-OUT)") (class "Default")
      (node (ref "R35") (pin "2") (pinfunction "2_2") (pintype "passive"))
      (node (ref "R38") (pin "1") (pinfunction "1_1") (pintype "passive"))
      (node (ref "U18") (pin "7") (pinfunction "OUT_7") (pintype "output"))
    )
    (net (code "251") (name "Net-(U18C-+IN)") (class "Default")
      (node (ref "R176") (pin "1") (pinfunction "1_1") (pintype "passive"))
      (node (ref "R177") (pin "1") (pinfunction "1_1") (pintype "passive"))
      (node (ref "U18") (pin "10") (pinfunction "+IN_10") (pintype "input"))
    )
    (net (code "252") (name "Net-(U18C--IN)") (class "Default")
      (node (ref "R174") (pin "1") (pinfunction "1_1") (pintype "passive"))
      (node (ref "R175") (pin "2") (pinfunction "2_2") (pintype "passive"))
      (node (ref "U18") (pin "9") (pinfunction "-IN_9") (pintype "input"))
    )
    (net (code "253") (name "Net-(U18D-+IN)") (class "Default")
      (node (ref "R189") (pin "2") (pinfunction "2_2") (pintype "passive"))
      (node (ref "R190") (pin "1") (pinfunction "1_1") (pintype "passive"))
      (node (ref "U18") (pin "12") (pinfunction "+IN_12") (pintype "input"))
    )
    (net (code "254") (name "Net-(U21A-E)") (class "Default")
      (node (ref "U21") (pin "4") (pinfunction "E_4") (pintype "passive"))
      (node (ref "U21") (pin "5") (pinfunction "E_5") (pintype "passive"))
      (node (ref "U22") (pin "3") (pinfunction "C_3") (pintype "passive"))
    )
    (net (code "255") (name "Net-(U22A-B)") (class "Default")
      (node (ref "R37") (pin "2") (pinfunction "2_2") (pintype "passive"))
      (node (ref "U22") (pin "1") (pinfunction "B_1") (pintype "passive"))
      (node (ref "U22") (pin "2") (pinfunction "B_2") (pintype "passive"))
      (node (ref "U22") (pin "6") (pinfunction "C_6") (pintype "passive"))
    )
    (net (code "256") (name "Net-(U24A-E)") (class "Default")
      (node (ref "U24") (pin "4") (pinfunction "E_4") (pintype "passive"))
      (node (ref "U24") (pin "5") (pinfunction "E_5") (pintype "passive"))
      (node (ref "U25") (pin "3") (pinfunction "C_3") (pintype "passive"))
    )
    (net (code "257") (name "Net-(U25A-B)") (class "Default")
      (node (ref "R49") (pin "2") (pinfunction "2_2") (pintype "passive"))
      (node (ref "U25") (pin "1") (pinfunction "B_1") (pintype "passive"))
      (node (ref "U25") (pin "2") (pinfunction "B_2") (pintype "passive"))
      (node (ref "U25") (pin "6") (pinfunction "C_6") (pintype "passive"))
    )
    (net (code "258") (name "Net-(U27A-E)") (class "Default")
      (node (ref "U27") (pin "4") (pinfunction "E_4") (pintype "passive"))
      (node (ref "U27") (pin "5") (pinfunction "E_5") (pintype "passive"))
      (node (ref "U28") (pin "3") (pinfunction "C_3") (pintype "passive"))
    )
    (net (code "259") (name "Net-(U28A-B)") (class "Default")
      (node (ref "R53") (pin "2") (pinfunction "2_2") (pintype "passive"))
      (node (ref "U28") (pin "1") (pinfunction "B_1") (pintype "passive"))
      (node (ref "U28") (pin "2") (pinfunction "B_2") (pintype "passive"))
      (node (ref "U28") (pin "6") (pinfunction "C_6") (pintype "passive"))
    )
    (net (code "260") (name "Net-(U30A-E)") (class "Default")
      (node (ref "U30") (pin "4") (pinfunction "E_4") (pintype "passive"))
      (node (ref "U30") (pin "5") (pinfunction "E_5") (pintype "passive"))
      (node (ref "U31") (pin "3") (pinfunction "C_3") (pintype "passive"))
    )
    (net (code "261") (name "Net-(U31A-B)") (class "Default")
      (node (ref "R62") (pin "2") (pinfunction "2_2") (pintype "passive"))
      (node (ref "U31") (pin "1") (pinfunction "B_1") (pintype "passive"))
      (node (ref "U31") (pin "2") (pinfunction "B_2") (pintype "passive"))
      (node (ref "U31") (pin "6") (pinfunction "C_6") (pintype "passive"))
    )
    (net (code "262") (name "OSC_0") (class "Default")
      (node (ref "JP1") (pin "31") (pinfunction "31_31") (pintype "passive"))
      (node (ref "OSC0") (pin "TP") (pinfunction "TP_TP") (pintype "input"))
      (node (ref "R45") (pin "2") (pinfunction "2_2") (pintype "passive"))
      (node (ref "RN6") (pin "16") (pinfunction "2_16") (pintype "passive"))
      (node (ref "RN9") (pin "9") (pinfunction "2_9") (pintype "passive"))
    )
    (net (code "263") (name "OSC_1") (class "Default")
      (node (ref "JP1") (pin "30") (pinfunction "30_30") (pintype "passive"))
      (node (ref "OSC1") (pin "TP") (pinfunction "TP_TP") (pintype "input"))
      (node (ref "R44") (pin "2") (pinfunction "2_2") (pintype "passive"))
      (node (ref "RN10") (pin "16") (pinfunction "2_16") (pintype "passive"))
      (node (ref "RN13") (pin "9") (pinfunction "2_9") (pintype "passive"))
    )
    (net (code "264") (name "OSC_2") (class "Default")
      (node (ref "JP1") (pin "32") (pinfunction "32_32") (pintype "passive"))
      (node (ref "OSC2") (pin "TP") (pinfunction "TP_TP") (pintype "input"))
      (node (ref "R99") (pin "2") (pinfunction "2_2") (pintype "passive"))
      (node (ref "RN14") (pin "9") (pinfunction "2_9") (pintype "passive"))
      (node (ref "RN17") (pin "16") (pinfunction "2_16") (pintype "passive"))
    )
    (net (code "265") (name "OUT") (class "Default")
      (node (ref "3.3V") (pin "TP") (pinfunction "TP_TP") (pintype "input"))
      (node (ref "C29") (pin "1") (pinfunction "1_1") (pintype "passive"))
      (node (ref "C31") (pin "1") (pinfunction "1_1") (pintype "passive"))
      (node (ref "U5") (pin "5") (pinfunction "OUT_5") (pintype "power_in"))
    )
    (net (code "266") (name "PWM_CUTOFF") (class "Default")
      (node (ref "C80") (pin "2") (pinfunction "2_2") (pintype "passive"))
      (node (ref "JP1") (pin "34") (pinfunction "34_34") (pintype "passive"))
      (node (ref "R30") (pin "1") (pinfunction "1_1") (pintype "passive"))
      (node (ref "R63") (pin "2") (pinfunction "2_2") (pintype "passive"))
    )
    (net (code "267") (name "PWM_NOISE") (class "Default")
      (node (ref "C70") (pin "2") (pinfunction "2_2") (pintype "passive"))
      (node (ref "R186") (pin "2") (pinfunction "2_2") (pintype "passive"))
      (node (ref "RN5") (pin "7") (pinfunction "2_7") (pintype "passive"))
    )
    (net (code "268") (name "PWM_RESO") (class "Default")
      (node (ref "C71") (pin "2") (pinfunction "2_2") (pintype "passive"))
      (node (ref "R180") (pin "1") (pinfunction "1_1") (pintype "passive"))
      (node (ref "RN5") (pin "8") (pinfunction "2_8") (pintype "passive"))
    )
    (net (code "269") (name "PWM_SUB") (class "Default")
      (node (ref "C68") (pin "2") (pinfunction "2_2") (pintype "passive"))
      (node (ref "R174") (pin "2") (pinfunction "2_2") (pintype "passive"))
      (node (ref "RN5") (pin "5") (pinfunction "2_5") (pintype "passive"))
    )
    (net (code "270") (name "PWM_VCA") (class "Default")
      (node (ref "C69") (pin "2") (pinfunction "2_2") (pintype "passive"))
      (node (ref "R171") (pin "1") (pinfunction "1_1") (pintype "passive"))
      (node (ref "RN5") (pin "6") (pinfunction "2_6") (pintype "passive"))
    )
    (net (code "271") (name "RESO") (class "Default")
      (node (ref "R178") (pin "2") (pinfunction "2_2") (pintype "passive"))
      (node (ref "U$8") (pin "2") (pinfunction "B_2") (pintype "passive"))
      (node (ref "U21") (pin "1") (pinfunction "B_1") (pintype "passive"))
      (node (ref "U4") (pin "7") (pinfunction "OUT_7") (pintype "output"))
    )
    (net (code "272") (name "RES_OUT") (class "Default")
      (node (ref "C44") (pin "2") (pinfunction "2_2") (pintype "passive"))
      (node (ref "R36") (pin "1") (pinfunction "1_1") (pintype "passive"))
      (node (ref "R42") (pin "2") (pinfunction "2_2") (pintype "passive"))
      (node (ref "U14") (pin "14") (pinfunction "OUT_14") (pintype "output"))
    )
    (net (code "273") (name "RXD") (class "Default")
      (node (ref "OK1") (pin "6") (pinfunction "VO_6") (pintype "passive"))
      (node (ref "R182") (pin "2") (pinfunction "2_2") (pintype "passive"))
      (node (ref "SAMD21") (pin "38") (pinfunction "PB23/I7/SERCOM5.3_38") (pintype "bidirectional"))
    )
    (net (code "274") (name "SCK") (class "Default")
      (node (ref "JP1") (pin "9") (pinfunction "9_9") (pintype "passive"))
      (node (ref "RN2") (pin "2") (pinfunction "1_2") (pintype "passive"))
      (node (ref "RN3") (pin "3") (pinfunction "1_3") (pintype "passive"))
      (node (ref "RN4") (pin "6") (pinfunction "2_6") (pintype "passive"))
      (node (ref "SAMD21") (pin "20") (pinfunction "PB11/I11/SERCOM4.3/I2SCL_20") (pintype "bidirectional"))
    )
    (net (code "275") (name "SCL") (class "Default")
      (node (ref "JP1") (pin "13") (pinfunction "13_13") (pintype "passive"))
      (node (ref "SAMD21") (pin "32") (pinfunction "PA23/I2C/I7/SERCOM3+5.1/SOF_32") (pintype "bidirectional"))
    )
    (net (code "276") (name "SDA") (class "Default")
      (node (ref "JP1") (pin "14") (pinfunction "14_14") (pintype "passive"))
      (node (ref "SAMD21") (pin "31") (pinfunction "PA22/I2C/I6/SERCOM3+5.0_31") (pintype "bidirectional"))
    )
    (net (code "277") (name "SD_CS") (class "Default")
      (node (ref "IC3") (pin "1") (pinfunction "~{OE}_1") (pintype "input"))
      (node (ref "R64") (pin "1") (pinfunction "1_1") (pintype "passive"))
      (node (ref "RN2") (pin "4") (pinfunction "1_4") (pintype "passive"))
      (node (ref "SAMD21") (pin "28") (pinfunction "PA19/I3/SERCOM1+3.3/I2SD0_28") (pintype "bidirectional"))
    )
    (net (code "278") (name "SD_MISO") (class "Default")
      (node (ref "IC3") (pin "2") (pinfunction "A_2") (pintype "input"))
      (node (ref "RN2") (pin "1") (pinfunction "1_1") (pintype "passive"))
    )
    (net (code "279") (name "SPI_SS_B") (class "Default")
      (node (ref "IC4") (pin "1") (pinfunction "~{OE}_1") (pintype "input"))
      (node (ref "RN3") (pin "4") (pinfunction "1_4") (pintype "passive"))
      (node (ref "SAMD21") (pin "3") (pinfunction "PA02/EINT2/AIN0/Y0/VOUT_3") (pintype "bidirectional"))
    )
    (net (code "280") (name "SUB") (class "Default")
      (node (ref "R175") (pin "1") (pinfunction "1_1") (pintype "passive"))
      (node (ref "U$15") (pin "2") (pinfunction "B_2") (pintype "passive"))
      (node (ref "U18") (pin "8") (pinfunction "OUT_8") (pintype "output"))
      (node (ref "U27") (pin "1") (pinfunction "B_1") (pintype "passive"))
    )
    (net (code "281") (name "SUB0") (class "Default")
      (node (ref "R71") (pin "2") (pinfunction "2_2") (pintype "passive"))
      (node (ref "U$2") (pin "125") (pinfunction "IOT_192_125") (pintype "bidirectional"))
    )
    (net (code "282") (name "SUB1") (class "Default")
      (node (ref "R70") (pin "2") (pinfunction "2_2") (pintype "passive"))
      (node (ref "U$2") (pin "130") (pinfunction "IOT_206_130") (pintype "bidirectional"))
    )
    (net (code "283") (name "SUB2") (class "Default")
      (node (ref "R51") (pin "2") (pinfunction "2_2") (pintype "passive"))
      (node (ref "U$2") (pin "134") (pinfunction "IOT_212_134") (pintype "bidirectional"))
    )
    (net (code "284") (name "SUB_SCALED") (class "Default")
      (node (ref "C57") (pin "2") (pinfunction "2_2") (pintype "passive"))
      (node (ref "R192") (pin "2") (pinfunction "2_2") (pintype "passive"))
      (node (ref "R52") (pin "1") (pinfunction "1_1") (pintype "passive"))
      (node (ref "U8") (pin "8") (pinfunction "OUT_8") (pintype "output"))
    )
    (net (code "285") (name "SWCLK") (class "Default")
      (node (ref "J100") (pin "4") (pinfunction "4_4") (pintype "passive"))
      (node (ref "SAMD21") (pin "45") (pinfunction "PA30/I10/SECOM1.2/SWCLK_45") (pintype "bidirectional"))
    )
    (net (code "286") (name "SWDIO") (class "Default")
      (node (ref "J100") (pin "2") (pinfunction "2_2") (pintype "passive"))
      (node (ref "SAMD21") (pin "46") (pinfunction "PA31/I11/SECOM1.3/SWDIO_46") (pintype "bidirectional"))
    )
    (net (code "287") (name "VBAT") (class "Default")
      (node (ref "C8") (pin "1") (pinfunction "1_1") (pintype "passive"))
      (node (ref "C81") (pin "1") (pinfunction "1_1") (pintype "passive"))
      (node (ref "CN2") (pin "1") (pinfunction "2_1") (pintype "passive"))
      (node (ref "D1") (pin "A") (pinfunction "A_A") (pintype "passive"))
      (node (ref "IC2") (pin "3") (pinfunction "VBAT_3") (pintype "bidirectional"))
    )
    (net (code "288") (name "VBUS") (class "Default")
      (node (ref "D3") (pin "A") (pinfunction "A_A") (pintype "passive"))
      (node (ref "IC2") (pin "4") (pinfunction "VDD_4") (pintype "power_in"))
      (node (ref "LED1") (pin "A") (pinfunction "A_A") (pintype "passive"))
      (node (ref "X3") (pin "VBUS") (pinfunction "VBUS_VBUS") (pintype "power_in"))
    )
    (net (code "289") (name "VCA") (class "Default")
      (node (ref "R170") (pin "2") (pinfunction "2_2") (pintype "passive"))
      (node (ref "U$9") (pin "2") (pinfunction "B_2") (pintype "passive"))
      (node (ref "U24") (pin "1") (pinfunction "B_1") (pintype "passive"))
      (node (ref "U4") (pin "8") (pinfunction "OUT_8") (pintype "output"))
    )
    (net (code "290") (name "VIN") (class "Default")
      (node (ref "C5") (pin "1") (pinfunction "1_1") (pintype "passive"))
      (node (ref "D1") (pin "C") (pinfunction "C_C") (pintype "passive"))
      (node (ref "D3") (pin "C") (pinfunction "C_C") (pintype "passive"))
      (node (ref "FB2") (pin "1") (pinfunction "P$1_1") (pintype "passive"))
      (node (ref "JP1") (pin "5") (pinfunction "5_5") (pintype "passive"))
    )
    (net (code "291") (name "VSUM") (class "Default")
      (node (ref "R2") (pin "2") (pinfunction "2_2") (pintype "passive"))
      (node (ref "R40") (pin "2") (pinfunction "2_2") (pintype "passive"))
      (node (ref "R43") (pin "1") (pinfunction "1_1") (pintype "passive"))
      (node (ref "U18") (pin "1") (pinfunction "OUT_1") (pintype "output"))
    )
    (net (code "292") (name "unconnected-(CN1-P$1-Pad1)") (class "Default")
      (node (ref "CN1") (pin "1") (pinfunction "P$1_1") (pintype "bidirectional"))
    )
    (net (code "293") (name "unconnected-(CN1-P$3-Pad5)") (class "Default")
      (node (ref "CN1") (pin "5") (pinfunction "P$3_5") (pintype "bidirectional"))
    )
    (net (code "294") (name "unconnected-(CN1-P$4-Pad4)") (class "Default")
      (node (ref "CN1") (pin "4") (pinfunction "P$4_4") (pintype "bidirectional"))
    )
    (net (code "295") (name "unconnected-(CN3-P$3-Pad5)") (class "Default")
      (node (ref "CN3") (pin "5") (pinfunction "P$3_5") (pintype "bidirectional"))
    )
    (net (code "296") (name "unconnected-(CN3-P$4-Pad4)") (class "Default")
      (node (ref "CN3") (pin "4") (pinfunction "P$4_4") (pintype "bidirectional"))
    )
    (net (code "297") (name "unconnected-(J100-Pad6)") (class "Default")
      (node (ref "J100") (pin "6") (pinfunction "6_6") (pintype "passive"))
    )
    (net (code "298") (name "unconnected-(J100-Pad7)") (class "Default")
      (node (ref "J100") (pin "7") (pinfunction "7_7") (pintype "passive"))
    )
    (net (code "299") (name "unconnected-(J100-Pad8)") (class "Default")
      (node (ref "J100") (pin "8") (pinfunction "8_8") (pintype "passive"))
    )
    (net (code "300") (name "unconnected-(JP1-Pad21)") (class "Default")
      (node (ref "JP1") (pin "21") (pinfunction "21_21") (pintype "passive"))
    )
    (net (code "301") (name "unconnected-(JP1-Pad23)") (class "Default")
      (node (ref "JP1") (pin "23") (pinfunction "23_23") (pintype "passive"))
    )
    (net (code "302") (name "unconnected-(JP1-Pad24)") (class "Default")
      (node (ref "JP1") (pin "24") (pinfunction "24_24") (pintype "passive"))
    )
    (net (code "303") (name "unconnected-(JP1-Pad25)") (class "Default")
      (node (ref "JP1") (pin "25") (pinfunction "25_25") (pintype "passive"))
    )
    (net (code "304") (name "unconnected-(JP1-Pad26)") (class "Default")
      (node (ref "JP1") (pin "26") (pinfunction "26_26") (pintype "passive"))
    )
    (net (code "305") (name "unconnected-(JP1-Pad27)") (class "Default")
      (node (ref "JP1") (pin "27") (pinfunction "27_27") (pintype "passive"))
    )
    (net (code "306") (name "unconnected-(JP1-Pad28)") (class "Default")
      (node (ref "JP1") (pin "28") (pinfunction "28_28") (pintype "passive"))
    )
    (net (code "307") (name "unconnected-(JP1-Pad29)") (class "Default")
      (node (ref "JP1") (pin "29") (pinfunction "29_29") (pintype "passive"))
    )
    (net (code "308") (name "unconnected-(OK1-VE-Pad7)") (class "Default")
      (node (ref "OK1") (pin "7") (pinfunction "VE_7") (pintype "passive"))
    )
    (net (code "309") (name "unconnected-(RN8-Pad1)") (class "Default")
      (node (ref "RN8") (pin "1") (pinfunction "1_1") (pintype "passive"))
    )
    (net (code "310") (name "unconnected-(RN8A-2-Pad16)") (class "Default")
      (node (ref "RN8") (pin "16") (pinfunction "2_16") (pintype "passive"))
    )
    (net (code "311") (name "unconnected-(RN12-Pad1)") (class "Default")
      (node (ref "RN12") (pin "1") (pinfunction "1_1") (pintype "passive"))
    )
    (net (code "312") (name "unconnected-(RN12A-2-Pad16)") (class "Default")
      (node (ref "RN12") (pin "16") (pinfunction "2_16") (pintype "passive"))
    )
    (net (code "313") (name "unconnected-(RN16H-1-Pad8)") (class "Default")
      (node (ref "RN16") (pin "8") (pinfunction "1_8") (pintype "passive"))
    )
    (net (code "314") (name "unconnected-(RN16H-2-Pad9)") (class "Default")
      (node (ref "RN16") (pin "9") (pinfunction "2_9") (pintype "passive"))
    )
    (net (code "315") (name "unconnected-(SAMD21-PA13{slash}I13{slash}I2C{slash}SERCOM2+4.1-Pad22)") (class "Default")
      (node (ref "SAMD21") (pin "22") (pinfunction "PA13/I13/I2C/SERCOM2+4.1_22") (pintype "bidirectional"))
    )
    (net (code "316") (name "unconnected-(SAMD21-PA15{slash}I15{slash}SERCOM3+4.3-Pad24)") (class "Default")
      (node (ref "SAMD21") (pin "24") (pinfunction "PA15/I15/SERCOM3+4.3_24") (pintype "bidirectional"))
    )
    (net (code "317") (name "unconnected-(SAMD21-PA16{slash}I2C{slash}I0{slash}SERCOM1+3.0-Pad25)") (class "Default")
      (node (ref "SAMD21") (pin "25") (pinfunction "PA16/I2C/I0/SERCOM1+3.0_25") (pintype "bidirectional"))
    )
    (net (code "318") (name "unconnected-(SAMD21-PA27{slash}I15-Pad39)") (class "Default")
      (node (ref "SAMD21") (pin "39") (pinfunction "PA27/I15_39") (pintype "bidirectional"))
    )
    (net (code "319") (name "unconnected-(SAMD21-PA28{slash}I8-Pad41)") (class "Default")
      (node (ref "SAMD21") (pin "41") (pinfunction "PA28/I8_41") (pintype "bidirectional"))
    )
    (net (code "320") (name "unconnected-(SAMD21-PB03{slash}I3{slash}AIN11{slash}SERCOM5.1-Pad48)") (class "Default")
      (node (ref "SAMD21") (pin "48") (pinfunction "PB03/I3/AIN11/SERCOM5.1_48") (pintype "bidirectional"))
    )
    (net (code "321") (name "unconnected-(SAMD21-PB22{slash}I6{slash}SERCOM5.2-Pad37)") (class "Default")
      (node (ref "SAMD21") (pin "37") (pinfunction "PB22/I6/SERCOM5.2_37") (pintype "bidirectional"))
    )
    (net (code "322") (name "unconnected-(U$2A-IOT_178-Pad119)") (class "Default")
      (node (ref "U$2") (pin "119") (pinfunction "IOT_178_119") (pintype "bidirectional"))
    )
    (net (code "323") (name "unconnected-(U$2A-IOT_179-Pad120)") (class "Default")
      (node (ref "U$2") (pin "120") (pinfunction "IOT_179_120") (pintype "bidirectional"))
    )
    (net (code "324") (name "unconnected-(U$2A-IOT_181-Pad121)") (class "Default")
      (node (ref "U$2") (pin "121") (pinfunction "IOT_181_121") (pintype "bidirectional"))
    )
    (net (code "325") (name "unconnected-(U$2A-IOT_190-Pad122)") (class "Default")
      (node (ref "U$2") (pin "122") (pinfunction "IOT_190_122") (pintype "bidirectional"))
    )
    (net (code "326") (name "unconnected-(U$2A-IOT_191-Pad124)") (class "Default")
      (node (ref "U$2") (pin "124") (pinfunction "IOT_191_124") (pintype "bidirectional"))
    )
    (net (code "327") (name "unconnected-(U$2A-IOT_197_GBIN1-Pad128)") (class "Default")
      (node (ref "U$2") (pin "128") (pinfunction "IOT_197_GBIN1_128") (pintype "bidirectional"))
    )
    (net (code "328") (name "unconnected-(U$2A-IOT_198_GBIN0-Pad129)") (class "Default")
      (node (ref "U$2") (pin "129") (pinfunction "IOT_198_GBIN0_129") (pintype "bidirectional"))
    )
    (net (code "329") (name "unconnected-(U$2B-IOR_109-Pad73)") (class "Default")
      (node (ref "U$2") (pin "73") (pinfunction "IOR_109_73") (pintype "bidirectional"))
    )
    (net (code "330") (name "unconnected-(U$2B-IOR_110-Pad74)") (class "Default")
      (node (ref "U$2") (pin "74") (pinfunction "IOR_110_74") (pintype "bidirectional"))
    )
    (net (code "331") (name "unconnected-(U$2B-IOR_111-Pad75)") (class "Default")
      (node (ref "U$2") (pin "75") (pinfunction "IOR_111_75") (pintype "bidirectional"))
    )
    (net (code "332") (name "unconnected-(U$2B-IOR_112-Pad76)") (class "Default")
      (node (ref "U$2") (pin "76") (pinfunction "IOR_112_76") (pintype "bidirectional"))
    )
    (net (code "333") (name "unconnected-(U$2B-IOR_114-Pad78)") (class "Default")
      (node (ref "U$2") (pin "78") (pinfunction "IOR_114_78") (pintype "bidirectional"))
    )
    (net (code "334") (name "unconnected-(U$2B-IOR_115-Pad79)") (class "Default")
      (node (ref "U$2") (pin "79") (pinfunction "IOR_115_79") (pintype "bidirectional"))
    )
    (net (code "335") (name "unconnected-(U$2B-IOR_116-Pad80)") (class "Default")
      (node (ref "U$2") (pin "80") (pinfunction "IOR_116_80") (pintype "bidirectional"))
    )
    (net (code "336") (name "unconnected-(U$2B-IOR_117-Pad81)") (class "Default")
      (node (ref "U$2") (pin "81") (pinfunction "IOR_117_81") (pintype "bidirectional"))
    )
    (net (code "337") (name "unconnected-(U$2B-IOR_118-Pad82)") (class "Default")
      (node (ref "U$2") (pin "82") (pinfunction "IOR_118_82") (pintype "bidirectional"))
    )
    (net (code "338") (name "unconnected-(U$2B-IOR_119-Pad83)") (class "Default")
      (node (ref "U$2") (pin "83") (pinfunction "IOR_119_83") (pintype "bidirectional"))
    )
    (net (code "339") (name "unconnected-(U$2B-IOR_120-Pad84)") (class "Default")
      (node (ref "U$2") (pin "84") (pinfunction "IOR_120_84") (pintype "bidirectional"))
    )
    (net (code "340") (name "unconnected-(U$2B-IOR_128-Pad85)") (class "Default")
      (node (ref "U$2") (pin "85") (pinfunction "IOR_128_85") (pintype "bidirectional"))
    )
    (net (code "341") (name "unconnected-(U$2B-IOR_136-Pad87)") (class "Default")
      (node (ref "U$2") (pin "87") (pinfunction "IOR_136_87") (pintype "bidirectional"))
    )
    (net (code "342") (name "unconnected-(U$2B-IOR_137-Pad88)") (class "Default")
      (node (ref "U$2") (pin "88") (pinfunction "IOR_137_88") (pintype "bidirectional"))
    )
    (net (code "343") (name "unconnected-(U$2B-IOR_138-Pad90)") (class "Default")
      (node (ref "U$2") (pin "90") (pinfunction "IOR_138_90") (pintype "bidirectional"))
    )
    (net (code "344") (name "unconnected-(U$2B-IOR_139-Pad91)") (class "Default")
      (node (ref "U$2") (pin "91") (pinfunction "IOR_139_91") (pintype "bidirectional"))
    )
    (net (code "345") (name "unconnected-(U$2B-IOR_140_GBIN3-Pad93)") (class "Default")
      (node (ref "U$2") (pin "93") (pinfunction "IOR_140_GBIN3_93") (pintype "bidirectional"))
    )
    (net (code "346") (name "unconnected-(U$2B-IOR_141_GBIN2-Pad94)") (class "Default")
      (node (ref "U$2") (pin "94") (pinfunction "IOR_141_GBIN2_94") (pintype "bidirectional"))
    )
    (net (code "347") (name "unconnected-(U$2B-IOR_144-Pad95)") (class "Default")
      (node (ref "U$2") (pin "95") (pinfunction "IOR_144_95") (pintype "bidirectional"))
    )
    (net (code "348") (name "unconnected-(U$2B-IOR_146-Pad96)") (class "Default")
      (node (ref "U$2") (pin "96") (pinfunction "IOR_146_96") (pintype "bidirectional"))
    )
    (net (code "349") (name "unconnected-(U$2B-IOR_147-Pad97)") (class "Default")
      (node (ref "U$2") (pin "97") (pinfunction "IOR_147_97") (pintype "bidirectional"))
    )
    (net (code "350") (name "unconnected-(U$2B-IOR_148-Pad98)") (class "Default")
      (node (ref "U$2") (pin "98") (pinfunction "IOR_148_98") (pintype "bidirectional"))
    )
    (net (code "351") (name "unconnected-(U$2B-IOR_152-Pad99)") (class "Default")
      (node (ref "U$2") (pin "99") (pinfunction "IOR_152_99") (pintype "bidirectional"))
    )
    (net (code "352") (name "unconnected-(U$2B-NC-Pad77)") (class "Default")
      (node (ref "U$2") (pin "77") (pinfunction "NC_77") (pintype "bidirectional"))
    )
    (net (code "353") (name "unconnected-(U$2B-VPP_FAST-Pad109)") (class "Default")
      (node (ref "U$2") (pin "109") (pinfunction "VPP_FAST_109") (pintype "bidirectional"))
    )
    (net (code "354") (name "unconnected-(U$2C-IOB_81_GBIN5-Pad49)") (class "Default")
      (node (ref "U$2") (pin "49") (pinfunction "IOB_81_GBIN5_49") (pintype "bidirectional"))
    )
    (net (code "355") (name "unconnected-(U$2C-IOB_82_GBIN4-Pad52)") (class "Default")
      (node (ref "U$2") (pin "52") (pinfunction "IOB_82_GBIN4_52") (pintype "bidirectional"))
    )
    (net (code "356") (name "unconnected-(U$2C-IOB_104_CBSEL1-Pad64)") (class "Default")
      (node (ref "U$2") (pin "64") (pinfunction "IOB_104_CBSEL1_64") (pintype "bidirectional"))
    )
    (net (code "357") (name "unconnected-(U$2D-IOL_8A-Pad11)") (class "Default")
      (node (ref "U$2") (pin "11") (pinfunction "IOL_8A_11") (pintype "bidirectional"))
    )
    (net (code "358") (name "unconnected-(U$2D-IOL_10B-Pad16)") (class "Default")
      (node (ref "U$2") (pin "16") (pinfunction "IOL_10B_16") (pintype "bidirectional"))
    )
    (net (code "359") (name "unconnected-(U$2D-IOL_12B-Pad18)") (class "Default")
      (node (ref "U$2") (pin "18") (pinfunction "IOL_12B_18") (pintype "bidirectional"))
    )
    (net (code "360") (name "unconnected-(U$2D-IOL_13B_GBIN7-Pad20)") (class "Default")
      (node (ref "U$2") (pin "20") (pinfunction "IOL_13B_GBIN7_20") (pintype "bidirectional"))
    )
    (net (code "361") (name "unconnected-(U$2D-IOL_14B-Pad22)") (class "Default")
      (node (ref "U$2") (pin "22") (pinfunction "IOL_14B_22") (pintype "bidirectional"))
    )
    (net (code "362") (name "unconnected-(U$2D-IOL_17B-Pad24)") (class "Default")
      (node (ref "U$2") (pin "24") (pinfunction "IOL_17B_24") (pintype "bidirectional"))
    )
    (net (code "363") (name "unconnected-(U5-P4-Pad4)") (class "Default")
      (node (ref "U5") (pin "4") (pinfunction "P4_4") (pintype "bidirectional"))
    )
    (net (code "364") (name "unconnected-(X3-PadID)") (class "Default")
      (node (ref "X3") (pin "ID") (pinfunction "ID_ID") (pintype "bidirectional"))
    )
    (net (code "365") (name "unconnected-(X4-CARD_DETECT-PadCD1)") (class "Default")
      (node (ref "X4") (pin "CD1") (pinfunction "CARD_DETECT_CD1") (pintype "passive"))
    )
    (net (code "366") (name "unconnected-(X4-CARD_DETECT1-PadCD2)") (class "Default")
      (node (ref "X4") (pin "CD2") (pinfunction "CARD_DETECT1_CD2") (pintype "passive"))
    )
    (net (code "367") (name "unconnected-(X4-DAT1-Pad8)") (class "Default")
      (node (ref "X4") (pin "8") (pinfunction "DAT1_8") (pintype "bidirectional"))
    )
    (net (code "368") (name "unconnected-(X4-DAT2-Pad1)") (class "Default")
      (node (ref "X4") (pin "1") (pinfunction "DAT2_1") (pintype "bidirectional"))
    )
    (net (code "369") (name "~{RESET}") (class "Default")
      (node (ref "JP1") (pin "3") (pinfunction "3_3") (pintype "passive"))
      (node (ref "R179") (pin "2") (pinfunction "2_2") (pintype "passive"))
      (node (ref "SAMD21") (pin "40") (pinfunction "/RESET_40") (pintype "bidirectional"))
      (node (ref "SW1") (pin "1") (pinfunction "P_1") (pintype "passive"))
      (node (ref "SW1") (pin "3") (pinfunction "P1_3") (pintype "passive"))
    )
  )
)
